# BoardSchem.net
KiCad netlist of a schematic drawn in EAGLE
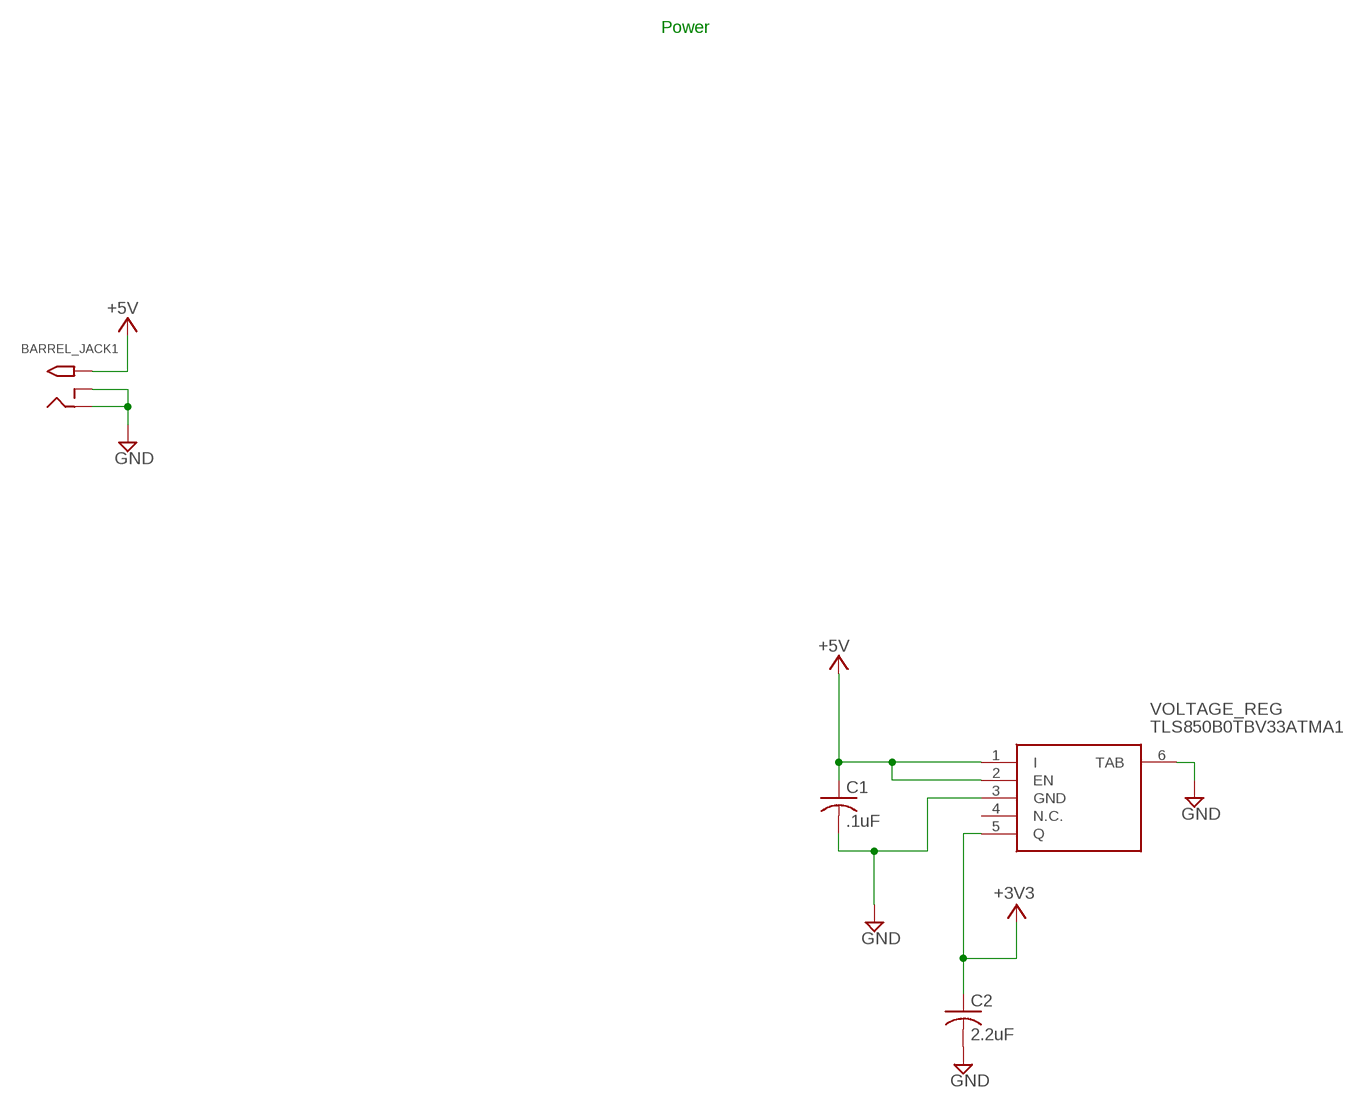
[diagram p0: schematic, sheet 1]
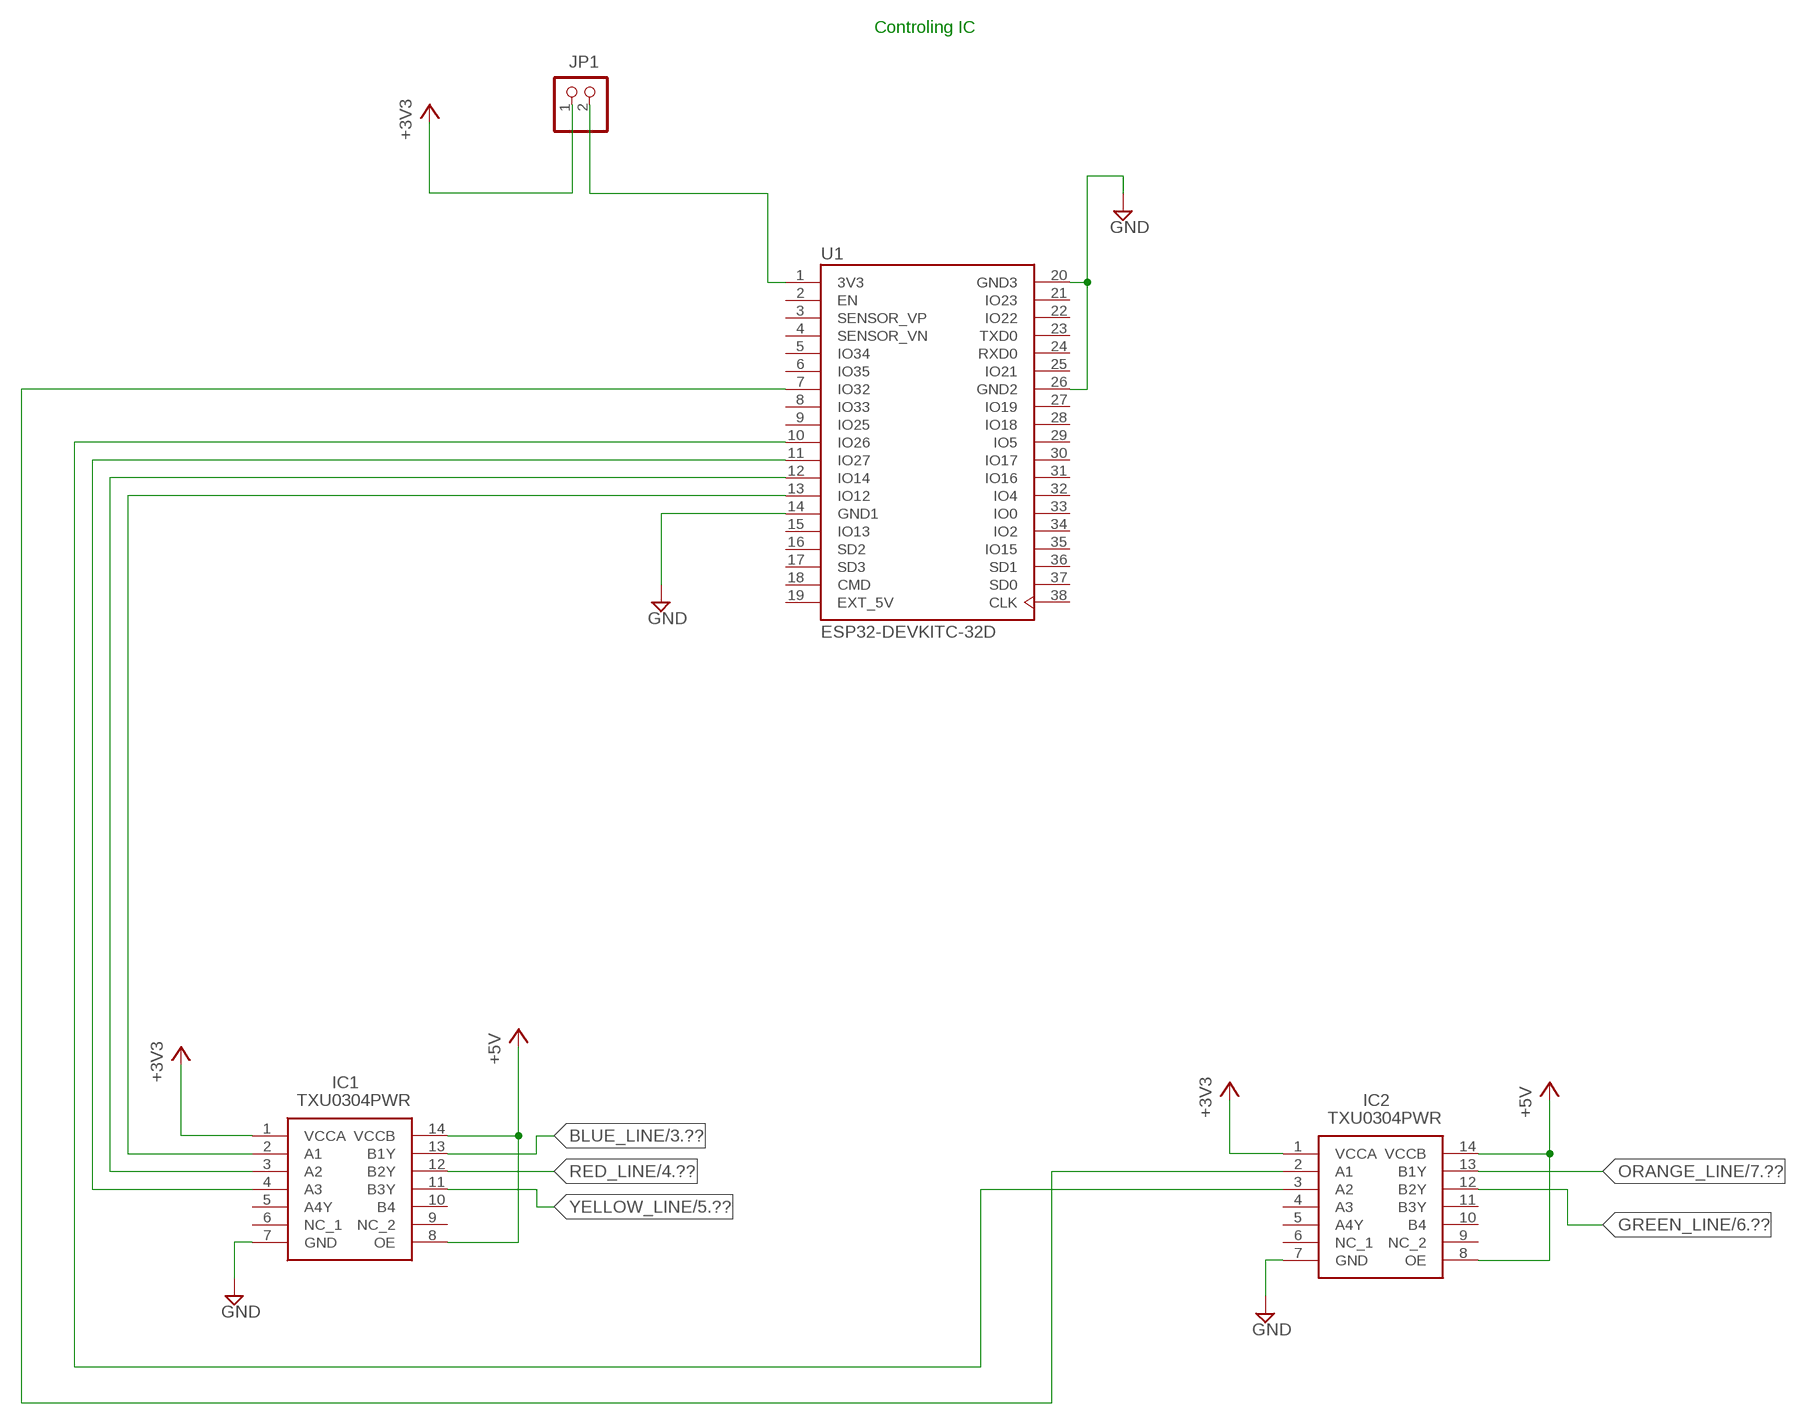
[diagram p1: schematic, sheet 2]
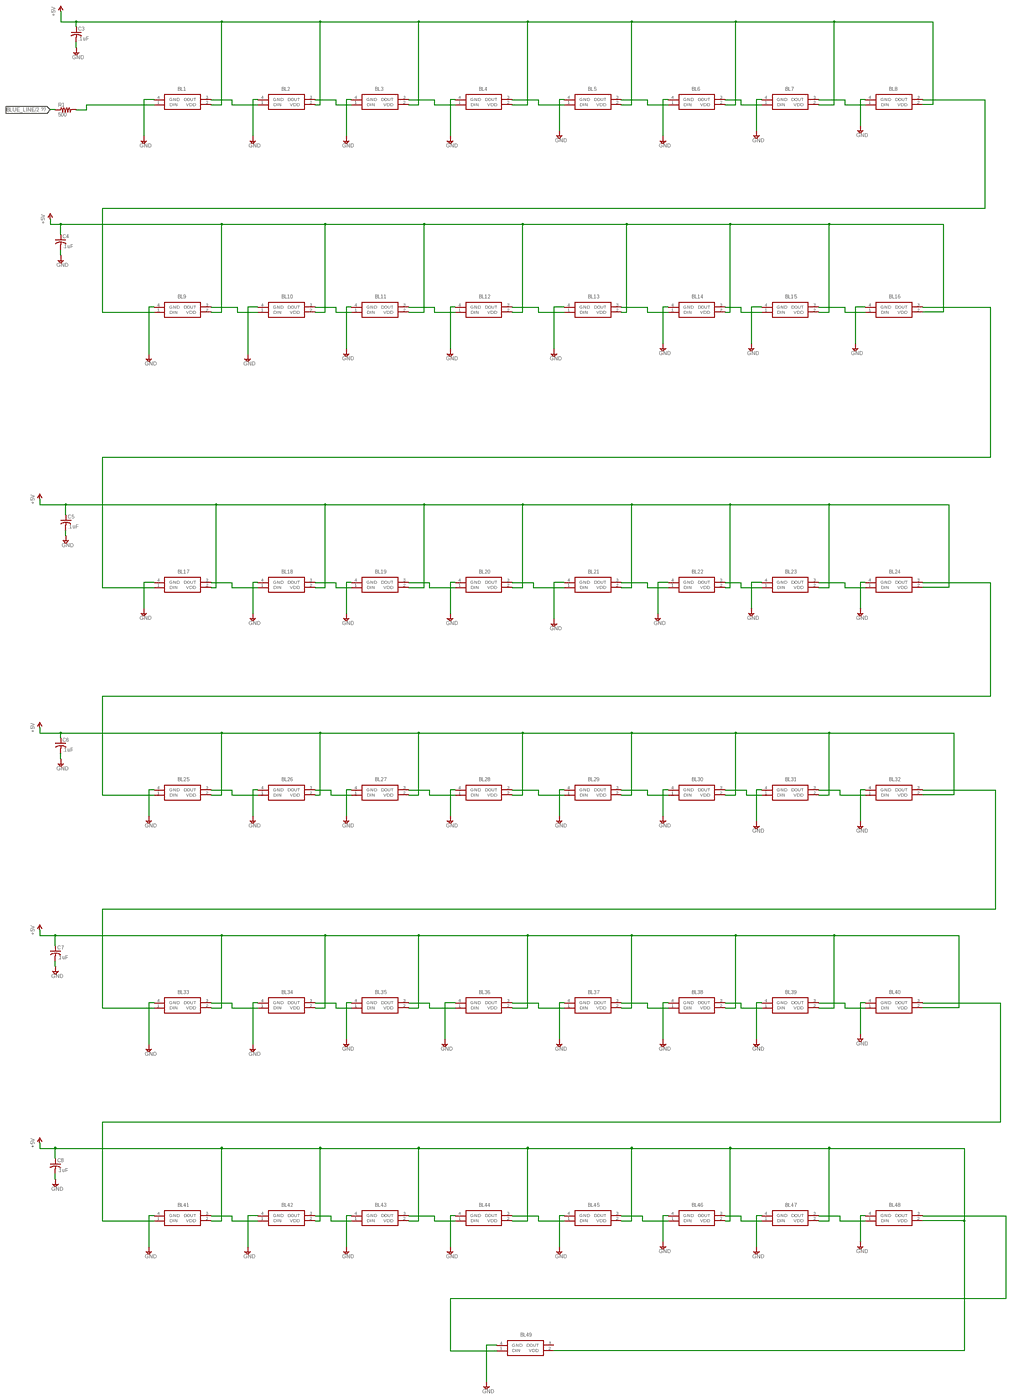
[diagram p2: schematic, sheet 3, overview]
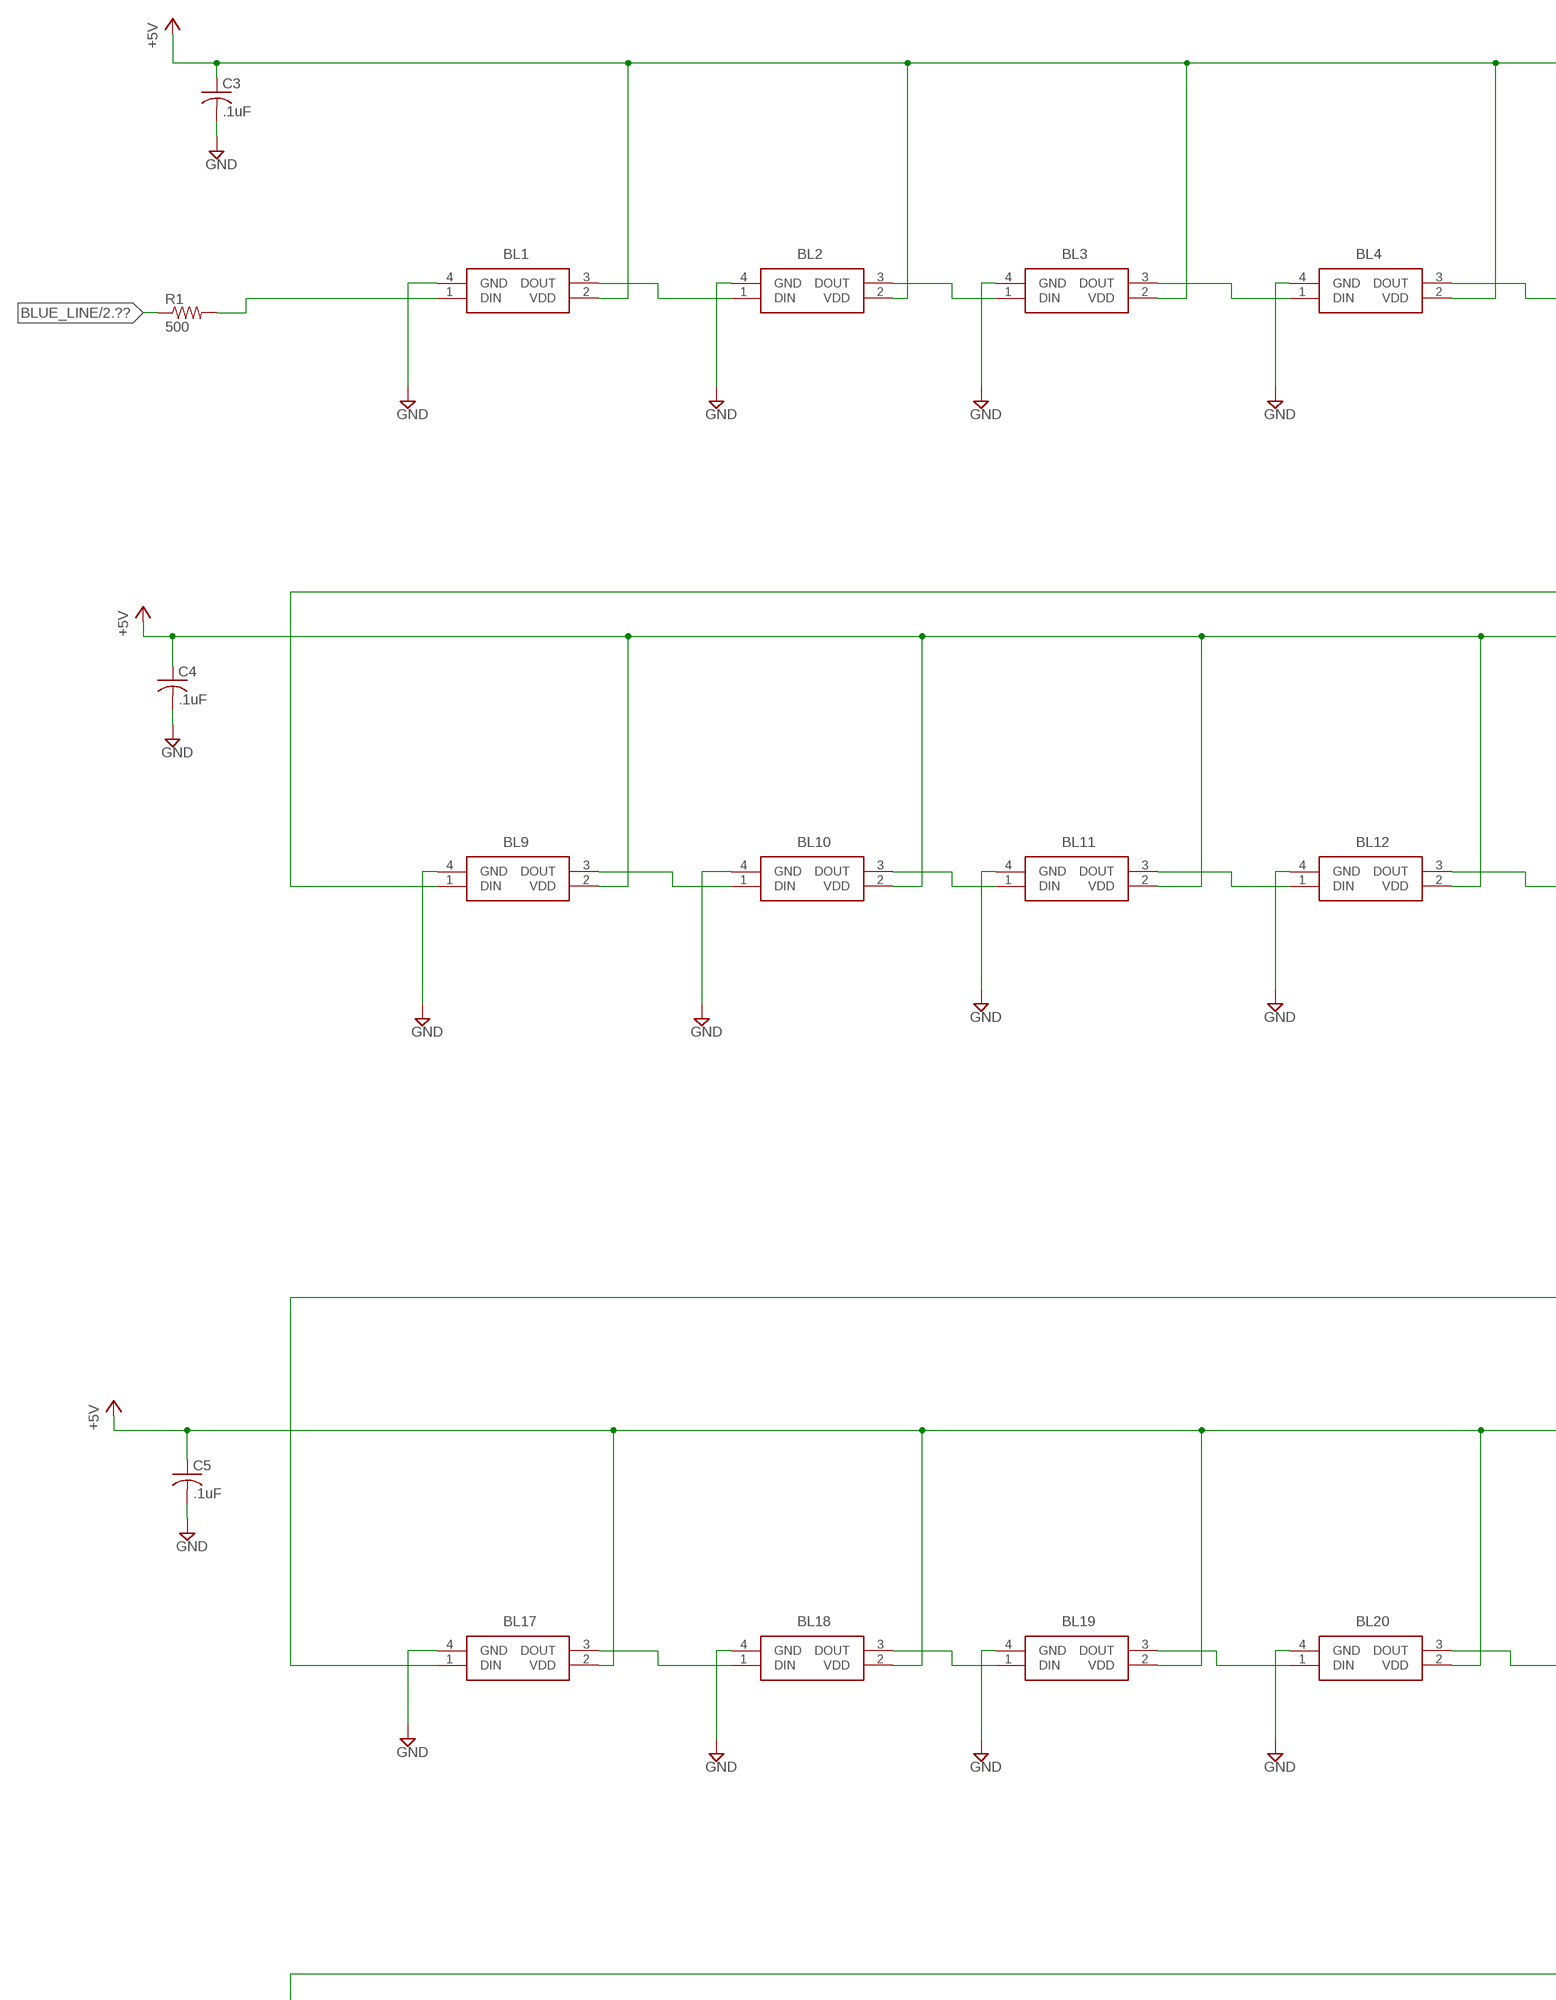
[diagram p3: schematic, sheet 3, part 1 of 4]
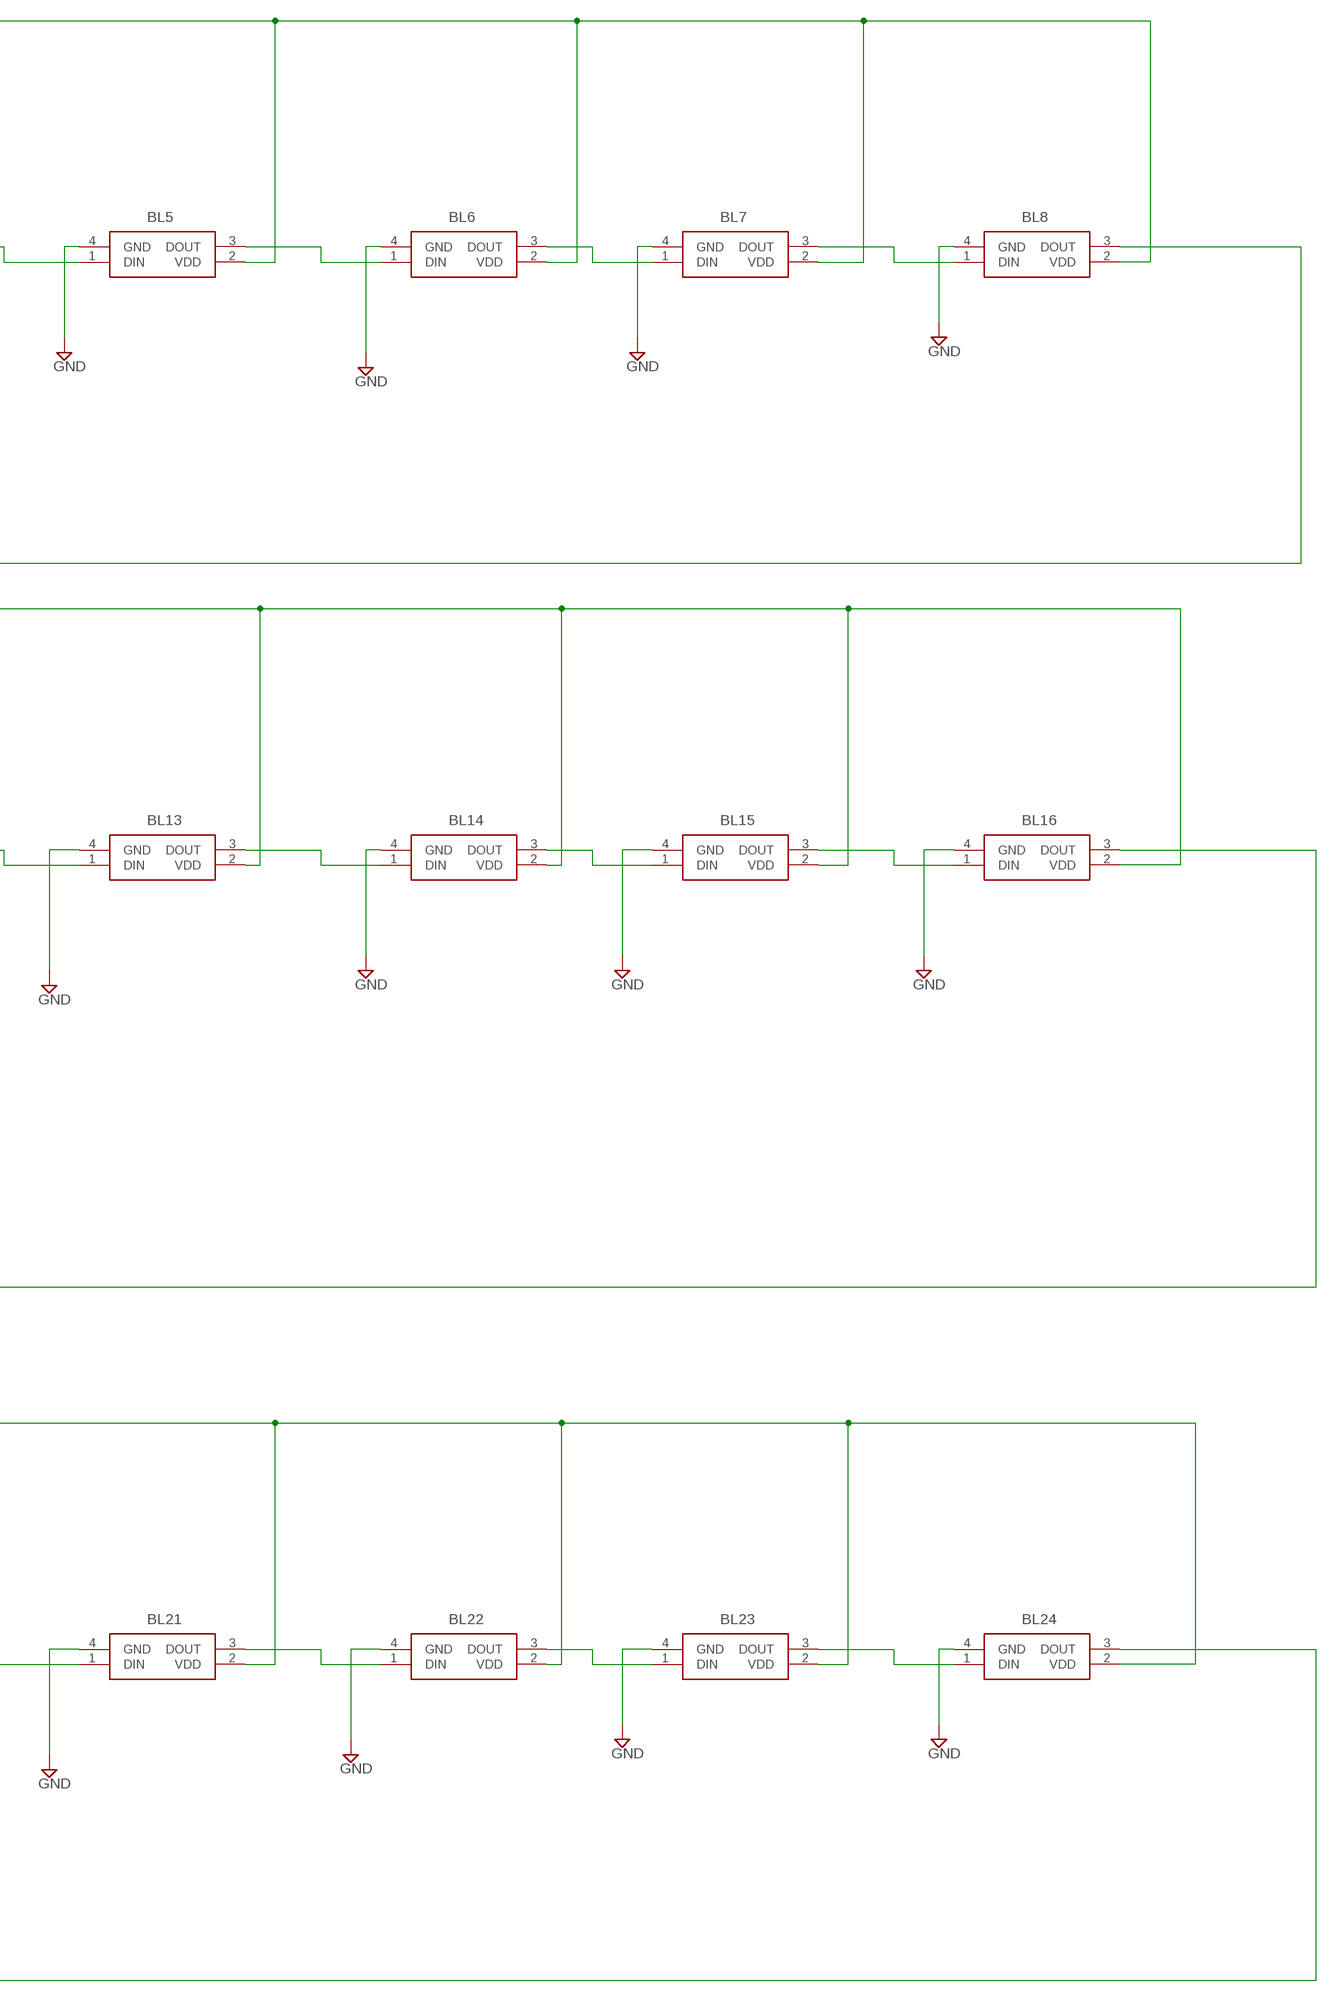
[diagram p4: schematic, sheet 3, part 2 of 4]
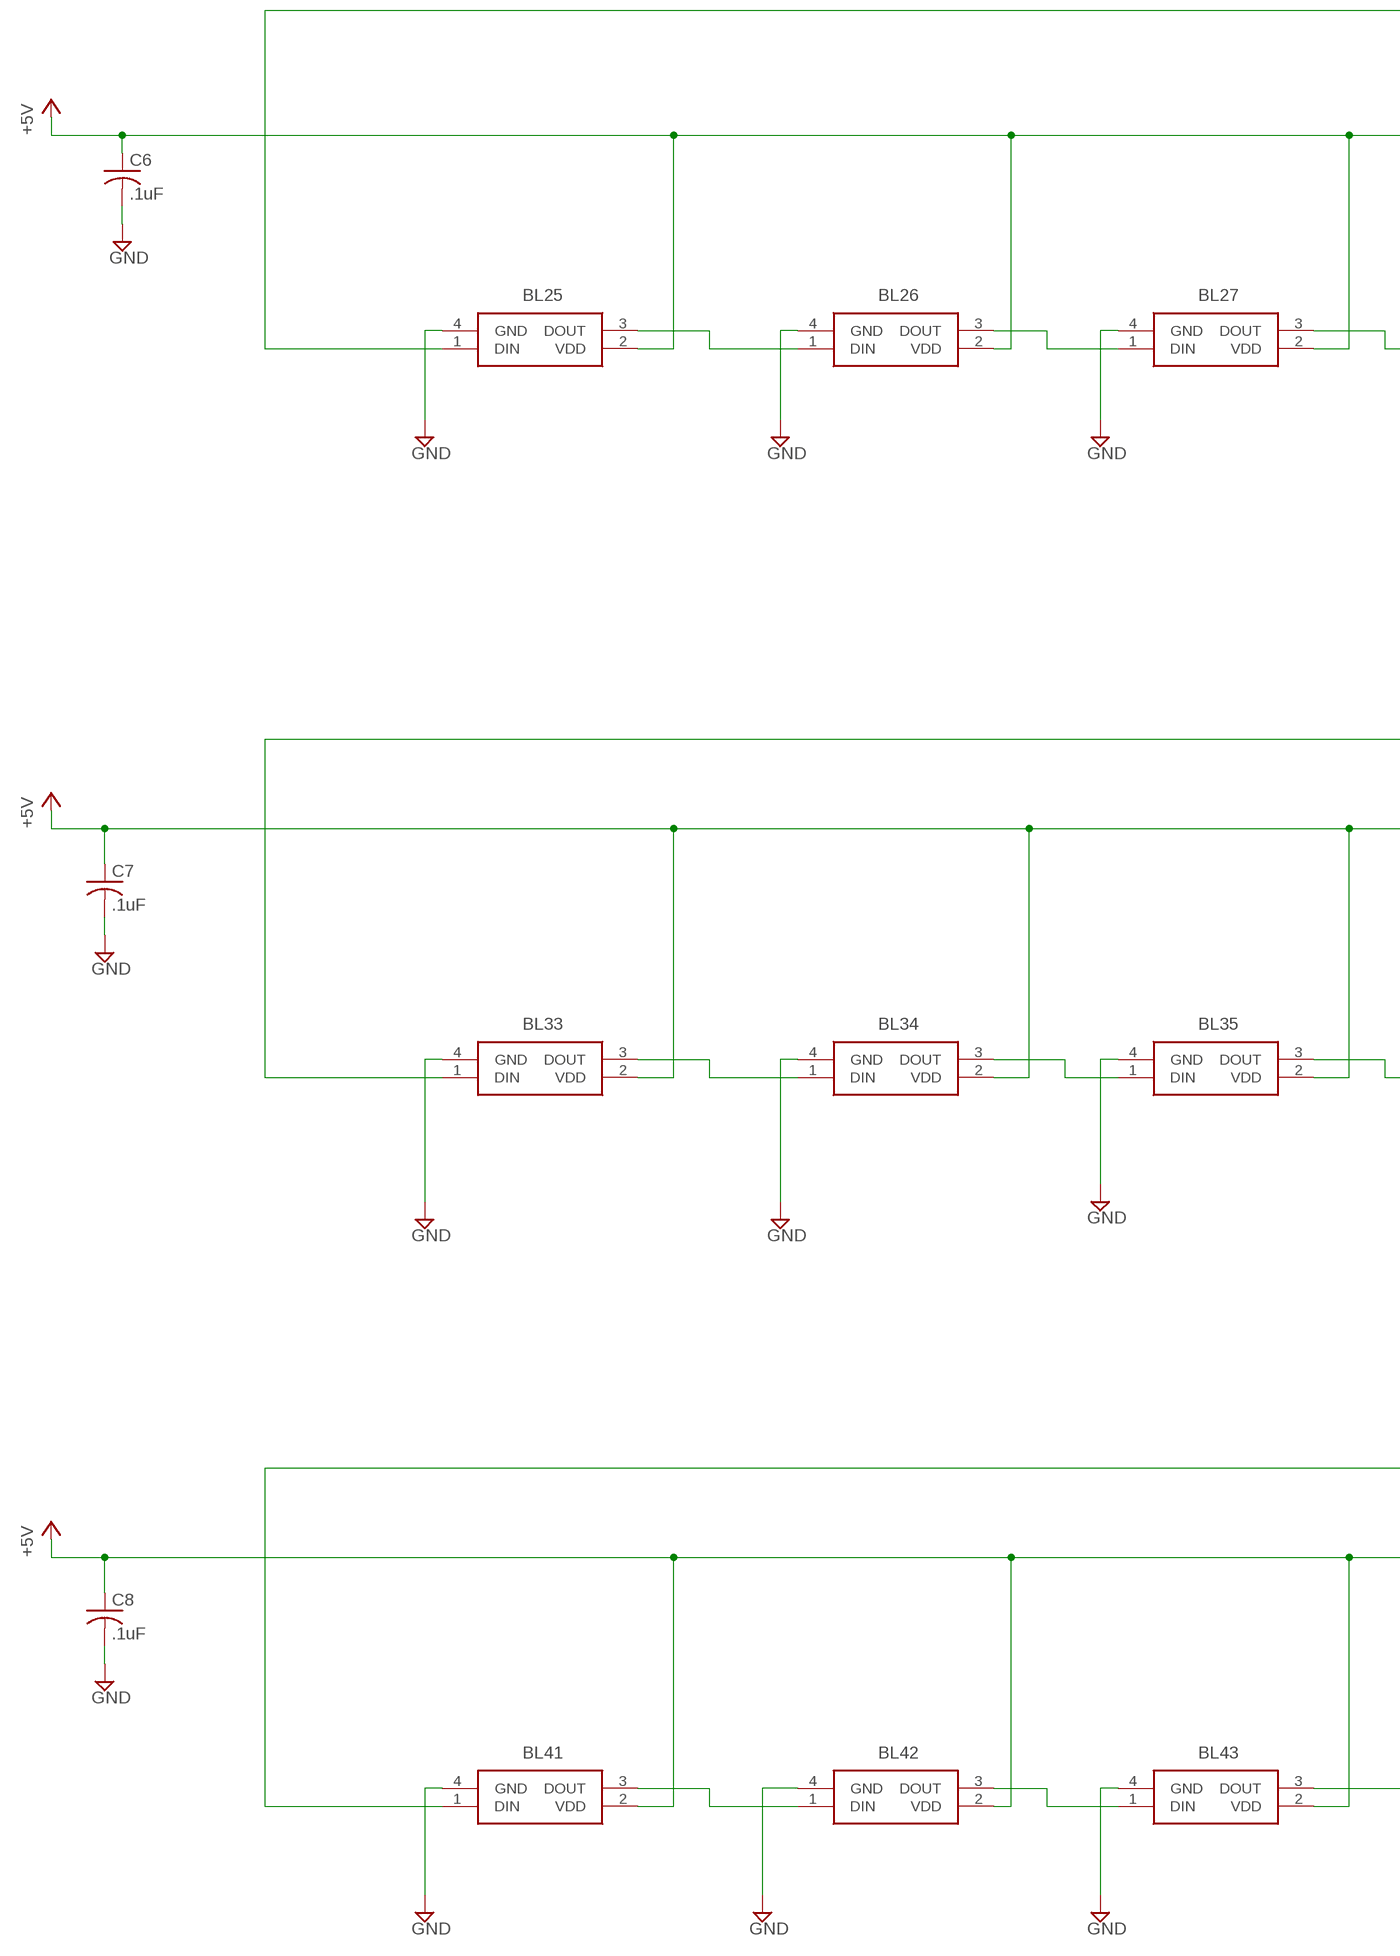
[diagram p5: schematic, sheet 3, part 3 of 4]
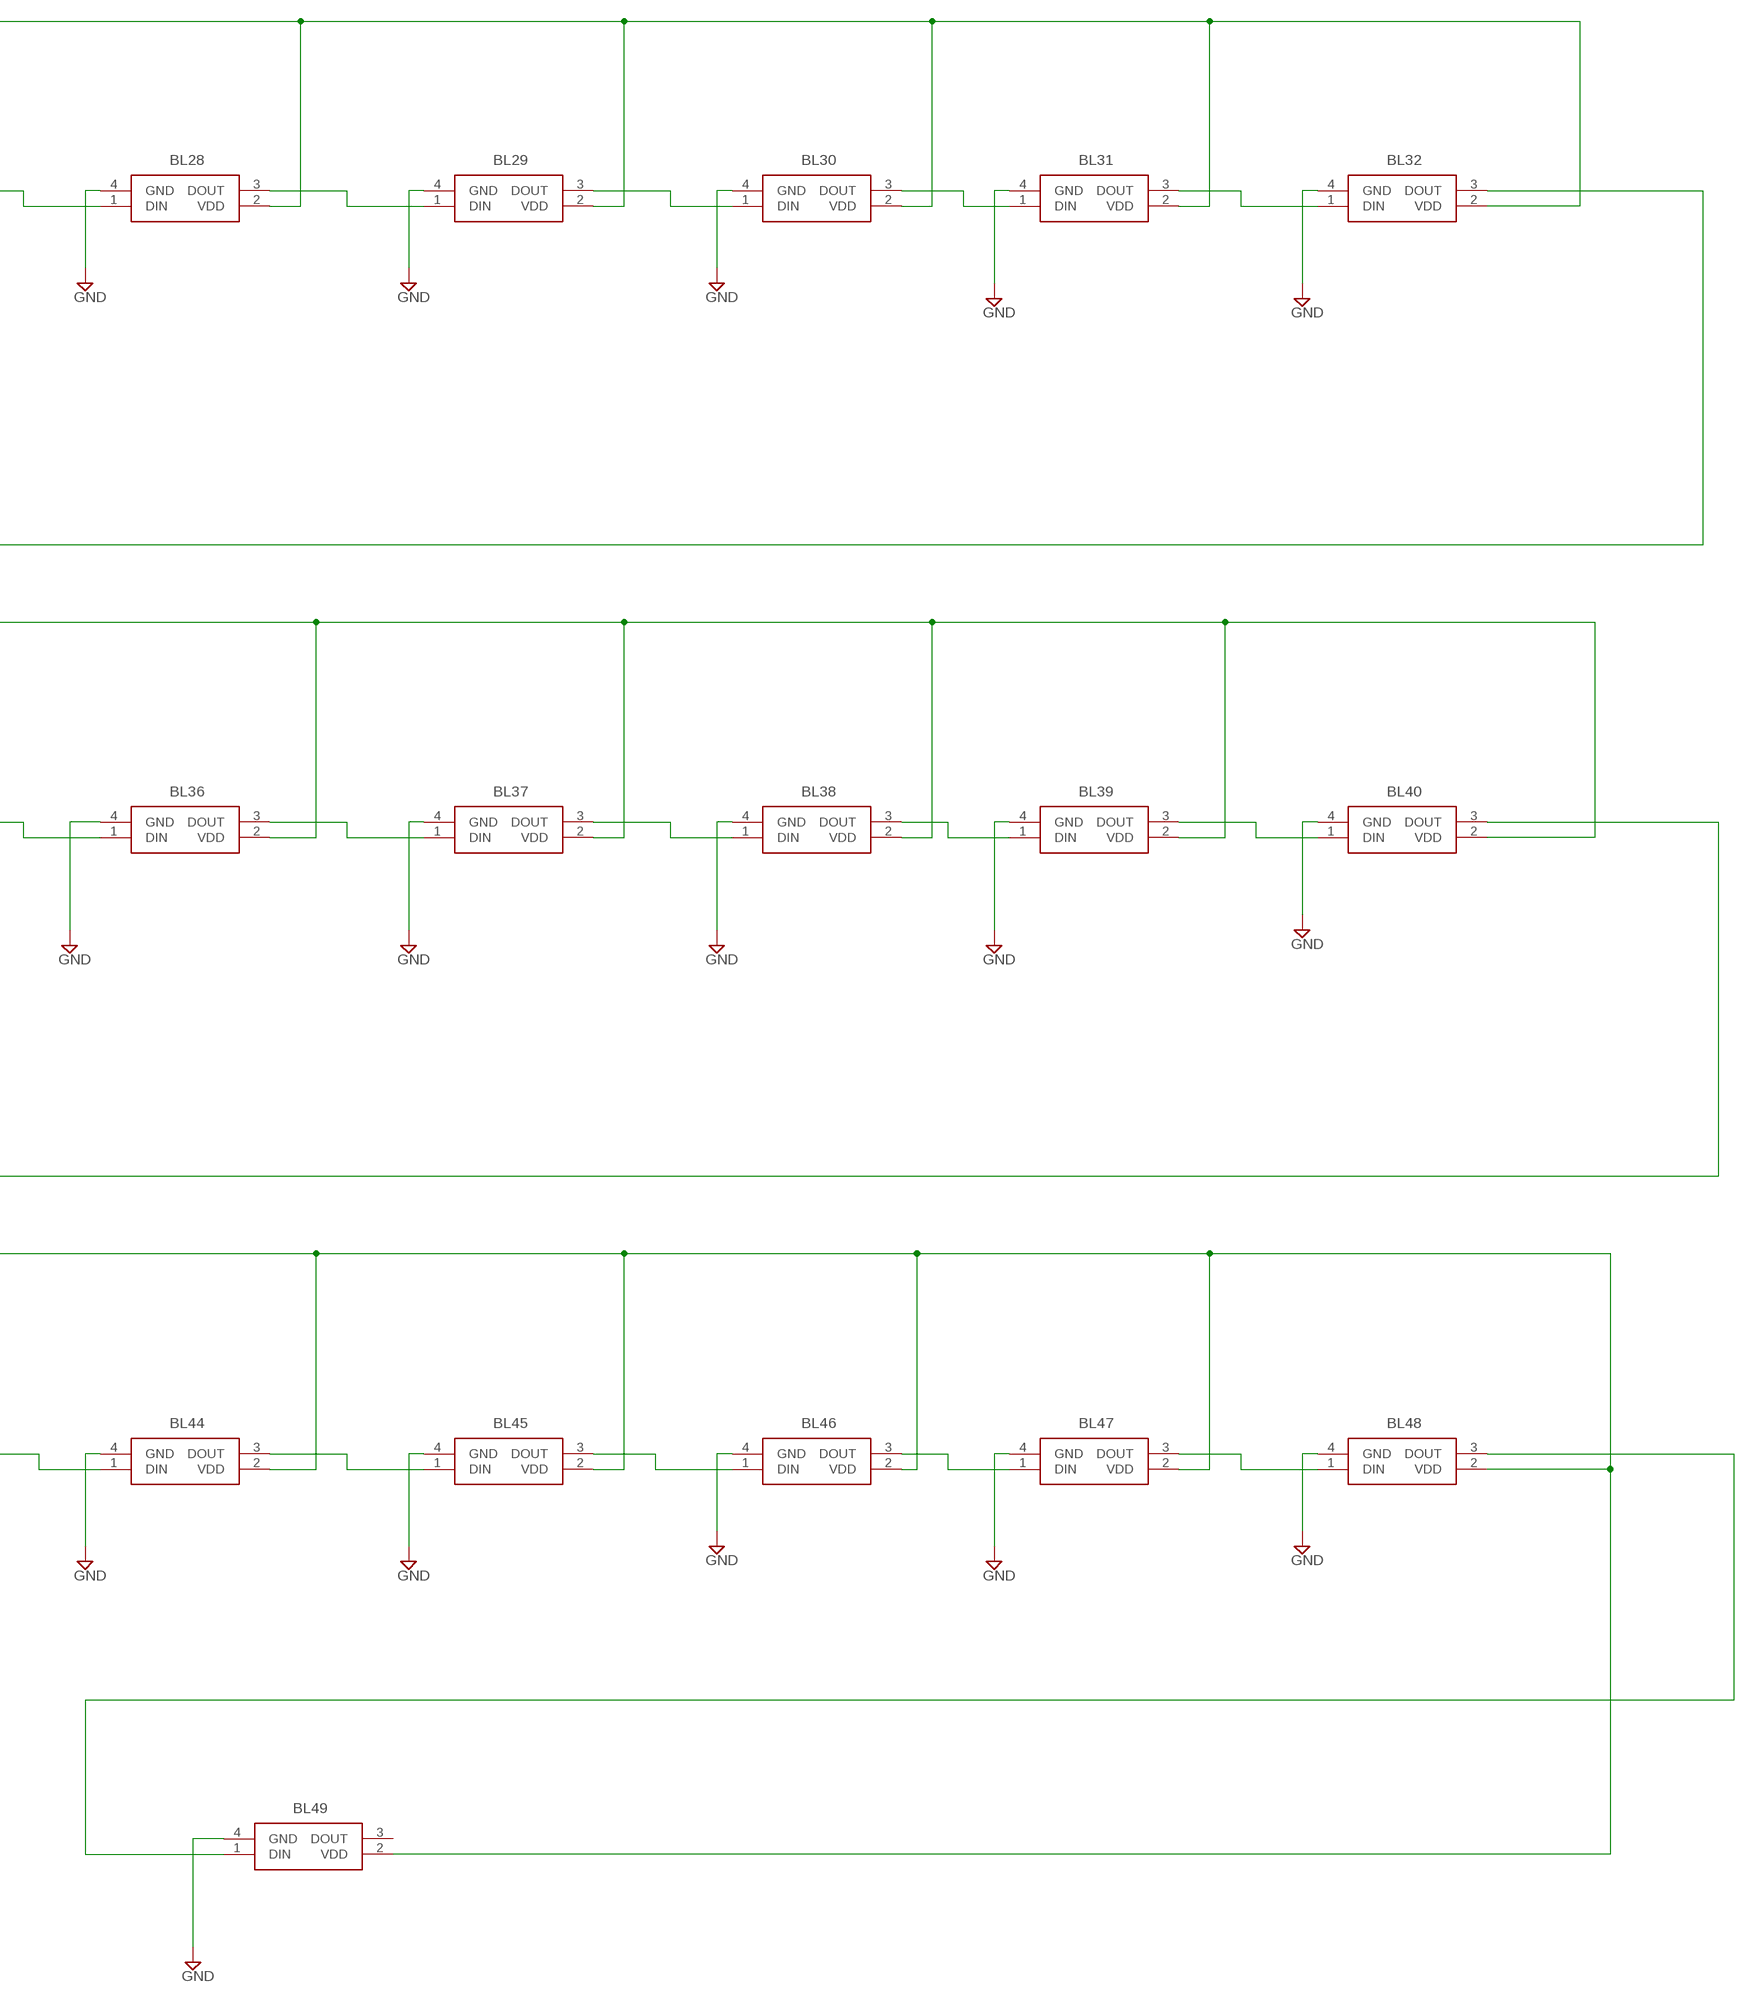
[diagram p6: schematic, sheet 3, part 4 of 4]
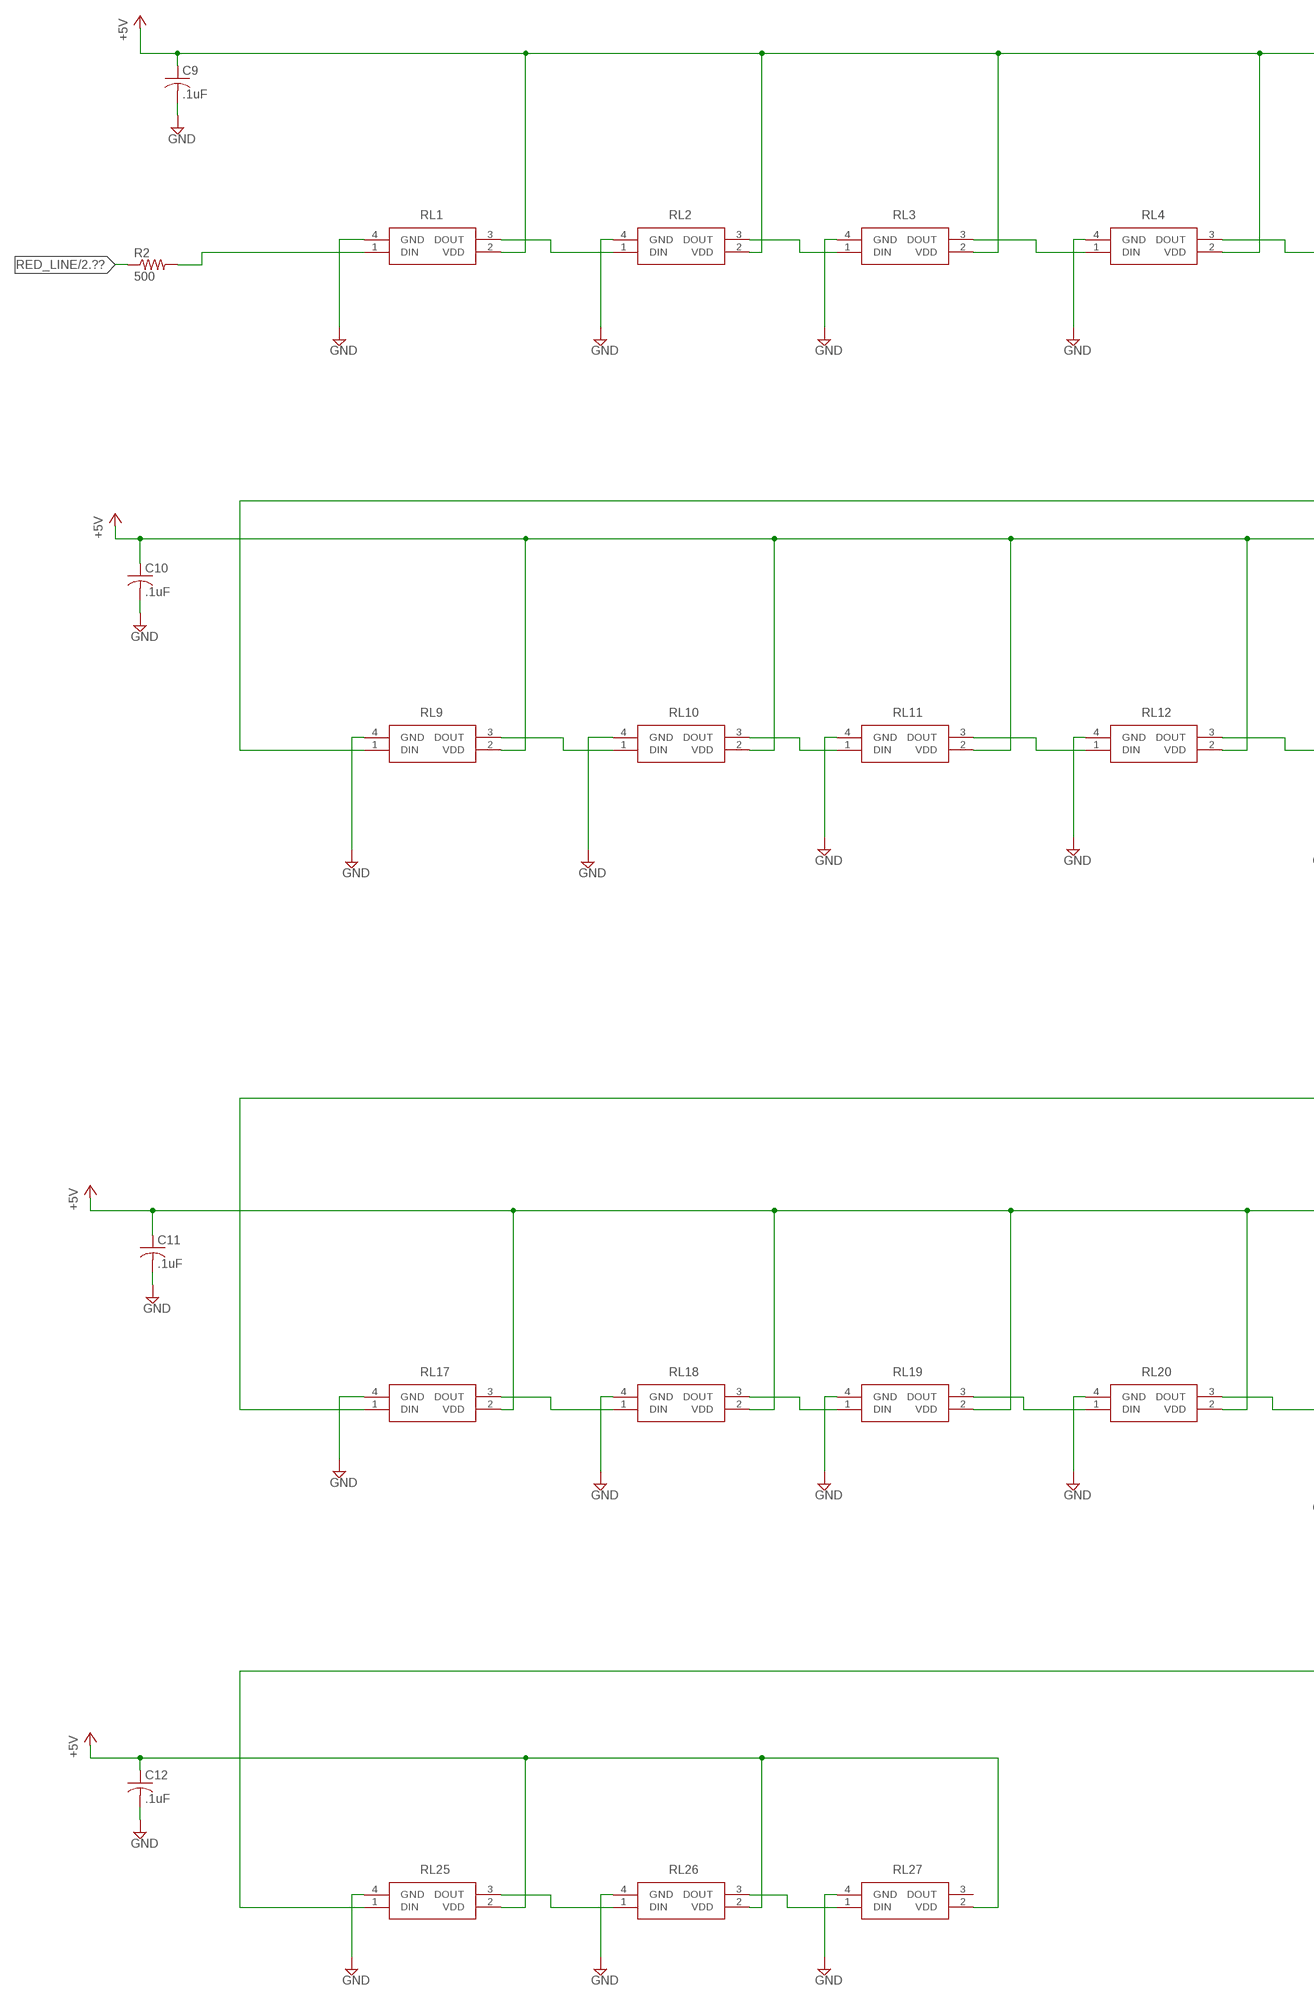
[diagram p7: schematic, sheet 4, part 1 of 2]
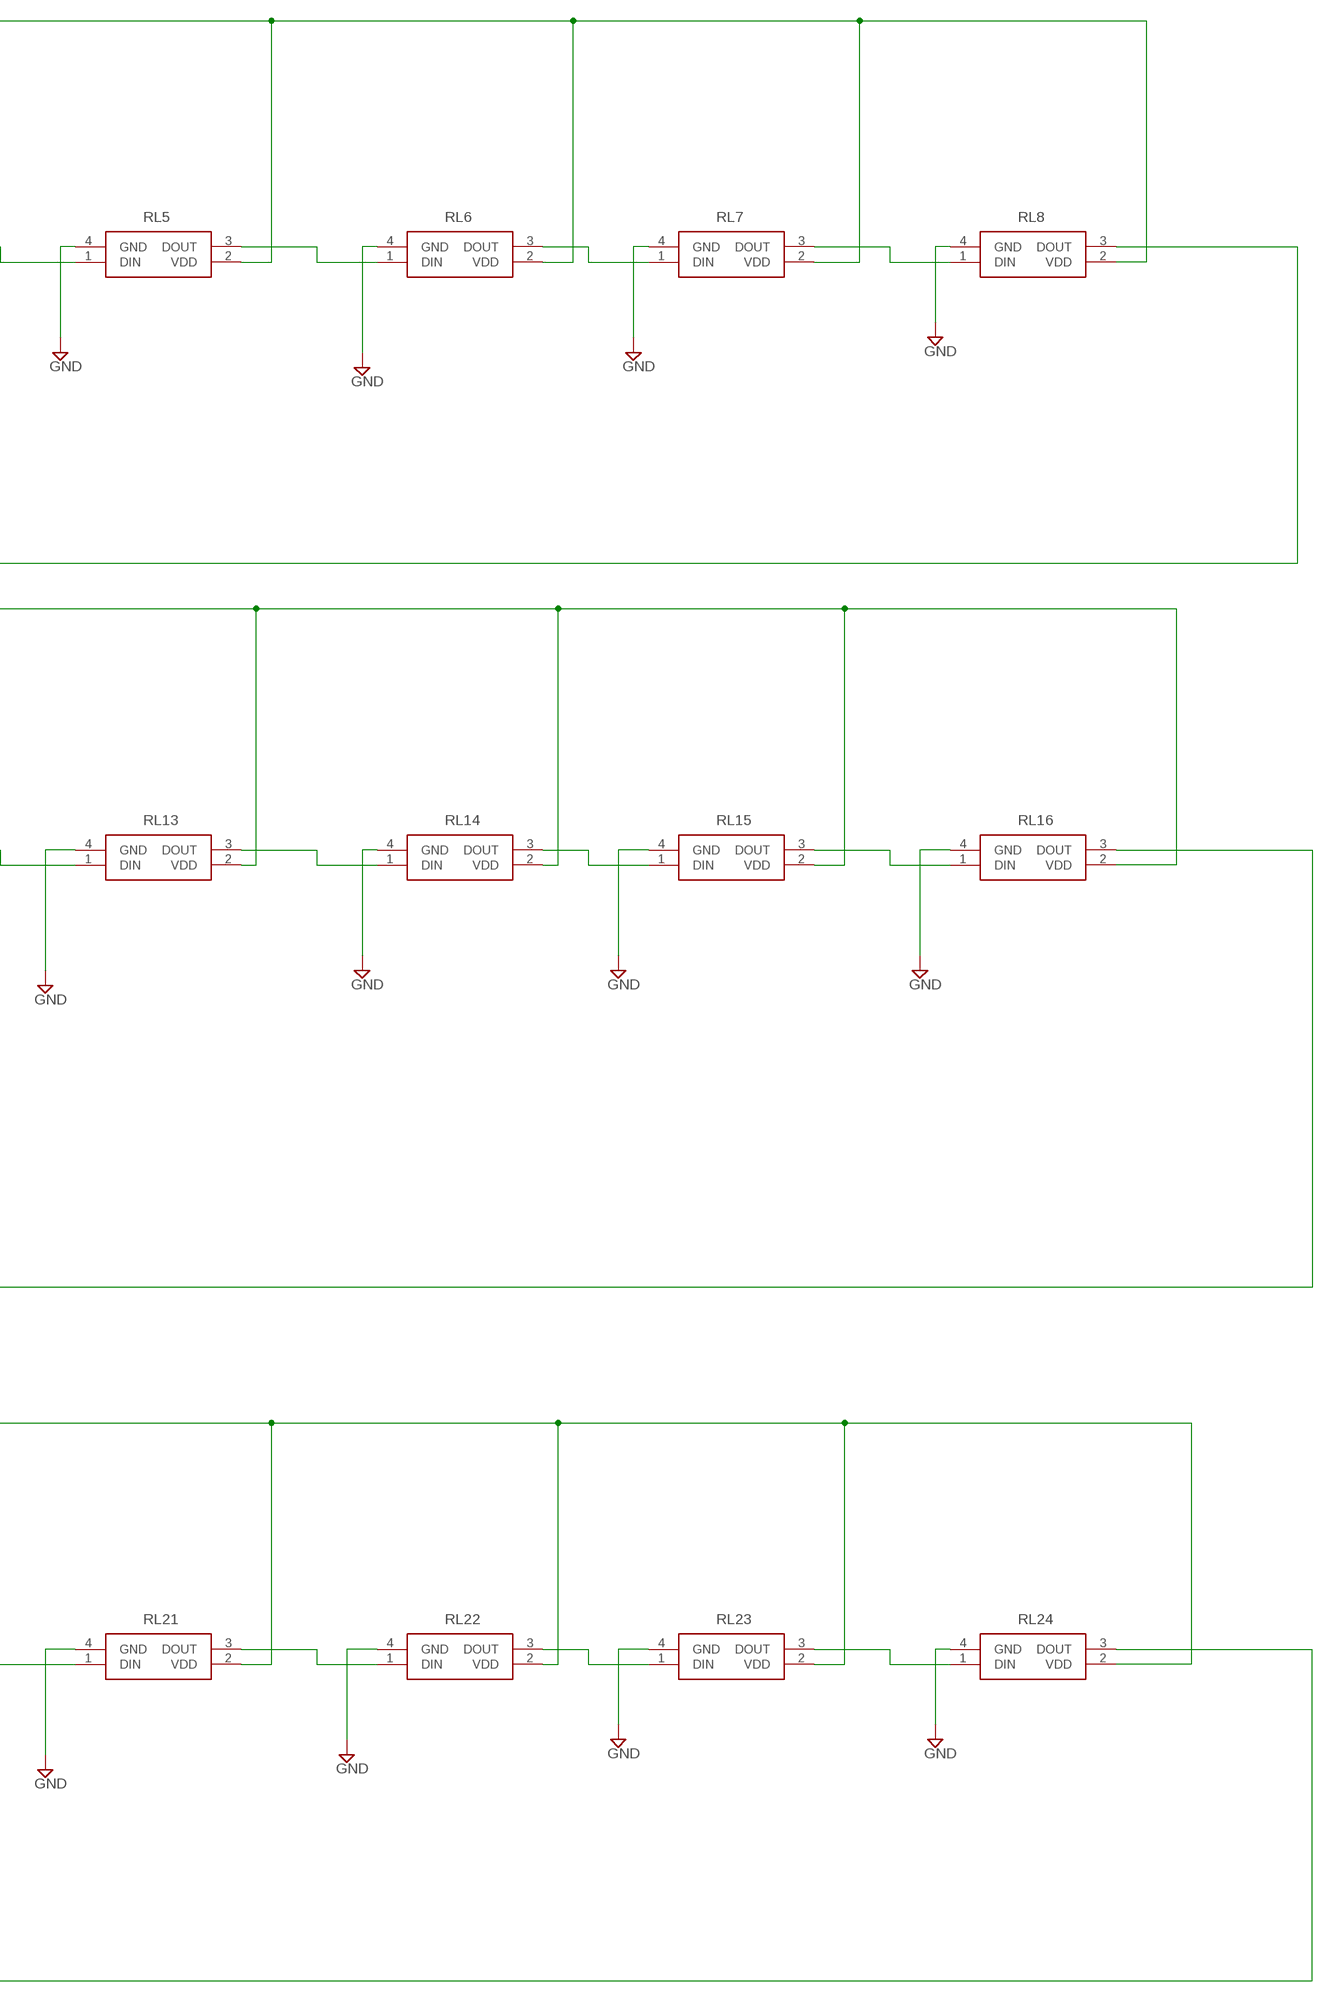
[diagram p8: schematic, sheet 4, part 2 of 2]
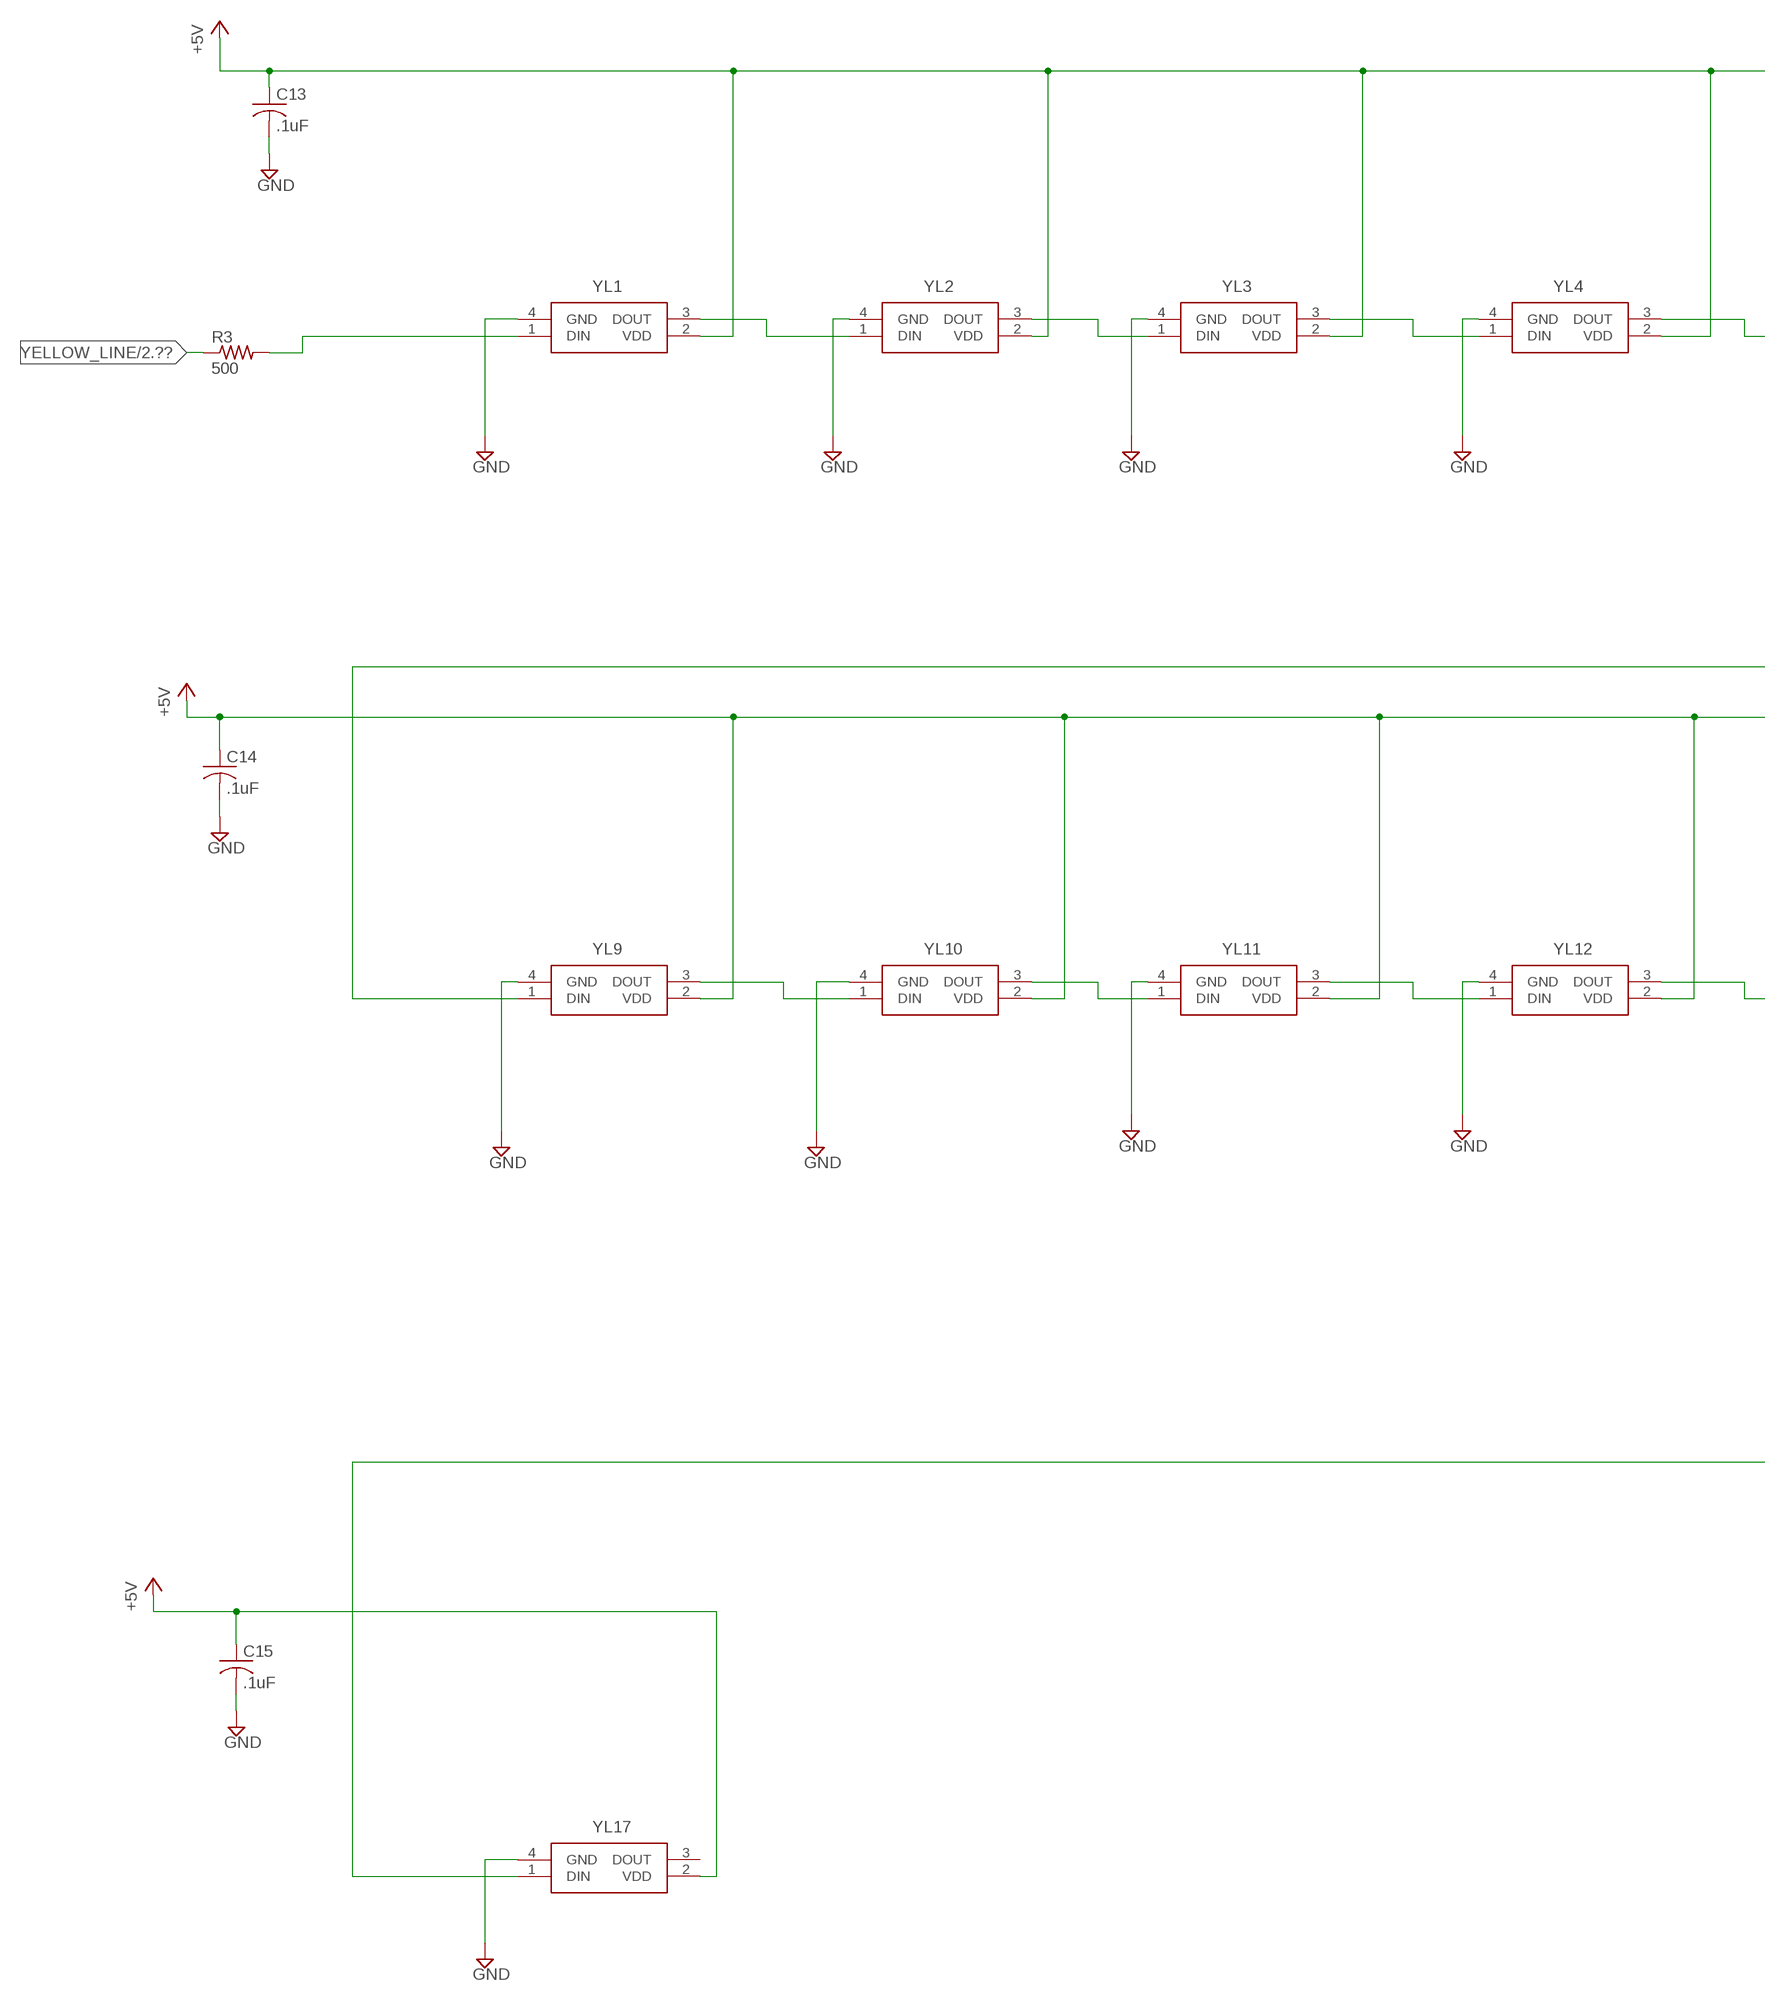
[diagram p9: schematic, sheet 5, part 1 of 2]
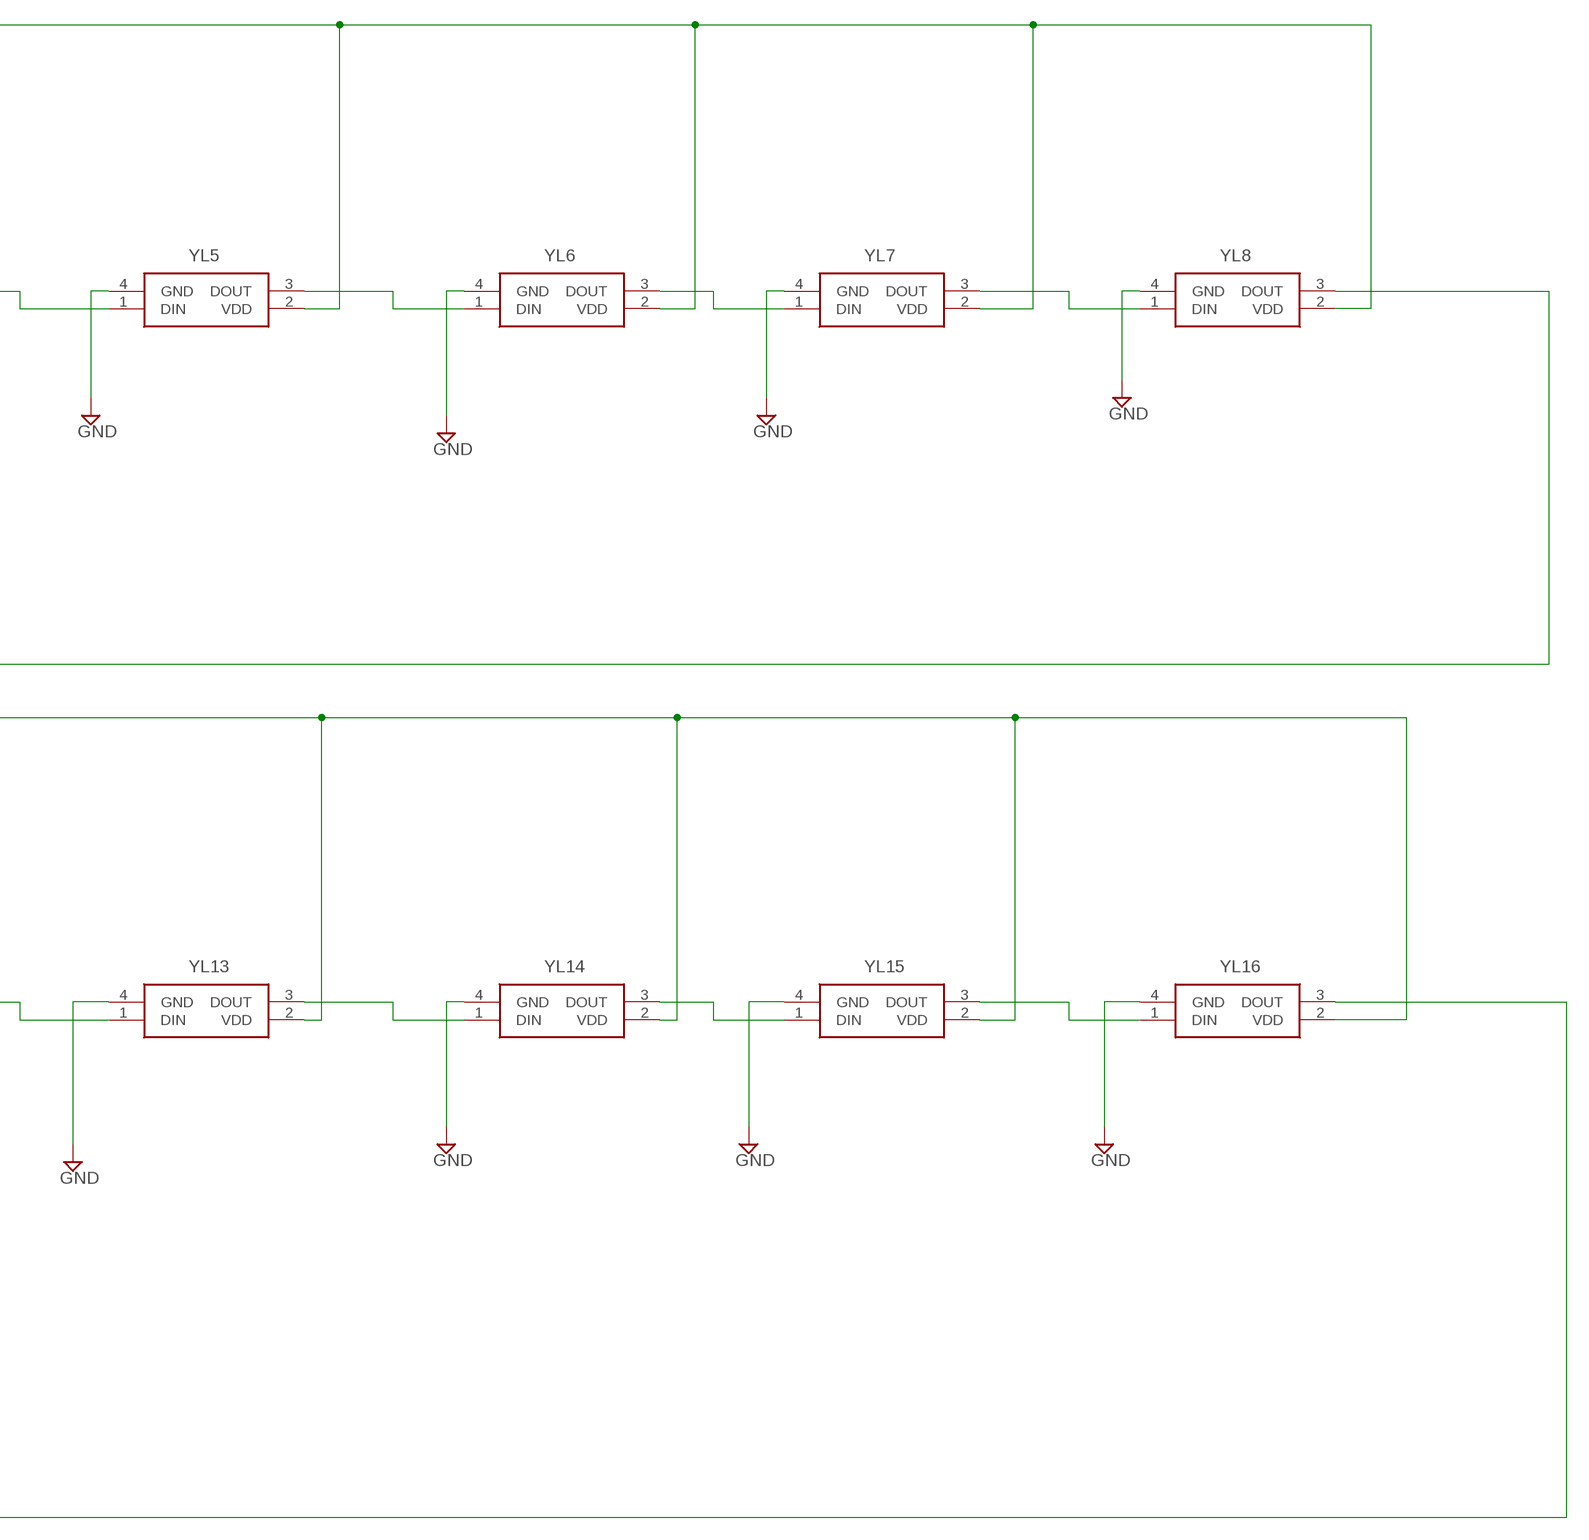
[diagram p10: schematic, sheet 5, part 2 of 2]
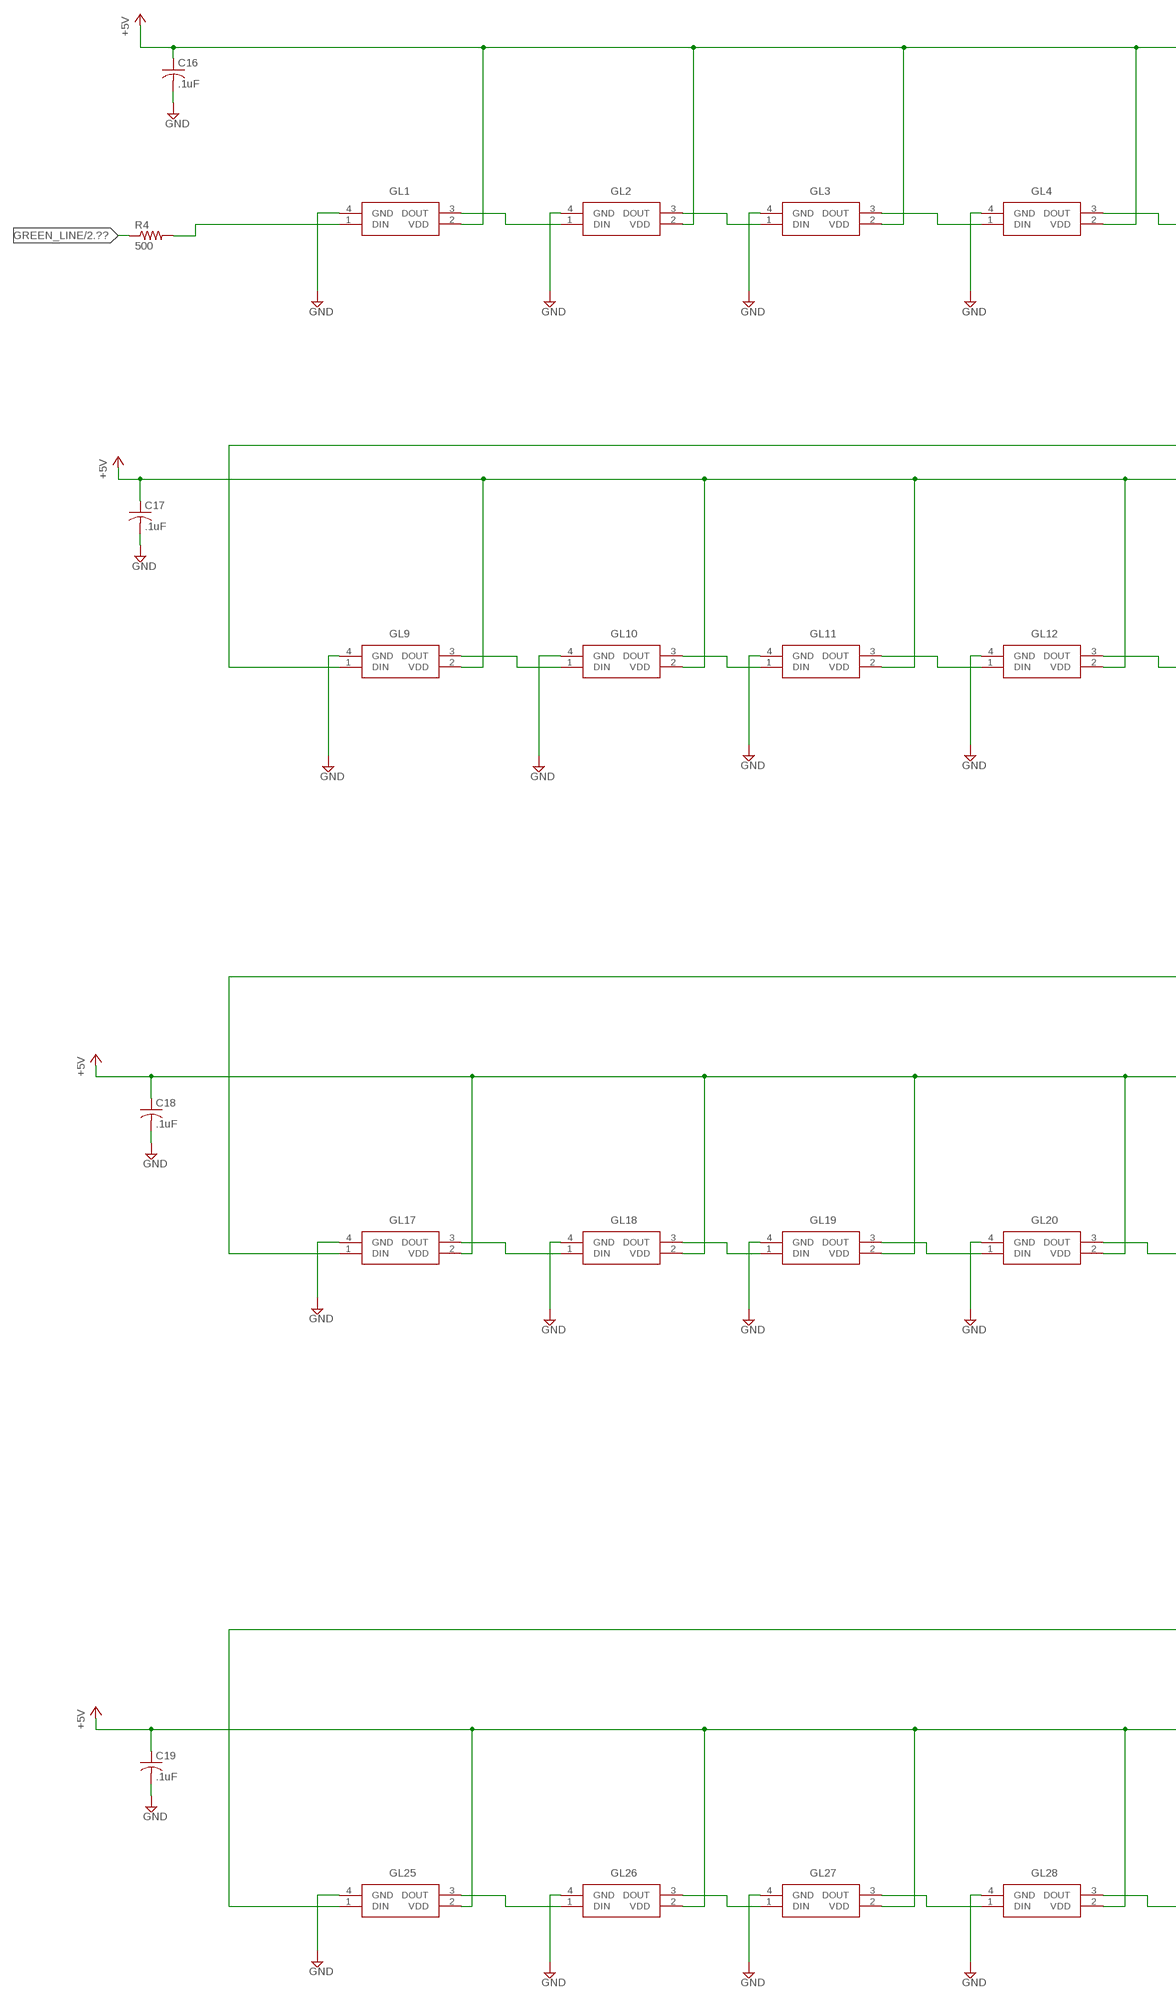
[diagram p11: schematic, sheet 6, part 1 of 2]
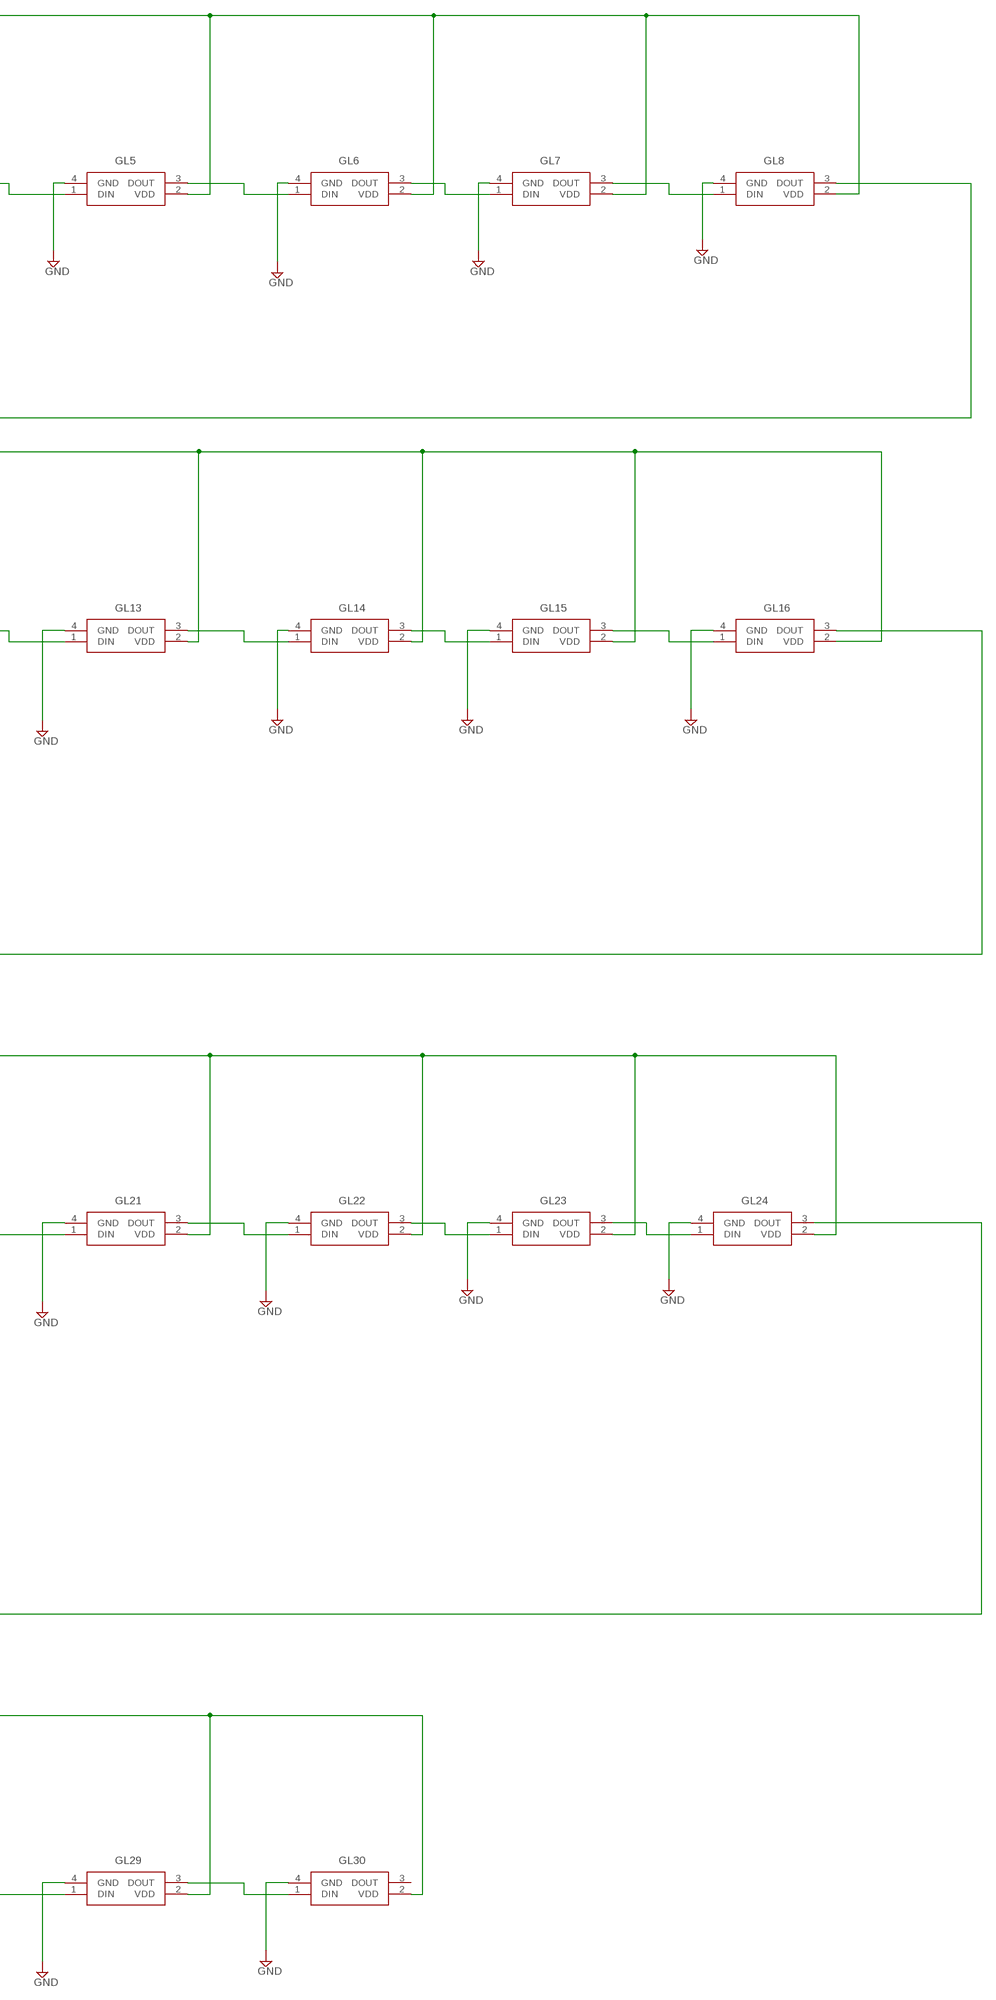
[diagram p12: schematic, sheet 6, part 2 of 2]
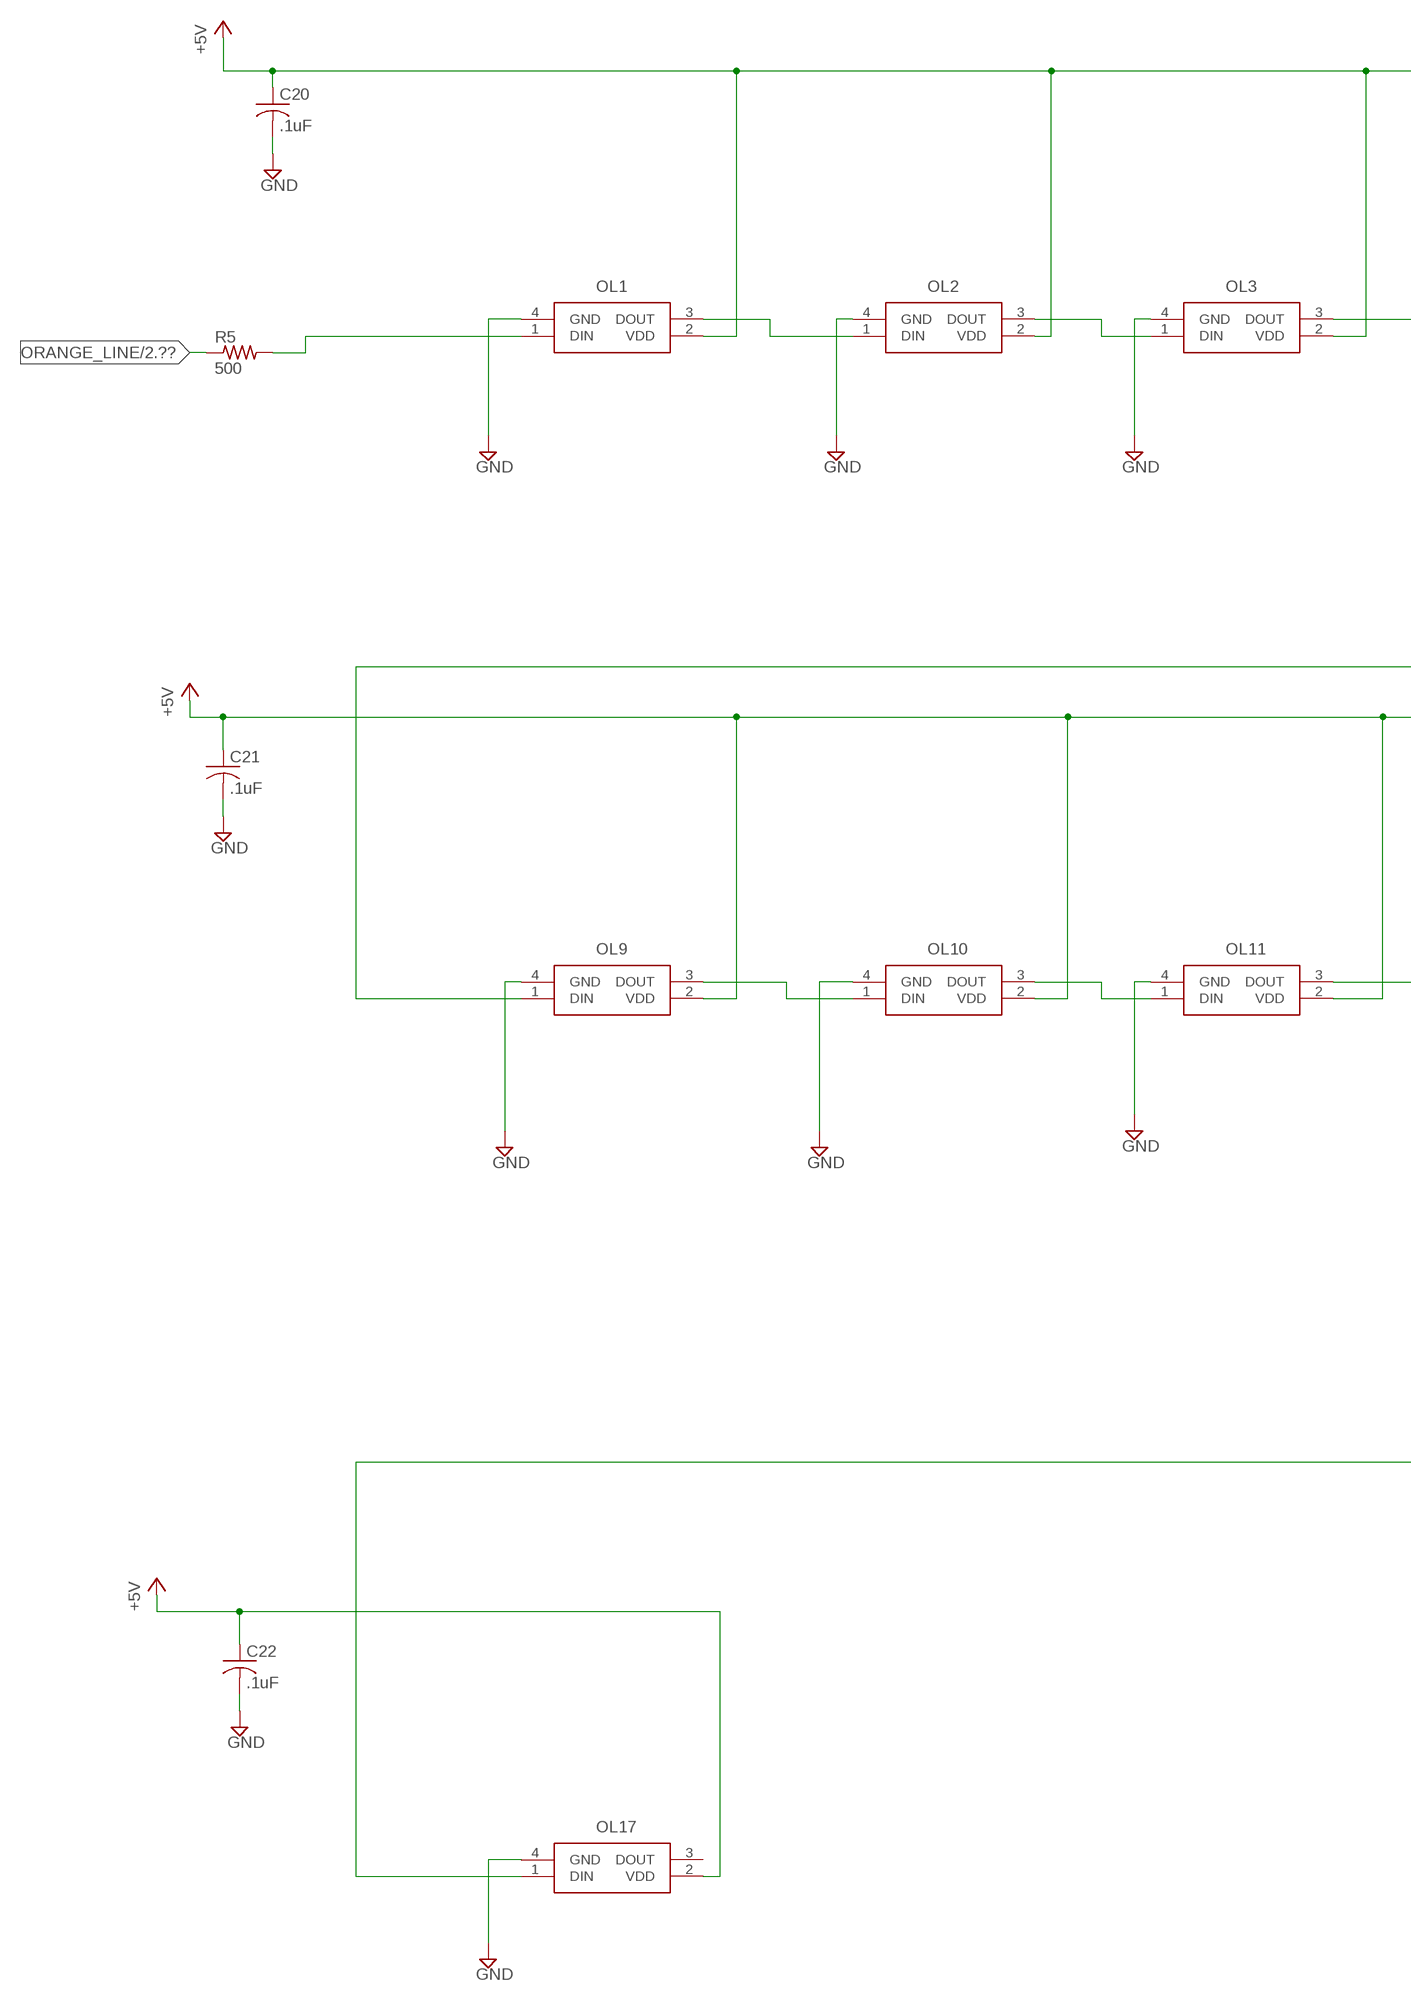
[diagram p13: schematic, sheet 7, part 1 of 2]
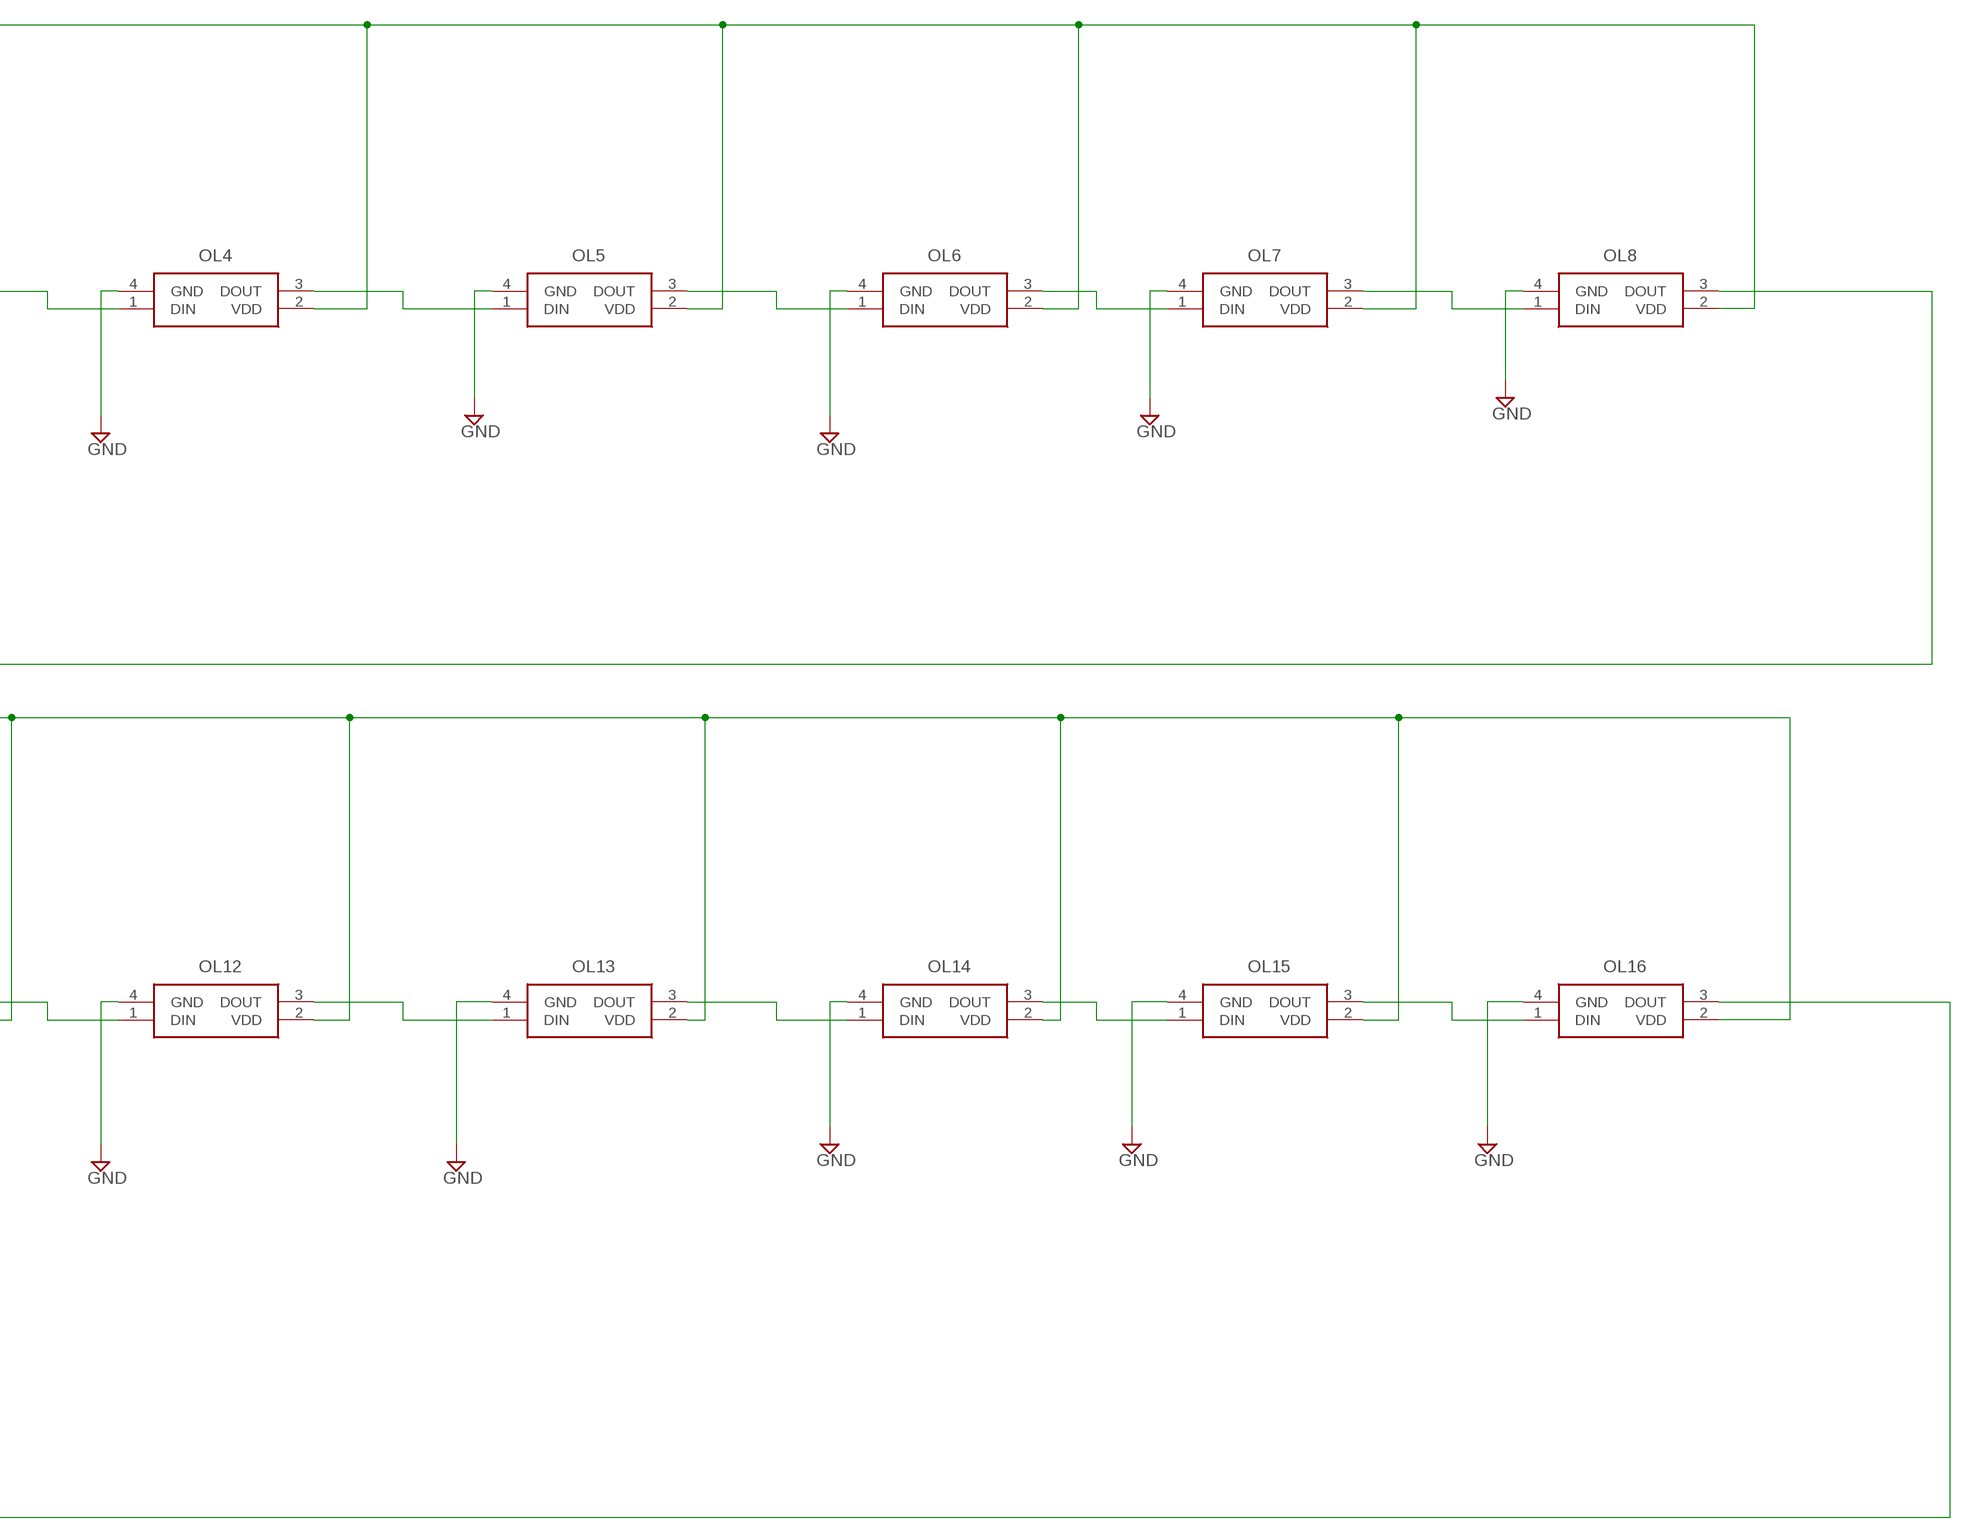
[diagram p14: schematic, sheet 7, part 2 of 2]

(export (version "E")
  (design (tool "Eeschema 10.0.6"))
  (components
    (comp (ref "C13")
      (value ".1uF")
      (footprint "eagle-import:C0805")
      (libsource (lib "eagle-import") (part "C-USC0805"))
    )
    (comp (ref "C14")
      (value ".1uF")
      (footprint "eagle-import:C0805")
      (libsource (lib "eagle-import") (part "C-USC0805"))
    )
    (comp (ref "C15")
      (value ".1uF")
      (footprint "eagle-import:C0805")
      (libsource (lib "eagle-import") (part "C-USC0805"))
    )
    (comp (ref "R3")
      (value "500")
      (footprint "eagle-import:R0805")
      (libsource (lib "eagle-import") (part "R-US_R0805"))
    )
    (comp (ref "YL1")
      (value "4492__SK6805-EC_15_")
      (footprint "eagle-import:4492SK6805EC15")
      (fields (field (name "MANUFACTURER_PART_NUMBER") "4492 (SK6805-EC 15)"))
      (libsource (lib "eagle-import") (part "4492__SK6805-EC_15_"))
    )
    (comp (ref "YL2")
      (value "4492__SK6805-EC_15_")
      (footprint "eagle-import:4492SK6805EC15")
      (fields (field (name "MANUFACTURER_PART_NUMBER") "4492 (SK6805-EC 15)"))
      (libsource (lib "eagle-import") (part "4492__SK6805-EC_15_"))
    )
    (comp (ref "YL3")
      (value "4492__SK6805-EC_15_")
      (footprint "eagle-import:4492SK6805EC15")
      (fields (field (name "MANUFACTURER_PART_NUMBER") "4492 (SK6805-EC 15)"))
      (libsource (lib "eagle-import") (part "4492__SK6805-EC_15_"))
    )
    (comp (ref "YL4")
      (value "4492__SK6805-EC_15_")
      (footprint "eagle-import:4492SK6805EC15")
      (fields (field (name "MANUFACTURER_PART_NUMBER") "4492 (SK6805-EC 15)"))
      (libsource (lib "eagle-import") (part "4492__SK6805-EC_15_"))
    )
    (comp (ref "YL5")
      (value "4492__SK6805-EC_15_")
      (footprint "eagle-import:4492SK6805EC15")
      (fields (field (name "MANUFACTURER_PART_NUMBER") "4492 (SK6805-EC 15)"))
      (libsource (lib "eagle-import") (part "4492__SK6805-EC_15_"))
    )
    (comp (ref "YL6")
      (value "4492__SK6805-EC_15_")
      (footprint "eagle-import:4492SK6805EC15")
      (fields (field (name "MANUFACTURER_PART_NUMBER") "4492 (SK6805-EC 15)"))
      (libsource (lib "eagle-import") (part "4492__SK6805-EC_15_"))
    )
    (comp (ref "YL7")
      (value "4492__SK6805-EC_15_")
      (footprint "eagle-import:4492SK6805EC15")
      (fields (field (name "MANUFACTURER_PART_NUMBER") "4492 (SK6805-EC 15)"))
      (libsource (lib "eagle-import") (part "4492__SK6805-EC_15_"))
    )
    (comp (ref "YL8")
      (value "4492__SK6805-EC_15_")
      (footprint "eagle-import:4492SK6805EC15")
      (fields (field (name "MANUFACTURER_PART_NUMBER") "4492 (SK6805-EC 15)"))
      (libsource (lib "eagle-import") (part "4492__SK6805-EC_15_"))
    )
    (comp (ref "YL9")
      (value "4492__SK6805-EC_15_")
      (footprint "eagle-import:4492SK6805EC15")
      (fields (field (name "MANUFACTURER_PART_NUMBER") "4492 (SK6805-EC 15)"))
      (libsource (lib "eagle-import") (part "4492__SK6805-EC_15_"))
    )
    (comp (ref "YL10")
      (value "4492__SK6805-EC_15_")
      (footprint "eagle-import:4492SK6805EC15")
      (fields (field (name "MANUFACTURER_PART_NUMBER") "4492 (SK6805-EC 15)"))
      (libsource (lib "eagle-import") (part "4492__SK6805-EC_15_"))
    )
    (comp (ref "YL11")
      (value "4492__SK6805-EC_15_")
      (footprint "eagle-import:4492SK6805EC15")
      (fields (field (name "MANUFACTURER_PART_NUMBER") "4492 (SK6805-EC 15)"))
      (libsource (lib "eagle-import") (part "4492__SK6805-EC_15_"))
    )
    (comp (ref "YL12")
      (value "4492__SK6805-EC_15_")
      (footprint "eagle-import:4492SK6805EC15")
      (fields (field (name "MANUFACTURER_PART_NUMBER") "4492 (SK6805-EC 15)"))
      (libsource (lib "eagle-import") (part "4492__SK6805-EC_15_"))
    )
    (comp (ref "YL13")
      (value "4492__SK6805-EC_15_")
      (footprint "eagle-import:4492SK6805EC15")
      (fields (field (name "MANUFACTURER_PART_NUMBER") "4492 (SK6805-EC 15)"))
      (libsource (lib "eagle-import") (part "4492__SK6805-EC_15_"))
    )
    (comp (ref "YL14")
      (value "4492__SK6805-EC_15_")
      (footprint "eagle-import:4492SK6805EC15")
      (fields (field (name "MANUFACTURER_PART_NUMBER") "4492 (SK6805-EC 15)"))
      (libsource (lib "eagle-import") (part "4492__SK6805-EC_15_"))
    )
    (comp (ref "YL15")
      (value "4492__SK6805-EC_15_")
      (footprint "eagle-import:4492SK6805EC15")
      (fields (field (name "MANUFACTURER_PART_NUMBER") "4492 (SK6805-EC 15)"))
      (libsource (lib "eagle-import") (part "4492__SK6805-EC_15_"))
    )
    (comp (ref "YL16")
      (value "4492__SK6805-EC_15_")
      (footprint "eagle-import:4492SK6805EC15")
      (fields (field (name "MANUFACTURER_PART_NUMBER") "4492 (SK6805-EC 15)"))
      (libsource (lib "eagle-import") (part "4492__SK6805-EC_15_"))
    )
    (comp (ref "YL17")
      (value "4492__SK6805-EC_15_")
      (footprint "eagle-import:4492SK6805EC15")
      (fields (field (name "MANUFACTURER_PART_NUMBER") "4492 (SK6805-EC 15)"))
      (libsource (lib "eagle-import") (part "4492__SK6805-EC_15_"))
    )
    (comp (ref "BARREL_JACK1")
      (value "2.1MMJACKTHM")
      (footprint "eagle-import:PJ-102A")
      (libsource (lib "eagle-import") (part "2.1MMJACKTHM"))
    )
    (comp (ref "C1")
      (value ".1uF")
      (footprint "eagle-import:C0805")
      (libsource (lib "eagle-import") (part "C-USC0805"))
    )
    (comp (ref "C2")
      (value "2.2uF")
      (footprint "eagle-import:C0805")
      (libsource (lib "eagle-import") (part "C-USC0805"))
    )
    (comp (ref "VOLTAGE_REG")
      (value "TLS850B0TBV33ATMA1")
      (footprint "eagle-import:TLS850B0TBV33ATMA1")
      (fields (field (name "MOUSER_PART_NUMBER") "726-TLS850B0TBV33ATM"))
      (libsource (lib "eagle-import") (part "TLS850B0TBV33ATMA1"))
    )
    (comp (ref "C9")
      (value ".1uF")
      (footprint "eagle-import:C0805")
      (libsource (lib "eagle-import") (part "C-USC0805"))
    )
    (comp (ref "C10")
      (value ".1uF")
      (footprint "eagle-import:C0805")
      (libsource (lib "eagle-import") (part "C-USC0805"))
    )
    (comp (ref "C11")
      (value ".1uF")
      (footprint "eagle-import:C0805")
      (libsource (lib "eagle-import") (part "C-USC0805"))
    )
    (comp (ref "C12")
      (value ".1uF")
      (footprint "eagle-import:C0805")
      (libsource (lib "eagle-import") (part "C-USC0805"))
    )
    (comp (ref "R2")
      (value "500")
      (footprint "eagle-import:R0805")
      (libsource (lib "eagle-import") (part "R-US_R0805"))
    )
    (comp (ref "RL1")
      (value "4492__SK6805-EC_15_")
      (footprint "eagle-import:4492SK6805EC15")
      (fields (field (name "MANUFACTURER_PART_NUMBER") "4492 (SK6805-EC 15)"))
      (libsource (lib "eagle-import") (part "4492__SK6805-EC_15_"))
    )
    (comp (ref "RL2")
      (value "4492__SK6805-EC_15_")
      (footprint "eagle-import:4492SK6805EC15")
      (fields (field (name "MANUFACTURER_PART_NUMBER") "4492 (SK6805-EC 15)"))
      (libsource (lib "eagle-import") (part "4492__SK6805-EC_15_"))
    )
    (comp (ref "RL3")
      (value "4492__SK6805-EC_15_")
      (footprint "eagle-import:4492SK6805EC15")
      (fields (field (name "MANUFACTURER_PART_NUMBER") "4492 (SK6805-EC 15)"))
      (libsource (lib "eagle-import") (part "4492__SK6805-EC_15_"))
    )
    (comp (ref "RL4")
      (value "4492__SK6805-EC_15_")
      (footprint "eagle-import:4492SK6805EC15")
      (fields (field (name "MANUFACTURER_PART_NUMBER") "4492 (SK6805-EC 15)"))
      (libsource (lib "eagle-import") (part "4492__SK6805-EC_15_"))
    )
    (comp (ref "RL5")
      (value "4492__SK6805-EC_15_")
      (footprint "eagle-import:4492SK6805EC15")
      (fields (field (name "MANUFACTURER_PART_NUMBER") "4492 (SK6805-EC 15)"))
      (libsource (lib "eagle-import") (part "4492__SK6805-EC_15_"))
    )
    (comp (ref "RL6")
      (value "4492__SK6805-EC_15_")
      (footprint "eagle-import:4492SK6805EC15")
      (fields (field (name "MANUFACTURER_PART_NUMBER") "4492 (SK6805-EC 15)"))
      (libsource (lib "eagle-import") (part "4492__SK6805-EC_15_"))
    )
    (comp (ref "RL7")
      (value "4492__SK6805-EC_15_")
      (footprint "eagle-import:4492SK6805EC15")
      (fields (field (name "MANUFACTURER_PART_NUMBER") "4492 (SK6805-EC 15)"))
      (libsource (lib "eagle-import") (part "4492__SK6805-EC_15_"))
    )
    (comp (ref "RL8")
      (value "4492__SK6805-EC_15_")
      (footprint "eagle-import:4492SK6805EC15")
      (fields (field (name "MANUFACTURER_PART_NUMBER") "4492 (SK6805-EC 15)"))
      (libsource (lib "eagle-import") (part "4492__SK6805-EC_15_"))
    )
    (comp (ref "RL9")
      (value "4492__SK6805-EC_15_")
      (footprint "eagle-import:4492SK6805EC15")
      (fields (field (name "MANUFACTURER_PART_NUMBER") "4492 (SK6805-EC 15)"))
      (libsource (lib "eagle-import") (part "4492__SK6805-EC_15_"))
    )
    (comp (ref "RL10")
      (value "4492__SK6805-EC_15_")
      (footprint "eagle-import:4492SK6805EC15")
      (fields (field (name "MANUFACTURER_PART_NUMBER") "4492 (SK6805-EC 15)"))
      (libsource (lib "eagle-import") (part "4492__SK6805-EC_15_"))
    )
    (comp (ref "RL11")
      (value "4492__SK6805-EC_15_")
      (footprint "eagle-import:4492SK6805EC15")
      (fields (field (name "MANUFACTURER_PART_NUMBER") "4492 (SK6805-EC 15)"))
      (libsource (lib "eagle-import") (part "4492__SK6805-EC_15_"))
    )
    (comp (ref "RL12")
      (value "4492__SK6805-EC_15_")
      (footprint "eagle-import:4492SK6805EC15")
      (fields (field (name "MANUFACTURER_PART_NUMBER") "4492 (SK6805-EC 15)"))
      (libsource (lib "eagle-import") (part "4492__SK6805-EC_15_"))
    )
    (comp (ref "RL13")
      (value "4492__SK6805-EC_15_")
      (footprint "eagle-import:4492SK6805EC15")
      (fields (field (name "MANUFACTURER_PART_NUMBER") "4492 (SK6805-EC 15)"))
      (libsource (lib "eagle-import") (part "4492__SK6805-EC_15_"))
    )
    (comp (ref "RL14")
      (value "4492__SK6805-EC_15_")
      (footprint "eagle-import:4492SK6805EC15")
      (fields (field (name "MANUFACTURER_PART_NUMBER") "4492 (SK6805-EC 15)"))
      (libsource (lib "eagle-import") (part "4492__SK6805-EC_15_"))
    )
    (comp (ref "RL15")
      (value "4492__SK6805-EC_15_")
      (footprint "eagle-import:4492SK6805EC15")
      (fields (field (name "MANUFACTURER_PART_NUMBER") "4492 (SK6805-EC 15)"))
      (libsource (lib "eagle-import") (part "4492__SK6805-EC_15_"))
    )
    (comp (ref "RL16")
      (value "4492__SK6805-EC_15_")
      (footprint "eagle-import:4492SK6805EC15")
      (fields (field (name "MANUFACTURER_PART_NUMBER") "4492 (SK6805-EC 15)"))
      (libsource (lib "eagle-import") (part "4492__SK6805-EC_15_"))
    )
    (comp (ref "RL17")
      (value "4492__SK6805-EC_15_")
      (footprint "eagle-import:4492SK6805EC15")
      (fields (field (name "MANUFACTURER_PART_NUMBER") "4492 (SK6805-EC 15)"))
      (libsource (lib "eagle-import") (part "4492__SK6805-EC_15_"))
    )
    (comp (ref "RL18")
      (value "4492__SK6805-EC_15_")
      (footprint "eagle-import:4492SK6805EC15")
      (fields (field (name "MANUFACTURER_PART_NUMBER") "4492 (SK6805-EC 15)"))
      (libsource (lib "eagle-import") (part "4492__SK6805-EC_15_"))
    )
    (comp (ref "RL19")
      (value "4492__SK6805-EC_15_")
      (footprint "eagle-import:4492SK6805EC15")
      (fields (field (name "MANUFACTURER_PART_NUMBER") "4492 (SK6805-EC 15)"))
      (libsource (lib "eagle-import") (part "4492__SK6805-EC_15_"))
    )
    (comp (ref "RL20")
      (value "4492__SK6805-EC_15_")
      (footprint "eagle-import:4492SK6805EC15")
      (fields (field (name "MANUFACTURER_PART_NUMBER") "4492 (SK6805-EC 15)"))
      (libsource (lib "eagle-import") (part "4492__SK6805-EC_15_"))
    )
    (comp (ref "RL21")
      (value "4492__SK6805-EC_15_")
      (footprint "eagle-import:4492SK6805EC15")
      (fields (field (name "MANUFACTURER_PART_NUMBER") "4492 (SK6805-EC 15)"))
      (libsource (lib "eagle-import") (part "4492__SK6805-EC_15_"))
    )
    (comp (ref "RL22")
      (value "4492__SK6805-EC_15_")
      (footprint "eagle-import:4492SK6805EC15")
      (fields (field (name "MANUFACTURER_PART_NUMBER") "4492 (SK6805-EC 15)"))
      (libsource (lib "eagle-import") (part "4492__SK6805-EC_15_"))
    )
    (comp (ref "RL23")
      (value "4492__SK6805-EC_15_")
      (footprint "eagle-import:4492SK6805EC15")
      (fields (field (name "MANUFACTURER_PART_NUMBER") "4492 (SK6805-EC 15)"))
      (libsource (lib "eagle-import") (part "4492__SK6805-EC_15_"))
    )
    (comp (ref "RL24")
      (value "4492__SK6805-EC_15_")
      (footprint "eagle-import:4492SK6805EC15")
      (fields (field (name "MANUFACTURER_PART_NUMBER") "4492 (SK6805-EC 15)"))
      (libsource (lib "eagle-import") (part "4492__SK6805-EC_15_"))
    )
    (comp (ref "RL25")
      (value "4492__SK6805-EC_15_")
      (footprint "eagle-import:4492SK6805EC15")
      (fields (field (name "MANUFACTURER_PART_NUMBER") "4492 (SK6805-EC 15)"))
      (libsource (lib "eagle-import") (part "4492__SK6805-EC_15_"))
    )
    (comp (ref "RL26")
      (value "4492__SK6805-EC_15_")
      (footprint "eagle-import:4492SK6805EC15")
      (fields (field (name "MANUFACTURER_PART_NUMBER") "4492 (SK6805-EC 15)"))
      (libsource (lib "eagle-import") (part "4492__SK6805-EC_15_"))
    )
    (comp (ref "RL27")
      (value "4492__SK6805-EC_15_")
      (footprint "eagle-import:4492SK6805EC15")
      (fields (field (name "MANUFACTURER_PART_NUMBER") "4492 (SK6805-EC 15)"))
      (libsource (lib "eagle-import") (part "4492__SK6805-EC_15_"))
    )
    (comp (ref "C16")
      (value ".1uF")
      (footprint "eagle-import:C0805")
      (libsource (lib "eagle-import") (part "C-USC0805"))
    )
    (comp (ref "C17")
      (value ".1uF")
      (footprint "eagle-import:C0805")
      (libsource (lib "eagle-import") (part "C-USC0805"))
    )
    (comp (ref "C18")
      (value ".1uF")
      (footprint "eagle-import:C0805")
      (libsource (lib "eagle-import") (part "C-USC0805"))
    )
    (comp (ref "C19")
      (value ".1uF")
      (footprint "eagle-import:C0805")
      (libsource (lib "eagle-import") (part "C-USC0805"))
    )
    (comp (ref "GL1")
      (value "4492__SK6805-EC_15_")
      (footprint "eagle-import:4492SK6805EC15")
      (fields (field (name "MANUFACTURER_PART_NUMBER") "4492 (SK6805-EC 15)"))
      (libsource (lib "eagle-import") (part "4492__SK6805-EC_15_"))
    )
    (comp (ref "GL2")
      (value "4492__SK6805-EC_15_")
      (footprint "eagle-import:4492SK6805EC15")
      (fields (field (name "MANUFACTURER_PART_NUMBER") "4492 (SK6805-EC 15)"))
      (libsource (lib "eagle-import") (part "4492__SK6805-EC_15_"))
    )
    (comp (ref "GL3")
      (value "4492__SK6805-EC_15_")
      (footprint "eagle-import:4492SK6805EC15")
      (fields (field (name "MANUFACTURER_PART_NUMBER") "4492 (SK6805-EC 15)"))
      (libsource (lib "eagle-import") (part "4492__SK6805-EC_15_"))
    )
    (comp (ref "GL4")
      (value "4492__SK6805-EC_15_")
      (footprint "eagle-import:4492SK6805EC15")
      (fields (field (name "MANUFACTURER_PART_NUMBER") "4492 (SK6805-EC 15)"))
      (libsource (lib "eagle-import") (part "4492__SK6805-EC_15_"))
    )
    (comp (ref "GL5")
      (value "4492__SK6805-EC_15_")
      (footprint "eagle-import:4492SK6805EC15")
      (fields (field (name "MANUFACTURER_PART_NUMBER") "4492 (SK6805-EC 15)"))
      (libsource (lib "eagle-import") (part "4492__SK6805-EC_15_"))
    )
    (comp (ref "GL6")
      (value "4492__SK6805-EC_15_")
      (footprint "eagle-import:4492SK6805EC15")
      (fields (field (name "MANUFACTURER_PART_NUMBER") "4492 (SK6805-EC 15)"))
      (libsource (lib "eagle-import") (part "4492__SK6805-EC_15_"))
    )
    (comp (ref "GL7")
      (value "4492__SK6805-EC_15_")
      (footprint "eagle-import:4492SK6805EC15")
      (fields (field (name "MANUFACTURER_PART_NUMBER") "4492 (SK6805-EC 15)"))
      (libsource (lib "eagle-import") (part "4492__SK6805-EC_15_"))
    )
    (comp (ref "GL8")
      (value "4492__SK6805-EC_15_")
      (footprint "eagle-import:4492SK6805EC15")
      (fields (field (name "MANUFACTURER_PART_NUMBER") "4492 (SK6805-EC 15)"))
      (libsource (lib "eagle-import") (part "4492__SK6805-EC_15_"))
    )
    (comp (ref "GL9")
      (value "4492__SK6805-EC_15_")
      (footprint "eagle-import:4492SK6805EC15")
      (fields (field (name "MANUFACTURER_PART_NUMBER") "4492 (SK6805-EC 15)"))
      (libsource (lib "eagle-import") (part "4492__SK6805-EC_15_"))
    )
    (comp (ref "GL10")
      (value "4492__SK6805-EC_15_")
      (footprint "eagle-import:4492SK6805EC15")
      (fields (field (name "MANUFACTURER_PART_NUMBER") "4492 (SK6805-EC 15)"))
      (libsource (lib "eagle-import") (part "4492__SK6805-EC_15_"))
    )
    (comp (ref "GL11")
      (value "4492__SK6805-EC_15_")
      (footprint "eagle-import:4492SK6805EC15")
      (fields (field (name "MANUFACTURER_PART_NUMBER") "4492 (SK6805-EC 15)"))
      (libsource (lib "eagle-import") (part "4492__SK6805-EC_15_"))
    )
    (comp (ref "GL12")
      (value "4492__SK6805-EC_15_")
      (footprint "eagle-import:4492SK6805EC15")
      (fields (field (name "MANUFACTURER_PART_NUMBER") "4492 (SK6805-EC 15)"))
      (libsource (lib "eagle-import") (part "4492__SK6805-EC_15_"))
    )
    (comp (ref "GL13")
      (value "4492__SK6805-EC_15_")
      (footprint "eagle-import:4492SK6805EC15")
      (fields (field (name "MANUFACTURER_PART_NUMBER") "4492 (SK6805-EC 15)"))
      (libsource (lib "eagle-import") (part "4492__SK6805-EC_15_"))
    )
    (comp (ref "GL14")
      (value "4492__SK6805-EC_15_")
      (footprint "eagle-import:4492SK6805EC15")
      (fields (field (name "MANUFACTURER_PART_NUMBER") "4492 (SK6805-EC 15)"))
      (libsource (lib "eagle-import") (part "4492__SK6805-EC_15_"))
    )
    (comp (ref "GL15")
      (value "4492__SK6805-EC_15_")
      (footprint "eagle-import:4492SK6805EC15")
      (fields (field (name "MANUFACTURER_PART_NUMBER") "4492 (SK6805-EC 15)"))
      (libsource (lib "eagle-import") (part "4492__SK6805-EC_15_"))
    )
    (comp (ref "GL16")
      (value "4492__SK6805-EC_15_")
      (footprint "eagle-import:4492SK6805EC15")
      (fields (field (name "MANUFACTURER_PART_NUMBER") "4492 (SK6805-EC 15)"))
      (libsource (lib "eagle-import") (part "4492__SK6805-EC_15_"))
    )
    (comp (ref "GL17")
      (value "4492__SK6805-EC_15_")
      (footprint "eagle-import:4492SK6805EC15")
      (fields (field (name "MANUFACTURER_PART_NUMBER") "4492 (SK6805-EC 15)"))
      (libsource (lib "eagle-import") (part "4492__SK6805-EC_15_"))
    )
    (comp (ref "GL18")
      (value "4492__SK6805-EC_15_")
      (footprint "eagle-import:4492SK6805EC15")
      (fields (field (name "MANUFACTURER_PART_NUMBER") "4492 (SK6805-EC 15)"))
      (libsource (lib "eagle-import") (part "4492__SK6805-EC_15_"))
    )
    (comp (ref "GL19")
      (value "4492__SK6805-EC_15_")
      (footprint "eagle-import:4492SK6805EC15")
      (fields (field (name "MANUFACTURER_PART_NUMBER") "4492 (SK6805-EC 15)"))
      (libsource (lib "eagle-import") (part "4492__SK6805-EC_15_"))
    )
    (comp (ref "GL20")
      (value "4492__SK6805-EC_15_")
      (footprint "eagle-import:4492SK6805EC15")
      (fields (field (name "MANUFACTURER_PART_NUMBER") "4492 (SK6805-EC 15)"))
      (libsource (lib "eagle-import") (part "4492__SK6805-EC_15_"))
    )
    (comp (ref "GL21")
      (value "4492__SK6805-EC_15_")
      (footprint "eagle-import:4492SK6805EC15")
      (fields (field (name "MANUFACTURER_PART_NUMBER") "4492 (SK6805-EC 15)"))
      (libsource (lib "eagle-import") (part "4492__SK6805-EC_15_"))
    )
    (comp (ref "GL22")
      (value "4492__SK6805-EC_15_")
      (footprint "eagle-import:4492SK6805EC15")
      (fields (field (name "MANUFACTURER_PART_NUMBER") "4492 (SK6805-EC 15)"))
      (libsource (lib "eagle-import") (part "4492__SK6805-EC_15_"))
    )
    (comp (ref "GL23")
      (value "4492__SK6805-EC_15_")
      (footprint "eagle-import:4492SK6805EC15")
      (fields (field (name "MANUFACTURER_PART_NUMBER") "4492 (SK6805-EC 15)"))
      (libsource (lib "eagle-import") (part "4492__SK6805-EC_15_"))
    )
    (comp (ref "GL24")
      (value "4492__SK6805-EC_15_")
      (footprint "eagle-import:4492SK6805EC15")
      (fields (field (name "MANUFACTURER_PART_NUMBER") "4492 (SK6805-EC 15)"))
      (libsource (lib "eagle-import") (part "4492__SK6805-EC_15_"))
    )
    (comp (ref "GL25")
      (value "4492__SK6805-EC_15_")
      (footprint "eagle-import:4492SK6805EC15")
      (fields (field (name "MANUFACTURER_PART_NUMBER") "4492 (SK6805-EC 15)"))
      (libsource (lib "eagle-import") (part "4492__SK6805-EC_15_"))
    )
    (comp (ref "GL26")
      (value "4492__SK6805-EC_15_")
      (footprint "eagle-import:4492SK6805EC15")
      (fields (field (name "MANUFACTURER_PART_NUMBER") "4492 (SK6805-EC 15)"))
      (libsource (lib "eagle-import") (part "4492__SK6805-EC_15_"))
    )
    (comp (ref "GL27")
      (value "4492__SK6805-EC_15_")
      (footprint "eagle-import:4492SK6805EC15")
      (fields (field (name "MANUFACTURER_PART_NUMBER") "4492 (SK6805-EC 15)"))
      (libsource (lib "eagle-import") (part "4492__SK6805-EC_15_"))
    )
    (comp (ref "GL28")
      (value "4492__SK6805-EC_15_")
      (footprint "eagle-import:4492SK6805EC15")
      (fields (field (name "MANUFACTURER_PART_NUMBER") "4492 (SK6805-EC 15)"))
      (libsource (lib "eagle-import") (part "4492__SK6805-EC_15_"))
    )
    (comp (ref "GL29")
      (value "4492__SK6805-EC_15_")
      (footprint "eagle-import:4492SK6805EC15")
      (fields (field (name "MANUFACTURER_PART_NUMBER") "4492 (SK6805-EC 15)"))
      (libsource (lib "eagle-import") (part "4492__SK6805-EC_15_"))
    )
    (comp (ref "GL30")
      (value "4492__SK6805-EC_15_")
      (footprint "eagle-import:4492SK6805EC15")
      (fields (field (name "MANUFACTURER_PART_NUMBER") "4492 (SK6805-EC 15)"))
      (libsource (lib "eagle-import") (part "4492__SK6805-EC_15_"))
    )
    (comp (ref "R4")
      (value "500")
      (footprint "eagle-import:R0805")
      (libsource (lib "eagle-import") (part "R-US_R0805"))
    )
    (comp (ref "BL1")
      (value "4492__SK6805-EC_15_")
      (footprint "eagle-import:4492SK6805EC15")
      (fields (field (name "MANUFACTURER_PART_NUMBER") "4492 (SK6805-EC 15)"))
      (libsource (lib "eagle-import") (part "4492__SK6805-EC_15_"))
    )
    (comp (ref "BL2")
      (value "4492__SK6805-EC_15_")
      (footprint "eagle-import:4492SK6805EC15")
      (fields (field (name "MANUFACTURER_PART_NUMBER") "4492 (SK6805-EC 15)"))
      (libsource (lib "eagle-import") (part "4492__SK6805-EC_15_"))
    )
    (comp (ref "BL3")
      (value "4492__SK6805-EC_15_")
      (footprint "eagle-import:4492SK6805EC15")
      (fields (field (name "MANUFACTURER_PART_NUMBER") "4492 (SK6805-EC 15)"))
      (libsource (lib "eagle-import") (part "4492__SK6805-EC_15_"))
    )
    (comp (ref "BL4")
      (value "4492__SK6805-EC_15_")
      (footprint "eagle-import:4492SK6805EC15")
      (fields (field (name "MANUFACTURER_PART_NUMBER") "4492 (SK6805-EC 15)"))
      (libsource (lib "eagle-import") (part "4492__SK6805-EC_15_"))
    )
    (comp (ref "BL5")
      (value "4492__SK6805-EC_15_")
      (footprint "eagle-import:4492SK6805EC15")
      (fields (field (name "MANUFACTURER_PART_NUMBER") "4492 (SK6805-EC 15)"))
      (libsource (lib "eagle-import") (part "4492__SK6805-EC_15_"))
    )
    (comp (ref "BL6")
      (value "4492__SK6805-EC_15_")
      (footprint "eagle-import:4492SK6805EC15")
      (fields (field (name "MANUFACTURER_PART_NUMBER") "4492 (SK6805-EC 15)"))
      (libsource (lib "eagle-import") (part "4492__SK6805-EC_15_"))
    )
    (comp (ref "BL7")
      (value "4492__SK6805-EC_15_")
      (footprint "eagle-import:4492SK6805EC15")
      (fields (field (name "MANUFACTURER_PART_NUMBER") "4492 (SK6805-EC 15)"))
      (libsource (lib "eagle-import") (part "4492__SK6805-EC_15_"))
    )
    (comp (ref "BL8")
      (value "4492__SK6805-EC_15_")
      (footprint "eagle-import:4492SK6805EC15")
      (fields (field (name "MANUFACTURER_PART_NUMBER") "4492 (SK6805-EC 15)"))
      (libsource (lib "eagle-import") (part "4492__SK6805-EC_15_"))
    )
    (comp (ref "BL9")
      (value "4492__SK6805-EC_15_")
      (footprint "eagle-import:4492SK6805EC15")
      (fields (field (name "MANUFACTURER_PART_NUMBER") "4492 (SK6805-EC 15)"))
      (libsource (lib "eagle-import") (part "4492__SK6805-EC_15_"))
    )
    (comp (ref "BL10")
      (value "4492__SK6805-EC_15_")
      (footprint "eagle-import:4492SK6805EC15")
      (fields (field (name "MANUFACTURER_PART_NUMBER") "4492 (SK6805-EC 15)"))
      (libsource (lib "eagle-import") (part "4492__SK6805-EC_15_"))
    )
    (comp (ref "BL11")
      (value "4492__SK6805-EC_15_")
      (footprint "eagle-import:4492SK6805EC15")
      (fields (field (name "MANUFACTURER_PART_NUMBER") "4492 (SK6805-EC 15)"))
      (libsource (lib "eagle-import") (part "4492__SK6805-EC_15_"))
    )
    (comp (ref "BL12")
      (value "4492__SK6805-EC_15_")
      (footprint "eagle-import:4492SK6805EC15")
      (fields (field (name "MANUFACTURER_PART_NUMBER") "4492 (SK6805-EC 15)"))
      (libsource (lib "eagle-import") (part "4492__SK6805-EC_15_"))
    )
    (comp (ref "BL13")
      (value "4492__SK6805-EC_15_")
      (footprint "eagle-import:4492SK6805EC15")
      (fields (field (name "MANUFACTURER_PART_NUMBER") "4492 (SK6805-EC 15)"))
      (libsource (lib "eagle-import") (part "4492__SK6805-EC_15_"))
    )
    (comp (ref "BL14")
      (value "4492__SK6805-EC_15_")
      (footprint "eagle-import:4492SK6805EC15")
      (fields (field (name "MANUFACTURER_PART_NUMBER") "4492 (SK6805-EC 15)"))
      (libsource (lib "eagle-import") (part "4492__SK6805-EC_15_"))
    )
    (comp (ref "BL15")
      (value "4492__SK6805-EC_15_")
      (footprint "eagle-import:4492SK6805EC15")
      (fields (field (name "MANUFACTURER_PART_NUMBER") "4492 (SK6805-EC 15)"))
      (libsource (lib "eagle-import") (part "4492__SK6805-EC_15_"))
    )
    (comp (ref "BL16")
      (value "4492__SK6805-EC_15_")
      (footprint "eagle-import:4492SK6805EC15")
      (fields (field (name "MANUFACTURER_PART_NUMBER") "4492 (SK6805-EC 15)"))
      (libsource (lib "eagle-import") (part "4492__SK6805-EC_15_"))
    )
    (comp (ref "BL17")
      (value "4492__SK6805-EC_15_")
      (footprint "eagle-import:4492SK6805EC15")
      (fields (field (name "MANUFACTURER_PART_NUMBER") "4492 (SK6805-EC 15)"))
      (libsource (lib "eagle-import") (part "4492__SK6805-EC_15_"))
    )
    (comp (ref "BL18")
      (value "4492__SK6805-EC_15_")
      (footprint "eagle-import:4492SK6805EC15")
      (fields (field (name "MANUFACTURER_PART_NUMBER") "4492 (SK6805-EC 15)"))
      (libsource (lib "eagle-import") (part "4492__SK6805-EC_15_"))
    )
    (comp (ref "BL19")
      (value "4492__SK6805-EC_15_")
      (footprint "eagle-import:4492SK6805EC15")
      (fields (field (name "MANUFACTURER_PART_NUMBER") "4492 (SK6805-EC 15)"))
      (libsource (lib "eagle-import") (part "4492__SK6805-EC_15_"))
    )
    (comp (ref "BL20")
      (value "4492__SK6805-EC_15_")
      (footprint "eagle-import:4492SK6805EC15")
      (fields (field (name "MANUFACTURER_PART_NUMBER") "4492 (SK6805-EC 15)"))
      (libsource (lib "eagle-import") (part "4492__SK6805-EC_15_"))
    )
    (comp (ref "BL21")
      (value "4492__SK6805-EC_15_")
      (footprint "eagle-import:4492SK6805EC15")
      (fields (field (name "MANUFACTURER_PART_NUMBER") "4492 (SK6805-EC 15)"))
      (libsource (lib "eagle-import") (part "4492__SK6805-EC_15_"))
    )
    (comp (ref "BL22")
      (value "4492__SK6805-EC_15_")
      (footprint "eagle-import:4492SK6805EC15")
      (fields (field (name "MANUFACTURER_PART_NUMBER") "4492 (SK6805-EC 15)"))
      (libsource (lib "eagle-import") (part "4492__SK6805-EC_15_"))
    )
    (comp (ref "BL23")
      (value "4492__SK6805-EC_15_")
      (footprint "eagle-import:4492SK6805EC15")
      (fields (field (name "MANUFACTURER_PART_NUMBER") "4492 (SK6805-EC 15)"))
      (libsource (lib "eagle-import") (part "4492__SK6805-EC_15_"))
    )
    (comp (ref "BL24")
      (value "4492__SK6805-EC_15_")
      (footprint "eagle-import:4492SK6805EC15")
      (fields (field (name "MANUFACTURER_PART_NUMBER") "4492 (SK6805-EC 15)"))
      (libsource (lib "eagle-import") (part "4492__SK6805-EC_15_"))
    )
    (comp (ref "BL25")
      (value "4492__SK6805-EC_15_")
      (footprint "eagle-import:4492SK6805EC15")
      (fields (field (name "MANUFACTURER_PART_NUMBER") "4492 (SK6805-EC 15)"))
      (libsource (lib "eagle-import") (part "4492__SK6805-EC_15_"))
    )
    (comp (ref "BL26")
      (value "4492__SK6805-EC_15_")
      (footprint "eagle-import:4492SK6805EC15")
      (fields (field (name "MANUFACTURER_PART_NUMBER") "4492 (SK6805-EC 15)"))
      (libsource (lib "eagle-import") (part "4492__SK6805-EC_15_"))
    )
    (comp (ref "BL27")
      (value "4492__SK6805-EC_15_")
      (footprint "eagle-import:4492SK6805EC15")
      (fields (field (name "MANUFACTURER_PART_NUMBER") "4492 (SK6805-EC 15)"))
      (libsource (lib "eagle-import") (part "4492__SK6805-EC_15_"))
    )
    (comp (ref "BL28")
      (value "4492__SK6805-EC_15_")
      (footprint "eagle-import:4492SK6805EC15")
      (fields (field (name "MANUFACTURER_PART_NUMBER") "4492 (SK6805-EC 15)"))
      (libsource (lib "eagle-import") (part "4492__SK6805-EC_15_"))
    )
    (comp (ref "BL29")
      (value "4492__SK6805-EC_15_")
      (footprint "eagle-import:4492SK6805EC15")
      (fields (field (name "MANUFACTURER_PART_NUMBER") "4492 (SK6805-EC 15)"))
      (libsource (lib "eagle-import") (part "4492__SK6805-EC_15_"))
    )
    (comp (ref "BL30")
      (value "4492__SK6805-EC_15_")
      (footprint "eagle-import:4492SK6805EC15")
      (fields (field (name "MANUFACTURER_PART_NUMBER") "4492 (SK6805-EC 15)"))
      (libsource (lib "eagle-import") (part "4492__SK6805-EC_15_"))
    )
    (comp (ref "BL31")
      (value "4492__SK6805-EC_15_")
      (footprint "eagle-import:4492SK6805EC15")
      (fields (field (name "MANUFACTURER_PART_NUMBER") "4492 (SK6805-EC 15)"))
      (libsource (lib "eagle-import") (part "4492__SK6805-EC_15_"))
    )
    (comp (ref "BL32")
      (value "4492__SK6805-EC_15_")
      (footprint "eagle-import:4492SK6805EC15")
      (fields (field (name "MANUFACTURER_PART_NUMBER") "4492 (SK6805-EC 15)"))
      (libsource (lib "eagle-import") (part "4492__SK6805-EC_15_"))
    )
    (comp (ref "BL33")
      (value "4492__SK6805-EC_15_")
      (footprint "eagle-import:4492SK6805EC15")
      (fields (field (name "MANUFACTURER_PART_NUMBER") "4492 (SK6805-EC 15)"))
      (libsource (lib "eagle-import") (part "4492__SK6805-EC_15_"))
    )
    (comp (ref "BL34")
      (value "4492__SK6805-EC_15_")
      (footprint "eagle-import:4492SK6805EC15")
      (fields (field (name "MANUFACTURER_PART_NUMBER") "4492 (SK6805-EC 15)"))
      (libsource (lib "eagle-import") (part "4492__SK6805-EC_15_"))
    )
    (comp (ref "BL35")
      (value "4492__SK6805-EC_15_")
      (footprint "eagle-import:4492SK6805EC15")
      (fields (field (name "MANUFACTURER_PART_NUMBER") "4492 (SK6805-EC 15)"))
      (libsource (lib "eagle-import") (part "4492__SK6805-EC_15_"))
    )
    (comp (ref "BL36")
      (value "4492__SK6805-EC_15_")
      (footprint "eagle-import:4492SK6805EC15")
      (fields (field (name "MANUFACTURER_PART_NUMBER") "4492 (SK6805-EC 15)"))
      (libsource (lib "eagle-import") (part "4492__SK6805-EC_15_"))
    )
    (comp (ref "BL37")
      (value "4492__SK6805-EC_15_")
      (footprint "eagle-import:4492SK6805EC15")
      (fields (field (name "MANUFACTURER_PART_NUMBER") "4492 (SK6805-EC 15)"))
      (libsource (lib "eagle-import") (part "4492__SK6805-EC_15_"))
    )
    (comp (ref "BL38")
      (value "4492__SK6805-EC_15_")
      (footprint "eagle-import:4492SK6805EC15")
      (fields (field (name "MANUFACTURER_PART_NUMBER") "4492 (SK6805-EC 15)"))
      (libsource (lib "eagle-import") (part "4492__SK6805-EC_15_"))
    )
    (comp (ref "BL39")
      (value "4492__SK6805-EC_15_")
      (footprint "eagle-import:4492SK6805EC15")
      (fields (field (name "MANUFACTURER_PART_NUMBER") "4492 (SK6805-EC 15)"))
      (libsource (lib "eagle-import") (part "4492__SK6805-EC_15_"))
    )
    (comp (ref "BL40")
      (value "4492__SK6805-EC_15_")
      (footprint "eagle-import:4492SK6805EC15")
      (fields (field (name "MANUFACTURER_PART_NUMBER") "4492 (SK6805-EC 15)"))
      (libsource (lib "eagle-import") (part "4492__SK6805-EC_15_"))
    )
    (comp (ref "BL41")
      (value "4492__SK6805-EC_15_")
      (footprint "eagle-import:4492SK6805EC15")
      (fields (field (name "MANUFACTURER_PART_NUMBER") "4492 (SK6805-EC 15)"))
      (libsource (lib "eagle-import") (part "4492__SK6805-EC_15_"))
    )
    (comp (ref "BL42")
      (value "4492__SK6805-EC_15_")
      (footprint "eagle-import:4492SK6805EC15")
      (fields (field (name "MANUFACTURER_PART_NUMBER") "4492 (SK6805-EC 15)"))
      (libsource (lib "eagle-import") (part "4492__SK6805-EC_15_"))
    )
    (comp (ref "BL43")
      (value "4492__SK6805-EC_15_")
      (footprint "eagle-import:4492SK6805EC15")
      (fields (field (name "MANUFACTURER_PART_NUMBER") "4492 (SK6805-EC 15)"))
      (libsource (lib "eagle-import") (part "4492__SK6805-EC_15_"))
    )
    (comp (ref "BL44")
      (value "4492__SK6805-EC_15_")
      (footprint "eagle-import:4492SK6805EC15")
      (fields (field (name "MANUFACTURER_PART_NUMBER") "4492 (SK6805-EC 15)"))
      (libsource (lib "eagle-import") (part "4492__SK6805-EC_15_"))
    )
    (comp (ref "BL45")
      (value "4492__SK6805-EC_15_")
      (footprint "eagle-import:4492SK6805EC15")
      (fields (field (name "MANUFACTURER_PART_NUMBER") "4492 (SK6805-EC 15)"))
      (libsource (lib "eagle-import") (part "4492__SK6805-EC_15_"))
    )
    (comp (ref "BL46")
      (value "4492__SK6805-EC_15_")
      (footprint "eagle-import:4492SK6805EC15")
      (fields (field (name "MANUFACTURER_PART_NUMBER") "4492 (SK6805-EC 15)"))
      (libsource (lib "eagle-import") (part "4492__SK6805-EC_15_"))
    )
    (comp (ref "BL47")
      (value "4492__SK6805-EC_15_")
      (footprint "eagle-import:4492SK6805EC15")
      (fields (field (name "MANUFACTURER_PART_NUMBER") "4492 (SK6805-EC 15)"))
      (libsource (lib "eagle-import") (part "4492__SK6805-EC_15_"))
    )
    (comp (ref "BL48")
      (value "4492__SK6805-EC_15_")
      (footprint "eagle-import:4492SK6805EC15")
      (fields (field (name "MANUFACTURER_PART_NUMBER") "4492 (SK6805-EC 15)"))
      (libsource (lib "eagle-import") (part "4492__SK6805-EC_15_"))
    )
    (comp (ref "BL49")
      (value "4492__SK6805-EC_15_")
      (footprint "eagle-import:4492SK6805EC15")
      (fields (field (name "MANUFACTURER_PART_NUMBER") "4492 (SK6805-EC 15)"))
      (libsource (lib "eagle-import") (part "4492__SK6805-EC_15_"))
    )
    (comp (ref "C3")
      (value ".1uF")
      (footprint "eagle-import:C0805")
      (libsource (lib "eagle-import") (part "C-USC0805"))
    )
    (comp (ref "C4")
      (value ".1uF")
      (footprint "eagle-import:C0805")
      (libsource (lib "eagle-import") (part "C-USC0805"))
    )
    (comp (ref "C5")
      (value ".1uF")
      (footprint "eagle-import:C0805")
      (libsource (lib "eagle-import") (part "C-USC0805"))
    )
    (comp (ref "C6")
      (value ".1uF")
      (footprint "eagle-import:C0805")
      (libsource (lib "eagle-import") (part "C-USC0805"))
    )
    (comp (ref "C7")
      (value ".1uF")
      (footprint "eagle-import:C0805")
      (libsource (lib "eagle-import") (part "C-USC0805"))
    )
    (comp (ref "C8")
      (value ".1uF")
      (footprint "eagle-import:C0805")
      (libsource (lib "eagle-import") (part "C-USC0805"))
    )
    (comp (ref "R1")
      (value "500")
      (footprint "eagle-import:R0805")
      (libsource (lib "eagle-import") (part "R-US_R0805"))
    )
    (comp (ref "C20")
      (value ".1uF")
      (footprint "eagle-import:C0805")
      (libsource (lib "eagle-import") (part "C-USC0805"))
    )
    (comp (ref "C21")
      (value ".1uF")
      (footprint "eagle-import:C0805")
      (libsource (lib "eagle-import") (part "C-USC0805"))
    )
    (comp (ref "C22")
      (value ".1uF")
      (footprint "eagle-import:C0805")
      (libsource (lib "eagle-import") (part "C-USC0805"))
    )
    (comp (ref "OL1")
      (value "4492__SK6805-EC_15_")
      (footprint "eagle-import:4492SK6805EC15")
      (fields (field (name "MANUFACTURER_PART_NUMBER") "4492 (SK6805-EC 15)"))
      (libsource (lib "eagle-import") (part "4492__SK6805-EC_15_"))
    )
    (comp (ref "OL2")
      (value "4492__SK6805-EC_15_")
      (footprint "eagle-import:4492SK6805EC15")
      (fields (field (name "MANUFACTURER_PART_NUMBER") "4492 (SK6805-EC 15)"))
      (libsource (lib "eagle-import") (part "4492__SK6805-EC_15_"))
    )
    (comp (ref "OL3")
      (value "4492__SK6805-EC_15_")
      (footprint "eagle-import:4492SK6805EC15")
      (fields (field (name "MANUFACTURER_PART_NUMBER") "4492 (SK6805-EC 15)"))
      (libsource (lib "eagle-import") (part "4492__SK6805-EC_15_"))
    )
    (comp (ref "OL4")
      (value "4492__SK6805-EC_15_")
      (footprint "eagle-import:4492SK6805EC15")
      (fields (field (name "MANUFACTURER_PART_NUMBER") "4492 (SK6805-EC 15)"))
      (libsource (lib "eagle-import") (part "4492__SK6805-EC_15_"))
    )
    (comp (ref "OL5")
      (value "4492__SK6805-EC_15_")
      (footprint "eagle-import:4492SK6805EC15")
      (fields (field (name "MANUFACTURER_PART_NUMBER") "4492 (SK6805-EC 15)"))
      (libsource (lib "eagle-import") (part "4492__SK6805-EC_15_"))
    )
    (comp (ref "OL6")
      (value "4492__SK6805-EC_15_")
      (footprint "eagle-import:4492SK6805EC15")
      (fields (field (name "MANUFACTURER_PART_NUMBER") "4492 (SK6805-EC 15)"))
      (libsource (lib "eagle-import") (part "4492__SK6805-EC_15_"))
    )
    (comp (ref "OL7")
      (value "4492__SK6805-EC_15_")
      (footprint "eagle-import:4492SK6805EC15")
      (fields (field (name "MANUFACTURER_PART_NUMBER") "4492 (SK6805-EC 15)"))
      (libsource (lib "eagle-import") (part "4492__SK6805-EC_15_"))
    )
    (comp (ref "OL8")
      (value "4492__SK6805-EC_15_")
      (footprint "eagle-import:4492SK6805EC15")
      (fields (field (name "MANUFACTURER_PART_NUMBER") "4492 (SK6805-EC 15)"))
      (libsource (lib "eagle-import") (part "4492__SK6805-EC_15_"))
    )
    (comp (ref "OL9")
      (value "4492__SK6805-EC_15_")
      (footprint "eagle-import:4492SK6805EC15")
      (fields (field (name "MANUFACTURER_PART_NUMBER") "4492 (SK6805-EC 15)"))
      (libsource (lib "eagle-import") (part "4492__SK6805-EC_15_"))
    )
    (comp (ref "OL10")
      (value "4492__SK6805-EC_15_")
      (footprint "eagle-import:4492SK6805EC15")
      (fields (field (name "MANUFACTURER_PART_NUMBER") "4492 (SK6805-EC 15)"))
      (libsource (lib "eagle-import") (part "4492__SK6805-EC_15_"))
    )
    (comp (ref "OL11")
      (value "4492__SK6805-EC_15_")
      (footprint "eagle-import:4492SK6805EC15")
      (fields (field (name "MANUFACTURER_PART_NUMBER") "4492 (SK6805-EC 15)"))
      (libsource (lib "eagle-import") (part "4492__SK6805-EC_15_"))
    )
    (comp (ref "OL12")
      (value "4492__SK6805-EC_15_")
      (footprint "eagle-import:4492SK6805EC15")
      (fields (field (name "MANUFACTURER_PART_NUMBER") "4492 (SK6805-EC 15)"))
      (libsource (lib "eagle-import") (part "4492__SK6805-EC_15_"))
    )
    (comp (ref "OL13")
      (value "4492__SK6805-EC_15_")
      (footprint "eagle-import:4492SK6805EC15")
      (fields (field (name "MANUFACTURER_PART_NUMBER") "4492 (SK6805-EC 15)"))
      (libsource (lib "eagle-import") (part "4492__SK6805-EC_15_"))
    )
    (comp (ref "OL14")
      (value "4492__SK6805-EC_15_")
      (footprint "eagle-import:4492SK6805EC15")
      (fields (field (name "MANUFACTURER_PART_NUMBER") "4492 (SK6805-EC 15)"))
      (libsource (lib "eagle-import") (part "4492__SK6805-EC_15_"))
    )
    (comp (ref "OL15")
      (value "4492__SK6805-EC_15_")
      (footprint "eagle-import:4492SK6805EC15")
      (fields (field (name "MANUFACTURER_PART_NUMBER") "4492 (SK6805-EC 15)"))
      (libsource (lib "eagle-import") (part "4492__SK6805-EC_15_"))
    )
    (comp (ref "OL16")
      (value "4492__SK6805-EC_15_")
      (footprint "eagle-import:4492SK6805EC15")
      (fields (field (name "MANUFACTURER_PART_NUMBER") "4492 (SK6805-EC 15)"))
      (libsource (lib "eagle-import") (part "4492__SK6805-EC_15_"))
    )
    (comp (ref "OL17")
      (value "4492__SK6805-EC_15_")
      (footprint "eagle-import:4492SK6805EC15")
      (fields (field (name "MANUFACTURER_PART_NUMBER") "4492 (SK6805-EC 15)"))
      (libsource (lib "eagle-import") (part "4492__SK6805-EC_15_"))
    )
    (comp (ref "R5")
      (value "500")
      (footprint "eagle-import:R0805")
      (libsource (lib "eagle-import") (part "R-US_R0805"))
    )
    (comp (ref "IC1")
      (value "TXU0304PWR")
      (footprint "eagle-import:SOP65P640X120-14N")
      (fields (field (name "MOUSER_PART_NUMBER") "595-TXU0304PWR"))
      (libsource (lib "eagle-import") (part "TXU0304PWR"))
    )
    (comp (ref "IC2")
      (value "TXU0304PWR")
      (footprint "eagle-import:SOP65P640X120-14N")
      (fields (field (name "MOUSER_PART_NUMBER") "595-TXU0304PWR"))
      (libsource (lib "eagle-import") (part "TXU0304PWR"))
    )
    (comp (ref "JP1")
      (value "PINHD-1X2")
      (footprint "eagle-import:1X02")
      (libsource (lib "eagle-import") (part "PINHD-1X2"))
    )
    (comp (ref "U1")
      (value "ESP32-DEVKITC-32D")
      (footprint "eagle-import:MODULE_ESP32-DEVKITC-32D")
      (fields (field (name "MF") "Espressif Systems"))
      (libsource (lib "eagle-import") (part "ESP32-DEVKITC-32D"))
    )
  )
  (nets
    (net (code "1") (name "+3V3") (class "Default")
      (node (ref "C2") (pin "1") (pinfunction "1_1") (pintype "passive"))
      (node (ref "IC1") (pin "1") (pinfunction "VCCA_1") (pintype "bidirectional"))
      (node (ref "IC2") (pin "1") (pinfunction "VCCA_1") (pintype "bidirectional"))
      (node (ref "JP1") (pin "1") (pinfunction "1_1") (pintype "passive"))
      (node (ref "VOLTAGE_REG") (pin "5") (pinfunction "Q_5") (pintype "bidirectional"))
    )
    (net (code "2") (name "+5V") (class "Default")
      (node (ref "BARREL_JACK1") (pin "TIP") (pinfunction "TIP_TIP") (pintype "bidirectional"))
      (node (ref "BL1") (pin "2") (pinfunction "VDD_2") (pintype "bidirectional"))
      (node (ref "BL10") (pin "2") (pinfunction "VDD_2") (pintype "bidirectional"))
      (node (ref "BL11") (pin "2") (pinfunction "VDD_2") (pintype "bidirectional"))
      (node (ref "BL12") (pin "2") (pinfunction "VDD_2") (pintype "bidirectional"))
      (node (ref "BL13") (pin "2") (pinfunction "VDD_2") (pintype "bidirectional"))
      (node (ref "BL14") (pin "2") (pinfunction "VDD_2") (pintype "bidirectional"))
      (node (ref "BL15") (pin "2") (pinfunction "VDD_2") (pintype "bidirectional"))
      (node (ref "BL16") (pin "2") (pinfunction "VDD_2") (pintype "bidirectional"))
      (node (ref "BL17") (pin "2") (pinfunction "VDD_2") (pintype "bidirectional"))
      (node (ref "BL18") (pin "2") (pinfunction "VDD_2") (pintype "bidirectional"))
      (node (ref "BL19") (pin "2") (pinfunction "VDD_2") (pintype "bidirectional"))
      (node (ref "BL2") (pin "2") (pinfunction "VDD_2") (pintype "bidirectional"))
      (node (ref "BL20") (pin "2") (pinfunction "VDD_2") (pintype "bidirectional"))
      (node (ref "BL21") (pin "2") (pinfunction "VDD_2") (pintype "bidirectional"))
      (node (ref "BL22") (pin "2") (pinfunction "VDD_2") (pintype "bidirectional"))
      (node (ref "BL23") (pin "2") (pinfunction "VDD_2") (pintype "bidirectional"))
      (node (ref "BL24") (pin "2") (pinfunction "VDD_2") (pintype "bidirectional"))
      (node (ref "BL25") (pin "2") (pinfunction "VDD_2") (pintype "bidirectional"))
      (node (ref "BL26") (pin "2") (pinfunction "VDD_2") (pintype "bidirectional"))
      (node (ref "BL27") (pin "2") (pinfunction "VDD_2") (pintype "bidirectional"))
      (node (ref "BL28") (pin "2") (pinfunction "VDD_2") (pintype "bidirectional"))
      (node (ref "BL29") (pin "2") (pinfunction "VDD_2") (pintype "bidirectional"))
      (node (ref "BL3") (pin "2") (pinfunction "VDD_2") (pintype "bidirectional"))
      (node (ref "BL30") (pin "2") (pinfunction "VDD_2") (pintype "bidirectional"))
      (node (ref "BL31") (pin "2") (pinfunction "VDD_2") (pintype "bidirectional"))
      (node (ref "BL32") (pin "2") (pinfunction "VDD_2") (pintype "bidirectional"))
      (node (ref "BL33") (pin "2") (pinfunction "VDD_2") (pintype "bidirectional"))
      (node (ref "BL34") (pin "2") (pinfunction "VDD_2") (pintype "bidirectional"))
      (node (ref "BL35") (pin "2") (pinfunction "VDD_2") (pintype "bidirectional"))
      (node (ref "BL36") (pin "2") (pinfunction "VDD_2") (pintype "bidirectional"))
      (node (ref "BL37") (pin "2") (pinfunction "VDD_2") (pintype "bidirectional"))
      (node (ref "BL38") (pin "2") (pinfunction "VDD_2") (pintype "bidirectional"))
      (node (ref "BL39") (pin "2") (pinfunction "VDD_2") (pintype "bidirectional"))
      (node (ref "BL4") (pin "2") (pinfunction "VDD_2") (pintype "bidirectional"))
      (node (ref "BL40") (pin "2") (pinfunction "VDD_2") (pintype "bidirectional"))
      (node (ref "BL41") (pin "2") (pinfunction "VDD_2") (pintype "bidirectional"))
      (node (ref "BL42") (pin "2") (pinfunction "VDD_2") (pintype "bidirectional"))
      (node (ref "BL43") (pin "2") (pinfunction "VDD_2") (pintype "bidirectional"))
      (node (ref "BL44") (pin "2") (pinfunction "VDD_2") (pintype "bidirectional"))
      (node (ref "BL45") (pin "2") (pinfunction "VDD_2") (pintype "bidirectional"))
      (node (ref "BL46") (pin "2") (pinfunction "VDD_2") (pintype "bidirectional"))
      (node (ref "BL47") (pin "2") (pinfunction "VDD_2") (pintype "bidirectional"))
      (node (ref "BL48") (pin "2") (pinfunction "VDD_2") (pintype "bidirectional"))
      (node (ref "BL49") (pin "2") (pinfunction "VDD_2") (pintype "bidirectional"))
      (node (ref "BL5") (pin "2") (pinfunction "VDD_2") (pintype "bidirectional"))
      (node (ref "BL6") (pin "2") (pinfunction "VDD_2") (pintype "bidirectional"))
      (node (ref "BL7") (pin "2") (pinfunction "VDD_2") (pintype "bidirectional"))
      (node (ref "BL8") (pin "2") (pinfunction "VDD_2") (pintype "bidirectional"))
      (node (ref "BL9") (pin "2") (pinfunction "VDD_2") (pintype "bidirectional"))
      (node (ref "C1") (pin "1") (pinfunction "1_1") (pintype "passive"))
      (node (ref "C10") (pin "1") (pinfunction "1_1") (pintype "passive"))
      (node (ref "C11") (pin "1") (pinfunction "1_1") (pintype "passive"))
      (node (ref "C12") (pin "1") (pinfunction "1_1") (pintype "passive"))
      (node (ref "C13") (pin "1") (pinfunction "1_1") (pintype "passive"))
      (node (ref "C14") (pin "1") (pinfunction "1_1") (pintype "passive"))
      (node (ref "C15") (pin "1") (pinfunction "1_1") (pintype "passive"))
      (node (ref "C16") (pin "1") (pinfunction "1_1") (pintype "passive"))
      (node (ref "C17") (pin "1") (pinfunction "1_1") (pintype "passive"))
      (node (ref "C18") (pin "1") (pinfunction "1_1") (pintype "passive"))
      (node (ref "C19") (pin "1") (pinfunction "1_1") (pintype "passive"))
      (node (ref "C20") (pin "1") (pinfunction "1_1") (pintype "passive"))
      (node (ref "C21") (pin "1") (pinfunction "1_1") (pintype "passive"))
      (node (ref "C22") (pin "1") (pinfunction "1_1") (pintype "passive"))
      (node (ref "C3") (pin "1") (pinfunction "1_1") (pintype "passive"))
      (node (ref "C4") (pin "1") (pinfunction "1_1") (pintype "passive"))
      (node (ref "C5") (pin "1") (pinfunction "1_1") (pintype "passive"))
      (node (ref "C6") (pin "1") (pinfunction "1_1") (pintype "passive"))
      (node (ref "C7") (pin "1") (pinfunction "1_1") (pintype "passive"))
      (node (ref "C8") (pin "1") (pinfunction "1_1") (pintype "passive"))
      (node (ref "C9") (pin "1") (pinfunction "1_1") (pintype "passive"))
      (node (ref "GL1") (pin "2") (pinfunction "VDD_2") (pintype "bidirectional"))
      (node (ref "GL10") (pin "2") (pinfunction "VDD_2") (pintype "bidirectional"))
      (node (ref "GL11") (pin "2") (pinfunction "VDD_2") (pintype "bidirectional"))
      (node (ref "GL12") (pin "2") (pinfunction "VDD_2") (pintype "bidirectional"))
      (node (ref "GL13") (pin "2") (pinfunction "VDD_2") (pintype "bidirectional"))
      (node (ref "GL14") (pin "2") (pinfunction "VDD_2") (pintype "bidirectional"))
      (node (ref "GL15") (pin "2") (pinfunction "VDD_2") (pintype "bidirectional"))
      (node (ref "GL16") (pin "2") (pinfunction "VDD_2") (pintype "bidirectional"))
      (node (ref "GL17") (pin "2") (pinfunction "VDD_2") (pintype "bidirectional"))
      (node (ref "GL18") (pin "2") (pinfunction "VDD_2") (pintype "bidirectional"))
      (node (ref "GL19") (pin "2") (pinfunction "VDD_2") (pintype "bidirectional"))
      (node (ref "GL2") (pin "2") (pinfunction "VDD_2") (pintype "bidirectional"))
      (node (ref "GL20") (pin "2") (pinfunction "VDD_2") (pintype "bidirectional"))
      (node (ref "GL21") (pin "2") (pinfunction "VDD_2") (pintype "bidirectional"))
      (node (ref "GL22") (pin "2") (pinfunction "VDD_2") (pintype "bidirectional"))
      (node (ref "GL23") (pin "2") (pinfunction "VDD_2") (pintype "bidirectional"))
      (node (ref "GL24") (pin "2") (pinfunction "VDD_2") (pintype "bidirectional"))
      (node (ref "GL25") (pin "2") (pinfunction "VDD_2") (pintype "bidirectional"))
      (node (ref "GL26") (pin "2") (pinfunction "VDD_2") (pintype "bidirectional"))
      (node (ref "GL27") (pin "2") (pinfunction "VDD_2") (pintype "bidirectional"))
      (node (ref "GL28") (pin "2") (pinfunction "VDD_2") (pintype "bidirectional"))
      (node (ref "GL29") (pin "2") (pinfunction "VDD_2") (pintype "bidirectional"))
      (node (ref "GL3") (pin "2") (pinfunction "VDD_2") (pintype "bidirectional"))
      (node (ref "GL30") (pin "2") (pinfunction "VDD_2") (pintype "bidirectional"))
      (node (ref "GL4") (pin "2") (pinfunction "VDD_2") (pintype "bidirectional"))
      (node (ref "GL5") (pin "2") (pinfunction "VDD_2") (pintype "bidirectional"))
      (node (ref "GL6") (pin "2") (pinfunction "VDD_2") (pintype "bidirectional"))
      (node (ref "GL7") (pin "2") (pinfunction "VDD_2") (pintype "bidirectional"))
      (node (ref "GL8") (pin "2") (pinfunction "VDD_2") (pintype "bidirectional"))
      (node (ref "GL9") (pin "2") (pinfunction "VDD_2") (pintype "bidirectional"))
      (node (ref "IC1") (pin "14") (pinfunction "VCCB_14") (pintype "bidirectional"))
      (node (ref "IC1") (pin "8") (pinfunction "OE_8") (pintype "bidirectional"))
      (node (ref "IC2") (pin "14") (pinfunction "VCCB_14") (pintype "bidirectional"))
      (node (ref "IC2") (pin "8") (pinfunction "OE_8") (pintype "bidirectional"))
      (node (ref "OL1") (pin "2") (pinfunction "VDD_2") (pintype "bidirectional"))
      (node (ref "OL10") (pin "2") (pinfunction "VDD_2") (pintype "bidirectional"))
      (node (ref "OL11") (pin "2") (pinfunction "VDD_2") (pintype "bidirectional"))
      (node (ref "OL12") (pin "2") (pinfunction "VDD_2") (pintype "bidirectional"))
      (node (ref "OL13") (pin "2") (pinfunction "VDD_2") (pintype "bidirectional"))
      (node (ref "OL14") (pin "2") (pinfunction "VDD_2") (pintype "bidirectional"))
      (node (ref "OL15") (pin "2") (pinfunction "VDD_2") (pintype "bidirectional"))
      (node (ref "OL16") (pin "2") (pinfunction "VDD_2") (pintype "bidirectional"))
      (node (ref "OL17") (pin "2") (pinfunction "VDD_2") (pintype "bidirectional"))
      (node (ref "OL2") (pin "2") (pinfunction "VDD_2") (pintype "bidirectional"))
      (node (ref "OL3") (pin "2") (pinfunction "VDD_2") (pintype "bidirectional"))
      (node (ref "OL4") (pin "2") (pinfunction "VDD_2") (pintype "bidirectional"))
      (node (ref "OL5") (pin "2") (pinfunction "VDD_2") (pintype "bidirectional"))
      (node (ref "OL6") (pin "2") (pinfunction "VDD_2") (pintype "bidirectional"))
      (node (ref "OL7") (pin "2") (pinfunction "VDD_2") (pintype "bidirectional"))
      (node (ref "OL8") (pin "2") (pinfunction "VDD_2") (pintype "bidirectional"))
      (node (ref "OL9") (pin "2") (pinfunction "VDD_2") (pintype "bidirectional"))
      (node (ref "RL1") (pin "2") (pinfunction "VDD_2") (pintype "bidirectional"))
      (node (ref "RL10") (pin "2") (pinfunction "VDD_2") (pintype "bidirectional"))
      (node (ref "RL11") (pin "2") (pinfunction "VDD_2") (pintype "bidirectional"))
      (node (ref "RL12") (pin "2") (pinfunction "VDD_2") (pintype "bidirectional"))
      (node (ref "RL13") (pin "2") (pinfunction "VDD_2") (pintype "bidirectional"))
      (node (ref "RL14") (pin "2") (pinfunction "VDD_2") (pintype "bidirectional"))
      (node (ref "RL15") (pin "2") (pinfunction "VDD_2") (pintype "bidirectional"))
      (node (ref "RL16") (pin "2") (pinfunction "VDD_2") (pintype "bidirectional"))
      (node (ref "RL17") (pin "2") (pinfunction "VDD_2") (pintype "bidirectional"))
      (node (ref "RL18") (pin "2") (pinfunction "VDD_2") (pintype "bidirectional"))
      (node (ref "RL19") (pin "2") (pinfunction "VDD_2") (pintype "bidirectional"))
      (node (ref "RL2") (pin "2") (pinfunction "VDD_2") (pintype "bidirectional"))
      (node (ref "RL20") (pin "2") (pinfunction "VDD_2") (pintype "bidirectional"))
      (node (ref "RL21") (pin "2") (pinfunction "VDD_2") (pintype "bidirectional"))
      (node (ref "RL22") (pin "2") (pinfunction "VDD_2") (pintype "bidirectional"))
      (node (ref "RL23") (pin "2") (pinfunction "VDD_2") (pintype "bidirectional"))
      (node (ref "RL24") (pin "2") (pinfunction "VDD_2") (pintype "bidirectional"))
      (node (ref "RL25") (pin "2") (pinfunction "VDD_2") (pintype "bidirectional"))
      (node (ref "RL26") (pin "2") (pinfunction "VDD_2") (pintype "bidirectional"))
      (node (ref "RL27") (pin "2") (pinfunction "VDD_2") (pintype "bidirectional"))
      (node (ref "RL3") (pin "2") (pinfunction "VDD_2") (pintype "bidirectional"))
      (node (ref "RL4") (pin "2") (pinfunction "VDD_2") (pintype "bidirectional"))
      (node (ref "RL5") (pin "2") (pinfunction "VDD_2") (pintype "bidirectional"))
      (node (ref "RL6") (pin "2") (pinfunction "VDD_2") (pintype "bidirectional"))
      (node (ref "RL7") (pin "2") (pinfunction "VDD_2") (pintype "bidirectional"))
      (node (ref "RL8") (pin "2") (pinfunction "VDD_2") (pintype "bidirectional"))
      (node (ref "RL9") (pin "2") (pinfunction "VDD_2") (pintype "bidirectional"))
      (node (ref "VOLTAGE_REG") (pin "1") (pinfunction "I_1") (pintype "bidirectional"))
      (node (ref "VOLTAGE_REG") (pin "2") (pinfunction "EN_2") (pintype "bidirectional"))
      (node (ref "YL1") (pin "2") (pinfunction "VDD_2") (pintype "bidirectional"))
      (node (ref "YL10") (pin "2") (pinfunction "VDD_2") (pintype "bidirectional"))
      (node (ref "YL11") (pin "2") (pinfunction "VDD_2") (pintype "bidirectional"))
      (node (ref "YL12") (pin "2") (pinfunction "VDD_2") (pintype "bidirectional"))
      (node (ref "YL13") (pin "2") (pinfunction "VDD_2") (pintype "bidirectional"))
      (node (ref "YL14") (pin "2") (pinfunction "VDD_2") (pintype "bidirectional"))
      (node (ref "YL15") (pin "2") (pinfunction "VDD_2") (pintype "bidirectional"))
      (node (ref "YL16") (pin "2") (pinfunction "VDD_2") (pintype "bidirectional"))
      (node (ref "YL17") (pin "2") (pinfunction "VDD_2") (pintype "bidirectional"))
      (node (ref "YL2") (pin "2") (pinfunction "VDD_2") (pintype "bidirectional"))
      (node (ref "YL3") (pin "2") (pinfunction "VDD_2") (pintype "bidirectional"))
      (node (ref "YL4") (pin "2") (pinfunction "VDD_2") (pintype "bidirectional"))
      (node (ref "YL5") (pin "2") (pinfunction "VDD_2") (pintype "bidirectional"))
      (node (ref "YL6") (pin "2") (pinfunction "VDD_2") (pintype "bidirectional"))
      (node (ref "YL7") (pin "2") (pinfunction "VDD_2") (pintype "bidirectional"))
      (node (ref "YL8") (pin "2") (pinfunction "VDD_2") (pintype "bidirectional"))
      (node (ref "YL9") (pin "2") (pinfunction "VDD_2") (pintype "bidirectional"))
    )
    (net (code "3") (name "BLUE_LINE") (class "Default")
      (node (ref "IC1") (pin "13") (pinfunction "B1Y_13") (pintype "bidirectional"))
      (node (ref "R1") (pin "1") (pinfunction "1_1") (pintype "passive"))
    )
    (net (code "4") (name "EXT_5V") (class "Default")
      (node (ref "U1") (pin "19") (pinfunction "EXT_5V_19") (pintype "power_in"))
    )
    (net (code "5") (name "GND") (class "Default")
      (node (ref "BARREL_JACK1") (pin "RING") (pinfunction "RING_RING") (pintype "bidirectional"))
      (node (ref "BARREL_JACK1") (pin "RING_SW") (pinfunction "RING_SW_RING_SW") (pintype "bidirectional"))
      (node (ref "BL1") (pin "4") (pinfunction "GND_4") (pintype "bidirectional"))
      (node (ref "BL10") (pin "4") (pinfunction "GND_4") (pintype "bidirectional"))
      (node (ref "BL11") (pin "4") (pinfunction "GND_4") (pintype "bidirectional"))
      (node (ref "BL12") (pin "4") (pinfunction "GND_4") (pintype "bidirectional"))
      (node (ref "BL13") (pin "4") (pinfunction "GND_4") (pintype "bidirectional"))
      (node (ref "BL14") (pin "4") (pinfunction "GND_4") (pintype "bidirectional"))
      (node (ref "BL15") (pin "4") (pinfunction "GND_4") (pintype "bidirectional"))
      (node (ref "BL16") (pin "4") (pinfunction "GND_4") (pintype "bidirectional"))
      (node (ref "BL17") (pin "4") (pinfunction "GND_4") (pintype "bidirectional"))
      (node (ref "BL18") (pin "4") (pinfunction "GND_4") (pintype "bidirectional"))
      (node (ref "BL19") (pin "4") (pinfunction "GND_4") (pintype "bidirectional"))
      (node (ref "BL2") (pin "4") (pinfunction "GND_4") (pintype "bidirectional"))
      (node (ref "BL20") (pin "4") (pinfunction "GND_4") (pintype "bidirectional"))
      (node (ref "BL21") (pin "4") (pinfunction "GND_4") (pintype "bidirectional"))
      (node (ref "BL22") (pin "4") (pinfunction "GND_4") (pintype "bidirectional"))
      (node (ref "BL23") (pin "4") (pinfunction "GND_4") (pintype "bidirectional"))
      (node (ref "BL24") (pin "4") (pinfunction "GND_4") (pintype "bidirectional"))
      (node (ref "BL25") (pin "4") (pinfunction "GND_4") (pintype "bidirectional"))
      (node (ref "BL26") (pin "4") (pinfunction "GND_4") (pintype "bidirectional"))
      (node (ref "BL27") (pin "4") (pinfunction "GND_4") (pintype "bidirectional"))
      (node (ref "BL28") (pin "4") (pinfunction "GND_4") (pintype "bidirectional"))
      (node (ref "BL29") (pin "4") (pinfunction "GND_4") (pintype "bidirectional"))
      (node (ref "BL3") (pin "4") (pinfunction "GND_4") (pintype "bidirectional"))
      (node (ref "BL30") (pin "4") (pinfunction "GND_4") (pintype "bidirectional"))
      (node (ref "BL31") (pin "4") (pinfunction "GND_4") (pintype "bidirectional"))
      (node (ref "BL32") (pin "4") (pinfunction "GND_4") (pintype "bidirectional"))
      (node (ref "BL33") (pin "4") (pinfunction "GND_4") (pintype "bidirectional"))
      (node (ref "BL34") (pin "4") (pinfunction "GND_4") (pintype "bidirectional"))
      (node (ref "BL35") (pin "4") (pinfunction "GND_4") (pintype "bidirectional"))
      (node (ref "BL36") (pin "4") (pinfunction "GND_4") (pintype "bidirectional"))
      (node (ref "BL37") (pin "4") (pinfunction "GND_4") (pintype "bidirectional"))
      (node (ref "BL38") (pin "4") (pinfunction "GND_4") (pintype "bidirectional"))
      (node (ref "BL39") (pin "4") (pinfunction "GND_4") (pintype "bidirectional"))
      (node (ref "BL4") (pin "4") (pinfunction "GND_4") (pintype "bidirectional"))
      (node (ref "BL40") (pin "4") (pinfunction "GND_4") (pintype "bidirectional"))
      (node (ref "BL41") (pin "4") (pinfunction "GND_4") (pintype "bidirectional"))
      (node (ref "BL42") (pin "4") (pinfunction "GND_4") (pintype "bidirectional"))
      (node (ref "BL43") (pin "4") (pinfunction "GND_4") (pintype "bidirectional"))
      (node (ref "BL44") (pin "4") (pinfunction "GND_4") (pintype "bidirectional"))
      (node (ref "BL45") (pin "4") (pinfunction "GND_4") (pintype "bidirectional"))
      (node (ref "BL46") (pin "4") (pinfunction "GND_4") (pintype "bidirectional"))
      (node (ref "BL47") (pin "4") (pinfunction "GND_4") (pintype "bidirectional"))
      (node (ref "BL48") (pin "4") (pinfunction "GND_4") (pintype "bidirectional"))
      (node (ref "BL49") (pin "4") (pinfunction "GND_4") (pintype "bidirectional"))
      (node (ref "BL5") (pin "4") (pinfunction "GND_4") (pintype "bidirectional"))
      (node (ref "BL6") (pin "4") (pinfunction "GND_4") (pintype "bidirectional"))
      (node (ref "BL7") (pin "4") (pinfunction "GND_4") (pintype "bidirectional"))
      (node (ref "BL8") (pin "4") (pinfunction "GND_4") (pintype "bidirectional"))
      (node (ref "BL9") (pin "4") (pinfunction "GND_4") (pintype "bidirectional"))
      (node (ref "C1") (pin "2") (pinfunction "2_2") (pintype "passive"))
      (node (ref "C10") (pin "2") (pinfunction "2_2") (pintype "passive"))
      (node (ref "C11") (pin "2") (pinfunction "2_2") (pintype "passive"))
      (node (ref "C12") (pin "2") (pinfunction "2_2") (pintype "passive"))
      (node (ref "C13") (pin "2") (pinfunction "2_2") (pintype "passive"))
      (node (ref "C14") (pin "2") (pinfunction "2_2") (pintype "passive"))
      (node (ref "C15") (pin "2") (pinfunction "2_2") (pintype "passive"))
      (node (ref "C16") (pin "2") (pinfunction "2_2") (pintype "passive"))
      (node (ref "C17") (pin "2") (pinfunction "2_2") (pintype "passive"))
      (node (ref "C18") (pin "2") (pinfunction "2_2") (pintype "passive"))
      (node (ref "C19") (pin "2") (pinfunction "2_2") (pintype "passive"))
      (node (ref "C2") (pin "2") (pinfunction "2_2") (pintype "passive"))
      (node (ref "C20") (pin "2") (pinfunction "2_2") (pintype "passive"))
      (node (ref "C21") (pin "2") (pinfunction "2_2") (pintype "passive"))
      (node (ref "C22") (pin "2") (pinfunction "2_2") (pintype "passive"))
      (node (ref "C3") (pin "2") (pinfunction "2_2") (pintype "passive"))
      (node (ref "C4") (pin "2") (pinfunction "2_2") (pintype "passive"))
      (node (ref "C5") (pin "2") (pinfunction "2_2") (pintype "passive"))
      (node (ref "C6") (pin "2") (pinfunction "2_2") (pintype "passive"))
      (node (ref "C7") (pin "2") (pinfunction "2_2") (pintype "passive"))
      (node (ref "C8") (pin "2") (pinfunction "2_2") (pintype "passive"))
      (node (ref "C9") (pin "2") (pinfunction "2_2") (pintype "passive"))
      (node (ref "GL1") (pin "4") (pinfunction "GND_4") (pintype "bidirectional"))
      (node (ref "GL10") (pin "4") (pinfunction "GND_4") (pintype "bidirectional"))
      (node (ref "GL11") (pin "4") (pinfunction "GND_4") (pintype "bidirectional"))
      (node (ref "GL12") (pin "4") (pinfunction "GND_4") (pintype "bidirectional"))
      (node (ref "GL13") (pin "4") (pinfunction "GND_4") (pintype "bidirectional"))
      (node (ref "GL14") (pin "4") (pinfunction "GND_4") (pintype "bidirectional"))
      (node (ref "GL15") (pin "4") (pinfunction "GND_4") (pintype "bidirectional"))
      (node (ref "GL16") (pin "4") (pinfunction "GND_4") (pintype "bidirectional"))
      (node (ref "GL17") (pin "4") (pinfunction "GND_4") (pintype "bidirectional"))
      (node (ref "GL18") (pin "4") (pinfunction "GND_4") (pintype "bidirectional"))
      (node (ref "GL19") (pin "4") (pinfunction "GND_4") (pintype "bidirectional"))
      (node (ref "GL2") (pin "4") (pinfunction "GND_4") (pintype "bidirectional"))
      (node (ref "GL20") (pin "4") (pinfunction "GND_4") (pintype "bidirectional"))
      (node (ref "GL21") (pin "4") (pinfunction "GND_4") (pintype "bidirectional"))
      (node (ref "GL22") (pin "4") (pinfunction "GND_4") (pintype "bidirectional"))
      (node (ref "GL23") (pin "4") (pinfunction "GND_4") (pintype "bidirectional"))
      (node (ref "GL24") (pin "4") (pinfunction "GND_4") (pintype "bidirectional"))
      (node (ref "GL25") (pin "4") (pinfunction "GND_4") (pintype "bidirectional"))
      (node (ref "GL26") (pin "4") (pinfunction "GND_4") (pintype "bidirectional"))
      (node (ref "GL27") (pin "4") (pinfunction "GND_4") (pintype "bidirectional"))
      (node (ref "GL28") (pin "4") (pinfunction "GND_4") (pintype "bidirectional"))
      (node (ref "GL29") (pin "4") (pinfunction "GND_4") (pintype "bidirectional"))
      (node (ref "GL3") (pin "4") (pinfunction "GND_4") (pintype "bidirectional"))
      (node (ref "GL30") (pin "4") (pinfunction "GND_4") (pintype "bidirectional"))
      (node (ref "GL4") (pin "4") (pinfunction "GND_4") (pintype "bidirectional"))
      (node (ref "GL5") (pin "4") (pinfunction "GND_4") (pintype "bidirectional"))
      (node (ref "GL6") (pin "4") (pinfunction "GND_4") (pintype "bidirectional"))
      (node (ref "GL7") (pin "4") (pinfunction "GND_4") (pintype "bidirectional"))
      (node (ref "GL8") (pin "4") (pinfunction "GND_4") (pintype "bidirectional"))
      (node (ref "GL9") (pin "4") (pinfunction "GND_4") (pintype "bidirectional"))
      (node (ref "IC1") (pin "7") (pinfunction "GND_7") (pintype "bidirectional"))
      (node (ref "IC2") (pin "7") (pinfunction "GND_7") (pintype "bidirectional"))
      (node (ref "OL1") (pin "4") (pinfunction "GND_4") (pintype "bidirectional"))
      (node (ref "OL10") (pin "4") (pinfunction "GND_4") (pintype "bidirectional"))
      (node (ref "OL11") (pin "4") (pinfunction "GND_4") (pintype "bidirectional"))
      (node (ref "OL12") (pin "4") (pinfunction "GND_4") (pintype "bidirectional"))
      (node (ref "OL13") (pin "4") (pinfunction "GND_4") (pintype "bidirectional"))
      (node (ref "OL14") (pin "4") (pinfunction "GND_4") (pintype "bidirectional"))
      (node (ref "OL15") (pin "4") (pinfunction "GND_4") (pintype "bidirectional"))
      (node (ref "OL16") (pin "4") (pinfunction "GND_4") (pintype "bidirectional"))
      (node (ref "OL17") (pin "4") (pinfunction "GND_4") (pintype "bidirectional"))
      (node (ref "OL2") (pin "4") (pinfunction "GND_4") (pintype "bidirectional"))
      (node (ref "OL3") (pin "4") (pinfunction "GND_4") (pintype "bidirectional"))
      (node (ref "OL4") (pin "4") (pinfunction "GND_4") (pintype "bidirectional"))
      (node (ref "OL5") (pin "4") (pinfunction "GND_4") (pintype "bidirectional"))
      (node (ref "OL6") (pin "4") (pinfunction "GND_4") (pintype "bidirectional"))
      (node (ref "OL7") (pin "4") (pinfunction "GND_4") (pintype "bidirectional"))
      (node (ref "OL8") (pin "4") (pinfunction "GND_4") (pintype "bidirectional"))
      (node (ref "OL9") (pin "4") (pinfunction "GND_4") (pintype "bidirectional"))
      (node (ref "RL1") (pin "4") (pinfunction "GND_4") (pintype "bidirectional"))
      (node (ref "RL10") (pin "4") (pinfunction "GND_4") (pintype "bidirectional"))
      (node (ref "RL11") (pin "4") (pinfunction "GND_4") (pintype "bidirectional"))
      (node (ref "RL12") (pin "4") (pinfunction "GND_4") (pintype "bidirectional"))
      (node (ref "RL13") (pin "4") (pinfunction "GND_4") (pintype "bidirectional"))
      (node (ref "RL14") (pin "4") (pinfunction "GND_4") (pintype "bidirectional"))
      (node (ref "RL15") (pin "4") (pinfunction "GND_4") (pintype "bidirectional"))
      (node (ref "RL16") (pin "4") (pinfunction "GND_4") (pintype "bidirectional"))
      (node (ref "RL17") (pin "4") (pinfunction "GND_4") (pintype "bidirectional"))
      (node (ref "RL18") (pin "4") (pinfunction "GND_4") (pintype "bidirectional"))
      (node (ref "RL19") (pin "4") (pinfunction "GND_4") (pintype "bidirectional"))
      (node (ref "RL2") (pin "4") (pinfunction "GND_4") (pintype "bidirectional"))
      (node (ref "RL20") (pin "4") (pinfunction "GND_4") (pintype "bidirectional"))
      (node (ref "RL21") (pin "4") (pinfunction "GND_4") (pintype "bidirectional"))
      (node (ref "RL22") (pin "4") (pinfunction "GND_4") (pintype "bidirectional"))
      (node (ref "RL23") (pin "4") (pinfunction "GND_4") (pintype "bidirectional"))
      (node (ref "RL24") (pin "4") (pinfunction "GND_4") (pintype "bidirectional"))
      (node (ref "RL25") (pin "4") (pinfunction "GND_4") (pintype "bidirectional"))
      (node (ref "RL26") (pin "4") (pinfunction "GND_4") (pintype "bidirectional"))
      (node (ref "RL27") (pin "4") (pinfunction "GND_4") (pintype "bidirectional"))
      (node (ref "RL3") (pin "4") (pinfunction "GND_4") (pintype "bidirectional"))
      (node (ref "RL4") (pin "4") (pinfunction "GND_4") (pintype "bidirectional"))
      (node (ref "RL5") (pin "4") (pinfunction "GND_4") (pintype "bidirectional"))
      (node (ref "RL6") (pin "4") (pinfunction "GND_4") (pintype "bidirectional"))
      (node (ref "RL7") (pin "4") (pinfunction "GND_4") (pintype "bidirectional"))
      (node (ref "RL8") (pin "4") (pinfunction "GND_4") (pintype "bidirectional"))
      (node (ref "RL9") (pin "4") (pinfunction "GND_4") (pintype "bidirectional"))
      (node (ref "U1") (pin "14") (pinfunction "GND1_14") (pintype "power_in"))
      (node (ref "U1") (pin "20") (pinfunction "GND3_20") (pintype "power_in"))
      (node (ref "U1") (pin "26") (pinfunction "GND2_26") (pintype "power_in"))
      (node (ref "VOLTAGE_REG") (pin "3") (pinfunction "GND_3") (pintype "bidirectional"))
      (node (ref "VOLTAGE_REG") (pin "6") (pinfunction "TAB_6") (pintype "bidirectional"))
      (node (ref "YL1") (pin "4") (pinfunction "GND_4") (pintype "bidirectional"))
      (node (ref "YL10") (pin "4") (pinfunction "GND_4") (pintype "bidirectional"))
      (node (ref "YL11") (pin "4") (pinfunction "GND_4") (pintype "bidirectional"))
      (node (ref "YL12") (pin "4") (pinfunction "GND_4") (pintype "bidirectional"))
      (node (ref "YL13") (pin "4") (pinfunction "GND_4") (pintype "bidirectional"))
      (node (ref "YL14") (pin "4") (pinfunction "GND_4") (pintype "bidirectional"))
      (node (ref "YL15") (pin "4") (pinfunction "GND_4") (pintype "bidirectional"))
      (node (ref "YL16") (pin "4") (pinfunction "GND_4") (pintype "bidirectional"))
      (node (ref "YL17") (pin "4") (pinfunction "GND_4") (pintype "bidirectional"))
      (node (ref "YL2") (pin "4") (pinfunction "GND_4") (pintype "bidirectional"))
      (node (ref "YL3") (pin "4") (pinfunction "GND_4") (pintype "bidirectional"))
      (node (ref "YL4") (pin "4") (pinfunction "GND_4") (pintype "bidirectional"))
      (node (ref "YL5") (pin "4") (pinfunction "GND_4") (pintype "bidirectional"))
      (node (ref "YL6") (pin "4") (pinfunction "GND_4") (pintype "bidirectional"))
      (node (ref "YL7") (pin "4") (pinfunction "GND_4") (pintype "bidirectional"))
      (node (ref "YL8") (pin "4") (pinfunction "GND_4") (pintype "bidirectional"))
      (node (ref "YL9") (pin "4") (pinfunction "GND_4") (pintype "bidirectional"))
    )
    (net (code "6") (name "GREEN_LINE") (class "Default")
      (node (ref "IC2") (pin "12") (pinfunction "B2Y_12") (pintype "bidirectional"))
      (node (ref "R4") (pin "1") (pinfunction "1_1") (pintype "passive"))
    )
    (net (code "7") (name "Net-(BL1-DIN)") (class "Default")
      (node (ref "BL1") (pin "1") (pinfunction "DIN_1") (pintype "bidirectional"))
      (node (ref "R1") (pin "2") (pinfunction "2_2") (pintype "passive"))
    )
    (net (code "8") (name "Net-(BL1-DOUT)") (class "Default")
      (node (ref "BL1") (pin "3") (pinfunction "DOUT_3") (pintype "bidirectional"))
      (node (ref "BL2") (pin "1") (pinfunction "DIN_1") (pintype "bidirectional"))
    )
    (net (code "9") (name "Net-(BL2-DOUT)") (class "Default")
      (node (ref "BL2") (pin "3") (pinfunction "DOUT_3") (pintype "bidirectional"))
      (node (ref "BL3") (pin "1") (pinfunction "DIN_1") (pintype "bidirectional"))
    )
    (net (code "10") (name "Net-(BL3-DOUT)") (class "Default")
      (node (ref "BL3") (pin "3") (pinfunction "DOUT_3") (pintype "bidirectional"))
      (node (ref "BL4") (pin "1") (pinfunction "DIN_1") (pintype "bidirectional"))
    )
    (net (code "11") (name "Net-(BL4-DOUT)") (class "Default")
      (node (ref "BL4") (pin "3") (pinfunction "DOUT_3") (pintype "bidirectional"))
      (node (ref "BL5") (pin "1") (pinfunction "DIN_1") (pintype "bidirectional"))
    )
    (net (code "12") (name "Net-(BL5-DOUT)") (class "Default")
      (node (ref "BL5") (pin "3") (pinfunction "DOUT_3") (pintype "bidirectional"))
      (node (ref "BL6") (pin "1") (pinfunction "DIN_1") (pintype "bidirectional"))
    )
    (net (code "13") (name "Net-(BL6-DOUT)") (class "Default")
      (node (ref "BL6") (pin "3") (pinfunction "DOUT_3") (pintype "bidirectional"))
      (node (ref "BL7") (pin "1") (pinfunction "DIN_1") (pintype "bidirectional"))
    )
    (net (code "14") (name "Net-(BL7-DOUT)") (class "Default")
      (node (ref "BL7") (pin "3") (pinfunction "DOUT_3") (pintype "bidirectional"))
      (node (ref "BL8") (pin "1") (pinfunction "DIN_1") (pintype "bidirectional"))
    )
    (net (code "15") (name "Net-(BL8-DOUT)") (class "Default")
      (node (ref "BL8") (pin "3") (pinfunction "DOUT_3") (pintype "bidirectional"))
      (node (ref "BL9") (pin "1") (pinfunction "DIN_1") (pintype "bidirectional"))
    )
    (net (code "16") (name "Net-(BL10-DIN)") (class "Default")
      (node (ref "BL10") (pin "1") (pinfunction "DIN_1") (pintype "bidirectional"))
      (node (ref "BL9") (pin "3") (pinfunction "DOUT_3") (pintype "bidirectional"))
    )
    (net (code "17") (name "Net-(BL10-DOUT)") (class "Default")
      (node (ref "BL10") (pin "3") (pinfunction "DOUT_3") (pintype "bidirectional"))
      (node (ref "BL11") (pin "1") (pinfunction "DIN_1") (pintype "bidirectional"))
    )
    (net (code "18") (name "Net-(BL11-DOUT)") (class "Default")
      (node (ref "BL11") (pin "3") (pinfunction "DOUT_3") (pintype "bidirectional"))
      (node (ref "BL12") (pin "1") (pinfunction "DIN_1") (pintype "bidirectional"))
    )
    (net (code "19") (name "Net-(BL12-DOUT)") (class "Default")
      (node (ref "BL12") (pin "3") (pinfunction "DOUT_3") (pintype "bidirectional"))
      (node (ref "BL13") (pin "1") (pinfunction "DIN_1") (pintype "bidirectional"))
    )
    (net (code "20") (name "Net-(BL13-DOUT)") (class "Default")
      (node (ref "BL13") (pin "3") (pinfunction "DOUT_3") (pintype "bidirectional"))
      (node (ref "BL14") (pin "1") (pinfunction "DIN_1") (pintype "bidirectional"))
    )
    (net (code "21") (name "Net-(BL14-DOUT)") (class "Default")
      (node (ref "BL14") (pin "3") (pinfunction "DOUT_3") (pintype "bidirectional"))
      (node (ref "BL15") (pin "1") (pinfunction "DIN_1") (pintype "bidirectional"))
    )
    (net (code "22") (name "Net-(BL15-DOUT)") (class "Default")
      (node (ref "BL15") (pin "3") (pinfunction "DOUT_3") (pintype "bidirectional"))
      (node (ref "BL16") (pin "1") (pinfunction "DIN_1") (pintype "bidirectional"))
    )
    (net (code "23") (name "Net-(BL16-DOUT)") (class "Default")
      (node (ref "BL16") (pin "3") (pinfunction "DOUT_3") (pintype "bidirectional"))
      (node (ref "BL17") (pin "1") (pinfunction "DIN_1") (pintype "bidirectional"))
    )
    (net (code "24") (name "Net-(BL17-DOUT)") (class "Default")
      (node (ref "BL17") (pin "3") (pinfunction "DOUT_3") (pintype "bidirectional"))
      (node (ref "BL18") (pin "1") (pinfunction "DIN_1") (pintype "bidirectional"))
    )
    (net (code "25") (name "Net-(BL18-DOUT)") (class "Default")
      (node (ref "BL18") (pin "3") (pinfunction "DOUT_3") (pintype "bidirectional"))
      (node (ref "BL19") (pin "1") (pinfunction "DIN_1") (pintype "bidirectional"))
    )
    (net (code "26") (name "Net-(BL19-DOUT)") (class "Default")
      (node (ref "BL19") (pin "3") (pinfunction "DOUT_3") (pintype "bidirectional"))
      (node (ref "BL20") (pin "1") (pinfunction "DIN_1") (pintype "bidirectional"))
    )
    (net (code "27") (name "Net-(BL20-DOUT)") (class "Default")
      (node (ref "BL20") (pin "3") (pinfunction "DOUT_3") (pintype "bidirectional"))
      (node (ref "BL21") (pin "1") (pinfunction "DIN_1") (pintype "bidirectional"))
    )
    (net (code "28") (name "Net-(BL21-DOUT)") (class "Default")
      (node (ref "BL21") (pin "3") (pinfunction "DOUT_3") (pintype "bidirectional"))
      (node (ref "BL22") (pin "1") (pinfunction "DIN_1") (pintype "bidirectional"))
    )
    (net (code "29") (name "Net-(BL22-DOUT)") (class "Default")
      (node (ref "BL22") (pin "3") (pinfunction "DOUT_3") (pintype "bidirectional"))
      (node (ref "BL23") (pin "1") (pinfunction "DIN_1") (pintype "bidirectional"))
    )
    (net (code "30") (name "Net-(BL23-DOUT)") (class "Default")
      (node (ref "BL23") (pin "3") (pinfunction "DOUT_3") (pintype "bidirectional"))
      (node (ref "BL24") (pin "1") (pinfunction "DIN_1") (pintype "bidirectional"))
    )
    (net (code "31") (name "Net-(BL24-DOUT)") (class "Default")
      (node (ref "BL24") (pin "3") (pinfunction "DOUT_3") (pintype "bidirectional"))
      (node (ref "BL25") (pin "1") (pinfunction "DIN_1") (pintype "bidirectional"))
    )
    (net (code "32") (name "Net-(BL25-DOUT)") (class "Default")
      (node (ref "BL25") (pin "3") (pinfunction "DOUT_3") (pintype "bidirectional"))
      (node (ref "BL26") (pin "1") (pinfunction "DIN_1") (pintype "bidirectional"))
    )
    (net (code "33") (name "Net-(BL26-DOUT)") (class "Default")
      (node (ref "BL26") (pin "3") (pinfunction "DOUT_3") (pintype "bidirectional"))
      (node (ref "BL27") (pin "1") (pinfunction "DIN_1") (pintype "bidirectional"))
    )
    (net (code "34") (name "Net-(BL27-DOUT)") (class "Default")
      (node (ref "BL27") (pin "3") (pinfunction "DOUT_3") (pintype "bidirectional"))
      (node (ref "BL28") (pin "1") (pinfunction "DIN_1") (pintype "bidirectional"))
    )
    (net (code "35") (name "Net-(BL28-DOUT)") (class "Default")
      (node (ref "BL28") (pin "3") (pinfunction "DOUT_3") (pintype "bidirectional"))
      (node (ref "BL29") (pin "1") (pinfunction "DIN_1") (pintype "bidirectional"))
    )
    (net (code "36") (name "Net-(BL29-DOUT)") (class "Default")
      (node (ref "BL29") (pin "3") (pinfunction "DOUT_3") (pintype "bidirectional"))
      (node (ref "BL30") (pin "1") (pinfunction "DIN_1") (pintype "bidirectional"))
    )
    (net (code "37") (name "Net-(BL30-DOUT)") (class "Default")
      (node (ref "BL30") (pin "3") (pinfunction "DOUT_3") (pintype "bidirectional"))
      (node (ref "BL31") (pin "1") (pinfunction "DIN_1") (pintype "bidirectional"))
    )
    (net (code "38") (name "Net-(BL31-DOUT)") (class "Default")
      (node (ref "BL31") (pin "3") (pinfunction "DOUT_3") (pintype "bidirectional"))
      (node (ref "BL32") (pin "1") (pinfunction "DIN_1") (pintype "bidirectional"))
    )
    (net (code "39") (name "Net-(BL32-DOUT)") (class "Default")
      (node (ref "BL32") (pin "3") (pinfunction "DOUT_3") (pintype "bidirectional"))
      (node (ref "BL33") (pin "1") (pinfunction "DIN_1") (pintype "bidirectional"))
    )
    (net (code "40") (name "Net-(BL33-DOUT)") (class "Default")
      (node (ref "BL33") (pin "3") (pinfunction "DOUT_3") (pintype "bidirectional"))
      (node (ref "BL34") (pin "1") (pinfunction "DIN_1") (pintype "bidirectional"))
    )
    (net (code "41") (name "Net-(BL34-DOUT)") (class "Default")
      (node (ref "BL34") (pin "3") (pinfunction "DOUT_3") (pintype "bidirectional"))
      (node (ref "BL35") (pin "1") (pinfunction "DIN_1") (pintype "bidirectional"))
    )
    (net (code "42") (name "Net-(BL35-DOUT)") (class "Default")
      (node (ref "BL35") (pin "3") (pinfunction "DOUT_3") (pintype "bidirectional"))
      (node (ref "BL36") (pin "1") (pinfunction "DIN_1") (pintype "bidirectional"))
    )
    (net (code "43") (name "Net-(BL36-DOUT)") (class "Default")
      (node (ref "BL36") (pin "3") (pinfunction "DOUT_3") (pintype "bidirectional"))
      (node (ref "BL37") (pin "1") (pinfunction "DIN_1") (pintype "bidirectional"))
    )
    (net (code "44") (name "Net-(BL37-DOUT)") (class "Default")
      (node (ref "BL37") (pin "3") (pinfunction "DOUT_3") (pintype "bidirectional"))
      (node (ref "BL38") (pin "1") (pinfunction "DIN_1") (pintype "bidirectional"))
    )
    (net (code "45") (name "Net-(BL38-DOUT)") (class "Default")
      (node (ref "BL38") (pin "3") (pinfunction "DOUT_3") (pintype "bidirectional"))
      (node (ref "BL39") (pin "1") (pinfunction "DIN_1") (pintype "bidirectional"))
    )
    (net (code "46") (name "Net-(BL39-DOUT)") (class "Default")
      (node (ref "BL39") (pin "3") (pinfunction "DOUT_3") (pintype "bidirectional"))
      (node (ref "BL40") (pin "1") (pinfunction "DIN_1") (pintype "bidirectional"))
    )
    (net (code "47") (name "Net-(BL40-DOUT)") (class "Default")
      (node (ref "BL40") (pin "3") (pinfunction "DOUT_3") (pintype "bidirectional"))
      (node (ref "BL41") (pin "1") (pinfunction "DIN_1") (pintype "bidirectional"))
    )
    (net (code "48") (name "Net-(BL41-DOUT)") (class "Default")
      (node (ref "BL41") (pin "3") (pinfunction "DOUT_3") (pintype "bidirectional"))
      (node (ref "BL42") (pin "1") (pinfunction "DIN_1") (pintype "bidirectional"))
    )
    (net (code "49") (name "Net-(BL42-DOUT)") (class "Default")
      (node (ref "BL42") (pin "3") (pinfunction "DOUT_3") (pintype "bidirectional"))
      (node (ref "BL43") (pin "1") (pinfunction "DIN_1") (pintype "bidirectional"))
    )
    (net (code "50") (name "Net-(BL43-DOUT)") (class "Default")
      (node (ref "BL43") (pin "3") (pinfunction "DOUT_3") (pintype "bidirectional"))
      (node (ref "BL44") (pin "1") (pinfunction "DIN_1") (pintype "bidirectional"))
    )
    (net (code "51") (name "Net-(BL44-DOUT)") (class "Default")
      (node (ref "BL44") (pin "3") (pinfunction "DOUT_3") (pintype "bidirectional"))
      (node (ref "BL45") (pin "1") (pinfunction "DIN_1") (pintype "bidirectional"))
    )
    (net (code "52") (name "Net-(BL45-DOUT)") (class "Default")
      (node (ref "BL45") (pin "3") (pinfunction "DOUT_3") (pintype "bidirectional"))
      (node (ref "BL46") (pin "1") (pinfunction "DIN_1") (pintype "bidirectional"))
    )
    (net (code "53") (name "Net-(BL46-DOUT)") (class "Default")
      (node (ref "BL46") (pin "3") (pinfunction "DOUT_3") (pintype "bidirectional"))
      (node (ref "BL47") (pin "1") (pinfunction "DIN_1") (pintype "bidirectional"))
    )
    (net (code "54") (name "Net-(BL47-DOUT)") (class "Default")
      (node (ref "BL47") (pin "3") (pinfunction "DOUT_3") (pintype "bidirectional"))
      (node (ref "BL48") (pin "1") (pinfunction "DIN_1") (pintype "bidirectional"))
    )
    (net (code "55") (name "Net-(BL48-DOUT)") (class "Default")
      (node (ref "BL48") (pin "3") (pinfunction "DOUT_3") (pintype "bidirectional"))
      (node (ref "BL49") (pin "1") (pinfunction "DIN_1") (pintype "bidirectional"))
    )
    (net (code "56") (name "Net-(GL1-DIN)") (class "Default")
      (node (ref "GL1") (pin "1") (pinfunction "DIN_1") (pintype "bidirectional"))
      (node (ref "R4") (pin "2") (pinfunction "2_2") (pintype "passive"))
    )
    (net (code "57") (name "Net-(GL1-DOUT)") (class "Default")
      (node (ref "GL1") (pin "3") (pinfunction "DOUT_3") (pintype "bidirectional"))
      (node (ref "GL2") (pin "1") (pinfunction "DIN_1") (pintype "bidirectional"))
    )
    (net (code "58") (name "Net-(GL2-DOUT)") (class "Default")
      (node (ref "GL2") (pin "3") (pinfunction "DOUT_3") (pintype "bidirectional"))
      (node (ref "GL3") (pin "1") (pinfunction "DIN_1") (pintype "bidirectional"))
    )
    (net (code "59") (name "Net-(GL3-DOUT)") (class "Default")
      (node (ref "GL3") (pin "3") (pinfunction "DOUT_3") (pintype "bidirectional"))
      (node (ref "GL4") (pin "1") (pinfunction "DIN_1") (pintype "bidirectional"))
    )
    (net (code "60") (name "Net-(GL4-DOUT)") (class "Default")
      (node (ref "GL4") (pin "3") (pinfunction "DOUT_3") (pintype "bidirectional"))
      (node (ref "GL5") (pin "1") (pinfunction "DIN_1") (pintype "bidirectional"))
    )
    (net (code "61") (name "Net-(GL5-DOUT)") (class "Default")
      (node (ref "GL5") (pin "3") (pinfunction "DOUT_3") (pintype "bidirectional"))
      (node (ref "GL6") (pin "1") (pinfunction "DIN_1") (pintype "bidirectional"))
    )
    (net (code "62") (name "Net-(GL6-DOUT)") (class "Default")
      (node (ref "GL6") (pin "3") (pinfunction "DOUT_3") (pintype "bidirectional"))
      (node (ref "GL7") (pin "1") (pinfunction "DIN_1") (pintype "bidirectional"))
    )
    (net (code "63") (name "Net-(GL7-DOUT)") (class "Default")
      (node (ref "GL7") (pin "3") (pinfunction "DOUT_3") (pintype "bidirectional"))
      (node (ref "GL8") (pin "1") (pinfunction "DIN_1") (pintype "bidirectional"))
    )
    (net (code "64") (name "Net-(GL8-DOUT)") (class "Default")
      (node (ref "GL8") (pin "3") (pinfunction "DOUT_3") (pintype "bidirectional"))
      (node (ref "GL9") (pin "1") (pinfunction "DIN_1") (pintype "bidirectional"))
    )
    (net (code "65") (name "Net-(GL10-DIN)") (class "Default")
      (node (ref "GL10") (pin "1") (pinfunction "DIN_1") (pintype "bidirectional"))
      (node (ref "GL9") (pin "3") (pinfunction "DOUT_3") (pintype "bidirectional"))
    )
    (net (code "66") (name "Net-(GL10-DOUT)") (class "Default")
      (node (ref "GL10") (pin "3") (pinfunction "DOUT_3") (pintype "bidirectional"))
      (node (ref "GL11") (pin "1") (pinfunction "DIN_1") (pintype "bidirectional"))
    )
    (net (code "67") (name "Net-(GL11-DOUT)") (class "Default")
      (node (ref "GL11") (pin "3") (pinfunction "DOUT_3") (pintype "bidirectional"))
      (node (ref "GL12") (pin "1") (pinfunction "DIN_1") (pintype "bidirectional"))
    )
    (net (code "68") (name "Net-(GL12-DOUT)") (class "Default")
      (node (ref "GL12") (pin "3") (pinfunction "DOUT_3") (pintype "bidirectional"))
      (node (ref "GL13") (pin "1") (pinfunction "DIN_1") (pintype "bidirectional"))
    )
    (net (code "69") (name "Net-(GL13-DOUT)") (class "Default")
      (node (ref "GL13") (pin "3") (pinfunction "DOUT_3") (pintype "bidirectional"))
      (node (ref "GL14") (pin "1") (pinfunction "DIN_1") (pintype "bidirectional"))
    )
    (net (code "70") (name "Net-(GL14-DOUT)") (class "Default")
      (node (ref "GL14") (pin "3") (pinfunction "DOUT_3") (pintype "bidirectional"))
      (node (ref "GL15") (pin "1") (pinfunction "DIN_1") (pintype "bidirectional"))
    )
    (net (code "71") (name "Net-(GL15-DOUT)") (class "Default")
      (node (ref "GL15") (pin "3") (pinfunction "DOUT_3") (pintype "bidirectional"))
      (node (ref "GL16") (pin "1") (pinfunction "DIN_1") (pintype "bidirectional"))
    )
    (net (code "72") (name "Net-(GL16-DOUT)") (class "Default")
      (node (ref "GL16") (pin "3") (pinfunction "DOUT_3") (pintype "bidirectional"))
      (node (ref "GL17") (pin "1") (pinfunction "DIN_1") (pintype "bidirectional"))
    )
    (net (code "73") (name "Net-(GL17-DOUT)") (class "Default")
      (node (ref "GL17") (pin "3") (pinfunction "DOUT_3") (pintype "bidirectional"))
      (node (ref "GL18") (pin "1") (pinfunction "DIN_1") (pintype "bidirectional"))
    )
    (net (code "74") (name "Net-(GL18-DOUT)") (class "Default")
      (node (ref "GL18") (pin "3") (pinfunction "DOUT_3") (pintype "bidirectional"))
      (node (ref "GL19") (pin "1") (pinfunction "DIN_1") (pintype "bidirectional"))
    )
    (net (code "75") (name "Net-(GL19-DOUT)") (class "Default")
      (node (ref "GL19") (pin "3") (pinfunction "DOUT_3") (pintype "bidirectional"))
      (node (ref "GL20") (pin "1") (pinfunction "DIN_1") (pintype "bidirectional"))
    )
    (net (code "76") (name "Net-(GL20-DOUT)") (class "Default")
      (node (ref "GL20") (pin "3") (pinfunction "DOUT_3") (pintype "bidirectional"))
      (node (ref "GL21") (pin "1") (pinfunction "DIN_1") (pintype "bidirectional"))
    )
    (net (code "77") (name "Net-(GL21-DOUT)") (class "Default")
      (node (ref "GL21") (pin "3") (pinfunction "DOUT_3") (pintype "bidirectional"))
      (node (ref "GL22") (pin "1") (pinfunction "DIN_1") (pintype "bidirectional"))
    )
    (net (code "78") (name "Net-(GL22-DOUT)") (class "Default")
      (node (ref "GL22") (pin "3") (pinfunction "DOUT_3") (pintype "bidirectional"))
      (node (ref "GL23") (pin "1") (pinfunction "DIN_1") (pintype "bidirectional"))
    )
    (net (code "79") (name "Net-(GL23-DOUT)") (class "Default")
      (node (ref "GL23") (pin "3") (pinfunction "DOUT_3") (pintype "bidirectional"))
      (node (ref "GL24") (pin "1") (pinfunction "DIN_1") (pintype "bidirectional"))
    )
    (net (code "80") (name "Net-(GL24-DOUT)") (class "Default")
      (node (ref "GL24") (pin "3") (pinfunction "DOUT_3") (pintype "bidirectional"))
      (node (ref "GL25") (pin "1") (pinfunction "DIN_1") (pintype "bidirectional"))
    )
    (net (code "81") (name "Net-(GL25-DOUT)") (class "Default")
      (node (ref "GL25") (pin "3") (pinfunction "DOUT_3") (pintype "bidirectional"))
      (node (ref "GL26") (pin "1") (pinfunction "DIN_1") (pintype "bidirectional"))
    )
    (net (code "82") (name "Net-(GL26-DOUT)") (class "Default")
      (node (ref "GL26") (pin "3") (pinfunction "DOUT_3") (pintype "bidirectional"))
      (node (ref "GL27") (pin "1") (pinfunction "DIN_1") (pintype "bidirectional"))
    )
    (net (code "83") (name "Net-(GL27-DOUT)") (class "Default")
      (node (ref "GL27") (pin "3") (pinfunction "DOUT_3") (pintype "bidirectional"))
      (node (ref "GL28") (pin "1") (pinfunction "DIN_1") (pintype "bidirectional"))
    )
    (net (code "84") (name "Net-(GL28-DOUT)") (class "Default")
      (node (ref "GL28") (pin "3") (pinfunction "DOUT_3") (pintype "bidirectional"))
      (node (ref "GL29") (pin "1") (pinfunction "DIN_1") (pintype "bidirectional"))
    )
    (net (code "85") (name "Net-(GL29-DOUT)") (class "Default")
      (node (ref "GL29") (pin "3") (pinfunction "DOUT_3") (pintype "bidirectional"))
      (node (ref "GL30") (pin "1") (pinfunction "DIN_1") (pintype "bidirectional"))
    )
    (net (code "86") (name "Net-(IC1-A1)") (class "Default")
      (node (ref "IC1") (pin "2") (pinfunction "A1_2") (pintype "bidirectional"))
      (node (ref "U1") (pin "13") (pinfunction "IO12_13") (pintype "bidirectional"))
    )
    (net (code "87") (name "Net-(IC1-A2)") (class "Default")
      (node (ref "IC1") (pin "3") (pinfunction "A2_3") (pintype "bidirectional"))
      (node (ref "U1") (pin "12") (pinfunction "IO14_12") (pintype "bidirectional"))
    )
    (net (code "88") (name "Net-(IC1-A3)") (class "Default")
      (node (ref "IC1") (pin "4") (pinfunction "A3_4") (pintype "bidirectional"))
      (node (ref "U1") (pin "11") (pinfunction "IO27_11") (pintype "bidirectional"))
    )
    (net (code "89") (name "Net-(IC2-A1)") (class "Default")
      (node (ref "IC2") (pin "2") (pinfunction "A1_2") (pintype "bidirectional"))
      (node (ref "U1") (pin "7") (pinfunction "IO32_7") (pintype "bidirectional"))
    )
    (net (code "90") (name "Net-(IC2-A2)") (class "Default")
      (node (ref "IC2") (pin "3") (pinfunction "A2_3") (pintype "bidirectional"))
      (node (ref "U1") (pin "10") (pinfunction "IO26_10") (pintype "bidirectional"))
    )
    (net (code "91") (name "Net-(OL1-DIN)") (class "Default")
      (node (ref "OL1") (pin "1") (pinfunction "DIN_1") (pintype "bidirectional"))
      (node (ref "R5") (pin "2") (pinfunction "2_2") (pintype "passive"))
    )
    (net (code "92") (name "Net-(OL1-DOUT)") (class "Default")
      (node (ref "OL1") (pin "3") (pinfunction "DOUT_3") (pintype "bidirectional"))
      (node (ref "OL2") (pin "1") (pinfunction "DIN_1") (pintype "bidirectional"))
    )
    (net (code "93") (name "Net-(OL2-DOUT)") (class "Default")
      (node (ref "OL2") (pin "3") (pinfunction "DOUT_3") (pintype "bidirectional"))
      (node (ref "OL3") (pin "1") (pinfunction "DIN_1") (pintype "bidirectional"))
    )
    (net (code "94") (name "Net-(OL3-DOUT)") (class "Default")
      (node (ref "OL3") (pin "3") (pinfunction "DOUT_3") (pintype "bidirectional"))
      (node (ref "OL4") (pin "1") (pinfunction "DIN_1") (pintype "bidirectional"))
    )
    (net (code "95") (name "Net-(OL4-DOUT)") (class "Default")
      (node (ref "OL4") (pin "3") (pinfunction "DOUT_3") (pintype "bidirectional"))
      (node (ref "OL5") (pin "1") (pinfunction "DIN_1") (pintype "bidirectional"))
    )
    (net (code "96") (name "Net-(OL5-DOUT)") (class "Default")
      (node (ref "OL5") (pin "3") (pinfunction "DOUT_3") (pintype "bidirectional"))
      (node (ref "OL6") (pin "1") (pinfunction "DIN_1") (pintype "bidirectional"))
    )
    (net (code "97") (name "Net-(OL6-DOUT)") (class "Default")
      (node (ref "OL6") (pin "3") (pinfunction "DOUT_3") (pintype "bidirectional"))
      (node (ref "OL7") (pin "1") (pinfunction "DIN_1") (pintype "bidirectional"))
    )
    (net (code "98") (name "Net-(OL7-DOUT)") (class "Default")
      (node (ref "OL7") (pin "3") (pinfunction "DOUT_3") (pintype "bidirectional"))
      (node (ref "OL8") (pin "1") (pinfunction "DIN_1") (pintype "bidirectional"))
    )
    (net (code "99") (name "Net-(OL8-DOUT)") (class "Default")
      (node (ref "OL8") (pin "3") (pinfunction "DOUT_3") (pintype "bidirectional"))
      (node (ref "OL9") (pin "1") (pinfunction "DIN_1") (pintype "bidirectional"))
    )
    (net (code "100") (name "Net-(OL10-DIN)") (class "Default")
      (node (ref "OL10") (pin "1") (pinfunction "DIN_1") (pintype "bidirectional"))
      (node (ref "OL9") (pin "3") (pinfunction "DOUT_3") (pintype "bidirectional"))
    )
    (net (code "101") (name "Net-(OL10-DOUT)") (class "Default")
      (node (ref "OL10") (pin "3") (pinfunction "DOUT_3") (pintype "bidirectional"))
      (node (ref "OL11") (pin "1") (pinfunction "DIN_1") (pintype "bidirectional"))
    )
    (net (code "102") (name "Net-(OL11-DOUT)") (class "Default")
      (node (ref "OL11") (pin "3") (pinfunction "DOUT_3") (pintype "bidirectional"))
      (node (ref "OL12") (pin "1") (pinfunction "DIN_1") (pintype "bidirectional"))
    )
    (net (code "103") (name "Net-(OL12-DOUT)") (class "Default")
      (node (ref "OL12") (pin "3") (pinfunction "DOUT_3") (pintype "bidirectional"))
      (node (ref "OL13") (pin "1") (pinfunction "DIN_1") (pintype "bidirectional"))
    )
    (net (code "104") (name "Net-(OL13-DOUT)") (class "Default")
      (node (ref "OL13") (pin "3") (pinfunction "DOUT_3") (pintype "bidirectional"))
      (node (ref "OL14") (pin "1") (pinfunction "DIN_1") (pintype "bidirectional"))
    )
    (net (code "105") (name "Net-(OL14-DOUT)") (class "Default")
      (node (ref "OL14") (pin "3") (pinfunction "DOUT_3") (pintype "bidirectional"))
      (node (ref "OL15") (pin "1") (pinfunction "DIN_1") (pintype "bidirectional"))
    )
    (net (code "106") (name "Net-(OL15-DOUT)") (class "Default")
      (node (ref "OL15") (pin "3") (pinfunction "DOUT_3") (pintype "bidirectional"))
      (node (ref "OL16") (pin "1") (pinfunction "DIN_1") (pintype "bidirectional"))
    )
    (net (code "107") (name "Net-(OL16-DOUT)") (class "Default")
      (node (ref "OL16") (pin "3") (pinfunction "DOUT_3") (pintype "bidirectional"))
      (node (ref "OL17") (pin "1") (pinfunction "DIN_1") (pintype "bidirectional"))
    )
    (net (code "108") (name "Net-(RL1-DIN)") (class "Default")
      (node (ref "R2") (pin "2") (pinfunction "2_2") (pintype "passive"))
      (node (ref "RL1") (pin "1") (pinfunction "DIN_1") (pintype "bidirectional"))
    )
    (net (code "109") (name "Net-(RL1-DOUT)") (class "Default")
      (node (ref "RL1") (pin "3") (pinfunction "DOUT_3") (pintype "bidirectional"))
      (node (ref "RL2") (pin "1") (pinfunction "DIN_1") (pintype "bidirectional"))
    )
    (net (code "110") (name "Net-(RL2-DOUT)") (class "Default")
      (node (ref "RL2") (pin "3") (pinfunction "DOUT_3") (pintype "bidirectional"))
      (node (ref "RL3") (pin "1") (pinfunction "DIN_1") (pintype "bidirectional"))
    )
    (net (code "111") (name "Net-(RL3-DOUT)") (class "Default")
      (node (ref "RL3") (pin "3") (pinfunction "DOUT_3") (pintype "bidirectional"))
      (node (ref "RL4") (pin "1") (pinfunction "DIN_1") (pintype "bidirectional"))
    )
    (net (code "112") (name "Net-(RL4-DOUT)") (class "Default")
      (node (ref "RL4") (pin "3") (pinfunction "DOUT_3") (pintype "bidirectional"))
      (node (ref "RL5") (pin "1") (pinfunction "DIN_1") (pintype "bidirectional"))
    )
    (net (code "113") (name "Net-(RL5-DOUT)") (class "Default")
      (node (ref "RL5") (pin "3") (pinfunction "DOUT_3") (pintype "bidirectional"))
      (node (ref "RL6") (pin "1") (pinfunction "DIN_1") (pintype "bidirectional"))
    )
    (net (code "114") (name "Net-(RL6-DOUT)") (class "Default")
      (node (ref "RL6") (pin "3") (pinfunction "DOUT_3") (pintype "bidirectional"))
      (node (ref "RL7") (pin "1") (pinfunction "DIN_1") (pintype "bidirectional"))
    )
    (net (code "115") (name "Net-(RL7-DOUT)") (class "Default")
      (node (ref "RL7") (pin "3") (pinfunction "DOUT_3") (pintype "bidirectional"))
      (node (ref "RL8") (pin "1") (pinfunction "DIN_1") (pintype "bidirectional"))
    )
    (net (code "116") (name "Net-(RL8-DOUT)") (class "Default")
      (node (ref "RL8") (pin "3") (pinfunction "DOUT_3") (pintype "bidirectional"))
      (node (ref "RL9") (pin "1") (pinfunction "DIN_1") (pintype "bidirectional"))
    )
    (net (code "117") (name "Net-(RL10-DIN)") (class "Default")
      (node (ref "RL10") (pin "1") (pinfunction "DIN_1") (pintype "bidirectional"))
      (node (ref "RL9") (pin "3") (pinfunction "DOUT_3") (pintype "bidirectional"))
    )
    (net (code "118") (name "Net-(RL10-DOUT)") (class "Default")
      (node (ref "RL10") (pin "3") (pinfunction "DOUT_3") (pintype "bidirectional"))
      (node (ref "RL11") (pin "1") (pinfunction "DIN_1") (pintype "bidirectional"))
    )
    (net (code "119") (name "Net-(RL11-DOUT)") (class "Default")
      (node (ref "RL11") (pin "3") (pinfunction "DOUT_3") (pintype "bidirectional"))
      (node (ref "RL12") (pin "1") (pinfunction "DIN_1") (pintype "bidirectional"))
    )
    (net (code "120") (name "Net-(RL12-DOUT)") (class "Default")
      (node (ref "RL12") (pin "3") (pinfunction "DOUT_3") (pintype "bidirectional"))
      (node (ref "RL13") (pin "1") (pinfunction "DIN_1") (pintype "bidirectional"))
    )
    (net (code "121") (name "Net-(RL13-DOUT)") (class "Default")
      (node (ref "RL13") (pin "3") (pinfunction "DOUT_3") (pintype "bidirectional"))
      (node (ref "RL14") (pin "1") (pinfunction "DIN_1") (pintype "bidirectional"))
    )
    (net (code "122") (name "Net-(RL14-DOUT)") (class "Default")
      (node (ref "RL14") (pin "3") (pinfunction "DOUT_3") (pintype "bidirectional"))
      (node (ref "RL15") (pin "1") (pinfunction "DIN_1") (pintype "bidirectional"))
    )
    (net (code "123") (name "Net-(RL15-DOUT)") (class "Default")
      (node (ref "RL15") (pin "3") (pinfunction "DOUT_3") (pintype "bidirectional"))
      (node (ref "RL16") (pin "1") (pinfunction "DIN_1") (pintype "bidirectional"))
    )
    (net (code "124") (name "Net-(RL16-DOUT)") (class "Default")
      (node (ref "RL16") (pin "3") (pinfunction "DOUT_3") (pintype "bidirectional"))
      (node (ref "RL17") (pin "1") (pinfunction "DIN_1") (pintype "bidirectional"))
    )
    (net (code "125") (name "Net-(RL17-DOUT)") (class "Default")
      (node (ref "RL17") (pin "3") (pinfunction "DOUT_3") (pintype "bidirectional"))
      (node (ref "RL18") (pin "1") (pinfunction "DIN_1") (pintype "bidirectional"))
    )
    (net (code "126") (name "Net-(RL18-DOUT)") (class "Default")
      (node (ref "RL18") (pin "3") (pinfunction "DOUT_3") (pintype "bidirectional"))
      (node (ref "RL19") (pin "1") (pinfunction "DIN_1") (pintype "bidirectional"))
    )
    (net (code "127") (name "Net-(RL19-DOUT)") (class "Default")
      (node (ref "RL19") (pin "3") (pinfunction "DOUT_3") (pintype "bidirectional"))
      (node (ref "RL20") (pin "1") (pinfunction "DIN_1") (pintype "bidirectional"))
    )
    (net (code "128") (name "Net-(RL20-DOUT)") (class "Default")
      (node (ref "RL20") (pin "3") (pinfunction "DOUT_3") (pintype "bidirectional"))
      (node (ref "RL21") (pin "1") (pinfunction "DIN_1") (pintype "bidirectional"))
    )
    (net (code "129") (name "Net-(RL21-DOUT)") (class "Default")
      (node (ref "RL21") (pin "3") (pinfunction "DOUT_3") (pintype "bidirectional"))
      (node (ref "RL22") (pin "1") (pinfunction "DIN_1") (pintype "bidirectional"))
    )
    (net (code "130") (name "Net-(RL22-DOUT)") (class "Default")
      (node (ref "RL22") (pin "3") (pinfunction "DOUT_3") (pintype "bidirectional"))
      (node (ref "RL23") (pin "1") (pinfunction "DIN_1") (pintype "bidirectional"))
    )
    (net (code "131") (name "Net-(RL23-DOUT)") (class "Default")
      (node (ref "RL23") (pin "3") (pinfunction "DOUT_3") (pintype "bidirectional"))
      (node (ref "RL24") (pin "1") (pinfunction "DIN_1") (pintype "bidirectional"))
    )
    (net (code "132") (name "Net-(RL24-DOUT)") (class "Default")
      (node (ref "RL24") (pin "3") (pinfunction "DOUT_3") (pintype "bidirectional"))
      (node (ref "RL25") (pin "1") (pinfunction "DIN_1") (pintype "bidirectional"))
    )
    (net (code "133") (name "Net-(RL25-DOUT)") (class "Default")
      (node (ref "RL25") (pin "3") (pinfunction "DOUT_3") (pintype "bidirectional"))
      (node (ref "RL26") (pin "1") (pinfunction "DIN_1") (pintype "bidirectional"))
    )
    (net (code "134") (name "Net-(RL26-DOUT)") (class "Default")
      (node (ref "RL26") (pin "3") (pinfunction "DOUT_3") (pintype "bidirectional"))
      (node (ref "RL27") (pin "1") (pinfunction "DIN_1") (pintype "bidirectional"))
    )
    (net (code "135") (name "Net-(U1-3V3)") (class "Default")
      (node (ref "JP1") (pin "2") (pinfunction "2_2") (pintype "passive"))
      (node (ref "U1") (pin "1") (pinfunction "3V3_1") (pintype "power_in"))
    )
    (net (code "136") (name "Net-(YL1-DIN)") (class "Default")
      (node (ref "R3") (pin "2") (pinfunction "2_2") (pintype "passive"))
      (node (ref "YL1") (pin "1") (pinfunction "DIN_1") (pintype "bidirectional"))
    )
    (net (code "137") (name "Net-(YL1-DOUT)") (class "Default")
      (node (ref "YL1") (pin "3") (pinfunction "DOUT_3") (pintype "bidirectional"))
      (node (ref "YL2") (pin "1") (pinfunction "DIN_1") (pintype "bidirectional"))
    )
    (net (code "138") (name "Net-(YL2-DOUT)") (class "Default")
      (node (ref "YL2") (pin "3") (pinfunction "DOUT_3") (pintype "bidirectional"))
      (node (ref "YL3") (pin "1") (pinfunction "DIN_1") (pintype "bidirectional"))
    )
    (net (code "139") (name "Net-(YL3-DOUT)") (class "Default")
      (node (ref "YL3") (pin "3") (pinfunction "DOUT_3") (pintype "bidirectional"))
      (node (ref "YL4") (pin "1") (pinfunction "DIN_1") (pintype "bidirectional"))
    )
    (net (code "140") (name "Net-(YL4-DOUT)") (class "Default")
      (node (ref "YL4") (pin "3") (pinfunction "DOUT_3") (pintype "bidirectional"))
      (node (ref "YL5") (pin "1") (pinfunction "DIN_1") (pintype "bidirectional"))
    )
    (net (code "141") (name "Net-(YL5-DOUT)") (class "Default")
      (node (ref "YL5") (pin "3") (pinfunction "DOUT_3") (pintype "bidirectional"))
      (node (ref "YL6") (pin "1") (pinfunction "DIN_1") (pintype "bidirectional"))
    )
    (net (code "142") (name "Net-(YL6-DOUT)") (class "Default")
      (node (ref "YL6") (pin "3") (pinfunction "DOUT_3") (pintype "bidirectional"))
      (node (ref "YL7") (pin "1") (pinfunction "DIN_1") (pintype "bidirectional"))
    )
    (net (code "143") (name "Net-(YL7-DOUT)") (class "Default")
      (node (ref "YL7") (pin "3") (pinfunction "DOUT_3") (pintype "bidirectional"))
      (node (ref "YL8") (pin "1") (pinfunction "DIN_1") (pintype "bidirectional"))
    )
    (net (code "144") (name "Net-(YL8-DOUT)") (class "Default")
      (node (ref "YL8") (pin "3") (pinfunction "DOUT_3") (pintype "bidirectional"))
      (node (ref "YL9") (pin "1") (pinfunction "DIN_1") (pintype "bidirectional"))
    )
    (net (code "145") (name "Net-(YL10-DIN)") (class "Default")
      (node (ref "YL10") (pin "1") (pinfunction "DIN_1") (pintype "bidirectional"))
      (node (ref "YL9") (pin "3") (pinfunction "DOUT_3") (pintype "bidirectional"))
    )
    (net (code "146") (name "Net-(YL10-DOUT)") (class "Default")
      (node (ref "YL10") (pin "3") (pinfunction "DOUT_3") (pintype "bidirectional"))
      (node (ref "YL11") (pin "1") (pinfunction "DIN_1") (pintype "bidirectional"))
    )
    (net (code "147") (name "Net-(YL11-DOUT)") (class "Default")
      (node (ref "YL11") (pin "3") (pinfunction "DOUT_3") (pintype "bidirectional"))
      (node (ref "YL12") (pin "1") (pinfunction "DIN_1") (pintype "bidirectional"))
    )
    (net (code "148") (name "Net-(YL12-DOUT)") (class "Default")
      (node (ref "YL12") (pin "3") (pinfunction "DOUT_3") (pintype "bidirectional"))
      (node (ref "YL13") (pin "1") (pinfunction "DIN_1") (pintype "bidirectional"))
    )
    (net (code "149") (name "Net-(YL13-DOUT)") (class "Default")
      (node (ref "YL13") (pin "3") (pinfunction "DOUT_3") (pintype "bidirectional"))
      (node (ref "YL14") (pin "1") (pinfunction "DIN_1") (pintype "bidirectional"))
    )
    (net (code "150") (name "Net-(YL14-DOUT)") (class "Default")
      (node (ref "YL14") (pin "3") (pinfunction "DOUT_3") (pintype "bidirectional"))
      (node (ref "YL15") (pin "1") (pinfunction "DIN_1") (pintype "bidirectional"))
    )
    (net (code "151") (name "Net-(YL15-DOUT)") (class "Default")
      (node (ref "YL15") (pin "3") (pinfunction "DOUT_3") (pintype "bidirectional"))
      (node (ref "YL16") (pin "1") (pinfunction "DIN_1") (pintype "bidirectional"))
    )
    (net (code "152") (name "Net-(YL16-DOUT)") (class "Default")
      (node (ref "YL16") (pin "3") (pinfunction "DOUT_3") (pintype "bidirectional"))
      (node (ref "YL17") (pin "1") (pinfunction "DIN_1") (pintype "bidirectional"))
    )
    (net (code "153") (name "ORANGE_LINE") (class "Default")
      (node (ref "IC2") (pin "13") (pinfunction "B1Y_13") (pintype "bidirectional"))
      (node (ref "R5") (pin "1") (pinfunction "1_1") (pintype "passive"))
    )
    (net (code "154") (name "RED_LINE") (class "Default")
      (node (ref "IC1") (pin "12") (pinfunction "B2Y_12") (pintype "bidirectional"))
      (node (ref "R2") (pin "1") (pinfunction "1_1") (pintype "passive"))
    )
    (net (code "155") (name "YELLOW_LINE") (class "Default")
      (node (ref "IC1") (pin "11") (pinfunction "B3Y_11") (pintype "bidirectional"))
      (node (ref "R3") (pin "1") (pinfunction "1_1") (pintype "passive"))
    )
    (net (code "156") (name "unconnected-(BL49-DOUT-Pad3)") (class "Default")
      (node (ref "BL49") (pin "3") (pinfunction "DOUT_3") (pintype "bidirectional"))
    )
    (net (code "157") (name "unconnected-(GL30-DOUT-Pad3)") (class "Default")
      (node (ref "GL30") (pin "3") (pinfunction "DOUT_3") (pintype "bidirectional"))
    )
    (net (code "158") (name "unconnected-(IC1-A4Y-Pad5)") (class "Default")
      (node (ref "IC1") (pin "5") (pinfunction "A4Y_5") (pintype "bidirectional"))
    )
    (net (code "159") (name "unconnected-(IC1-B4-Pad10)") (class "Default")
      (node (ref "IC1") (pin "10") (pinfunction "B4_10") (pintype "bidirectional"))
    )
    (net (code "160") (name "unconnected-(IC1-NC_1-Pad6)") (class "Default")
      (node (ref "IC1") (pin "6") (pinfunction "NC_1_6") (pintype "bidirectional"))
    )
    (net (code "161") (name "unconnected-(IC1-NC_2-Pad9)") (class "Default")
      (node (ref "IC1") (pin "9") (pinfunction "NC_2_9") (pintype "bidirectional"))
    )
    (net (code "162") (name "unconnected-(IC2-A3-Pad4)") (class "Default")
      (node (ref "IC2") (pin "4") (pinfunction "A3_4") (pintype "bidirectional"))
    )
    (net (code "163") (name "unconnected-(IC2-A4Y-Pad5)") (class "Default")
      (node (ref "IC2") (pin "5") (pinfunction "A4Y_5") (pintype "bidirectional"))
    )
    (net (code "164") (name "unconnected-(IC2-B3Y-Pad11)") (class "Default")
      (node (ref "IC2") (pin "11") (pinfunction "B3Y_11") (pintype "bidirectional"))
    )
    (net (code "165") (name "unconnected-(IC2-B4-Pad10)") (class "Default")
      (node (ref "IC2") (pin "10") (pinfunction "B4_10") (pintype "bidirectional"))
    )
    (net (code "166") (name "unconnected-(IC2-NC_1-Pad6)") (class "Default")
      (node (ref "IC2") (pin "6") (pinfunction "NC_1_6") (pintype "bidirectional"))
    )
    (net (code "167") (name "unconnected-(IC2-NC_2-Pad9)") (class "Default")
      (node (ref "IC2") (pin "9") (pinfunction "NC_2_9") (pintype "bidirectional"))
    )
    (net (code "168") (name "unconnected-(OL17-DOUT-Pad3)") (class "Default")
      (node (ref "OL17") (pin "3") (pinfunction "DOUT_3") (pintype "bidirectional"))
    )
    (net (code "169") (name "unconnected-(RL27-DOUT-Pad3)") (class "Default")
      (node (ref "RL27") (pin "3") (pinfunction "DOUT_3") (pintype "bidirectional"))
    )
    (net (code "170") (name "unconnected-(U1-CLK-Pad38)") (class "Default")
      (node (ref "U1") (pin "38") (pinfunction "CLK_38") (pintype "input"))
    )
    (net (code "171") (name "unconnected-(U1-CMD-Pad18)") (class "Default")
      (node (ref "U1") (pin "18") (pinfunction "CMD_18") (pintype "bidirectional"))
    )
    (net (code "172") (name "unconnected-(U1-EN-Pad2)") (class "Default")
      (node (ref "U1") (pin "2") (pinfunction "EN_2") (pintype "input"))
    )
    (net (code "173") (name "unconnected-(U1-IO0-Pad33)") (class "Default")
      (node (ref "U1") (pin "33") (pinfunction "IO0_33") (pintype "bidirectional"))
    )
    (net (code "174") (name "unconnected-(U1-IO2-Pad34)") (class "Default")
      (node (ref "U1") (pin "34") (pinfunction "IO2_34") (pintype "bidirectional"))
    )
    (net (code "175") (name "unconnected-(U1-IO4-Pad32)") (class "Default")
      (node (ref "U1") (pin "32") (pinfunction "IO4_32") (pintype "bidirectional"))
    )
    (net (code "176") (name "unconnected-(U1-IO5-Pad29)") (class "Default")
      (node (ref "U1") (pin "29") (pinfunction "IO5_29") (pintype "bidirectional"))
    )
    (net (code "177") (name "unconnected-(U1-IO13-Pad15)") (class "Default")
      (node (ref "U1") (pin "15") (pinfunction "IO13_15") (pintype "bidirectional"))
    )
    (net (code "178") (name "unconnected-(U1-IO15-Pad35)") (class "Default")
      (node (ref "U1") (pin "35") (pinfunction "IO15_35") (pintype "bidirectional"))
    )
    (net (code "179") (name "unconnected-(U1-IO16-Pad31)") (class "Default")
      (node (ref "U1") (pin "31") (pinfunction "IO16_31") (pintype "bidirectional"))
    )
    (net (code "180") (name "unconnected-(U1-IO17-Pad30)") (class "Default")
      (node (ref "U1") (pin "30") (pinfunction "IO17_30") (pintype "bidirectional"))
    )
    (net (code "181") (name "unconnected-(U1-IO18-Pad28)") (class "Default")
      (node (ref "U1") (pin "28") (pinfunction "IO18_28") (pintype "bidirectional"))
    )
    (net (code "182") (name "unconnected-(U1-IO19-Pad27)") (class "Default")
      (node (ref "U1") (pin "27") (pinfunction "IO19_27") (pintype "bidirectional"))
    )
    (net (code "183") (name "unconnected-(U1-IO21-Pad25)") (class "Default")
      (node (ref "U1") (pin "25") (pinfunction "IO21_25") (pintype "bidirectional"))
    )
    (net (code "184") (name "unconnected-(U1-IO22-Pad22)") (class "Default")
      (node (ref "U1") (pin "22") (pinfunction "IO22_22") (pintype "bidirectional"))
    )
    (net (code "185") (name "unconnected-(U1-IO23-Pad21)") (class "Default")
      (node (ref "U1") (pin "21") (pinfunction "IO23_21") (pintype "bidirectional"))
    )
    (net (code "186") (name "unconnected-(U1-IO25-Pad9)") (class "Default")
      (node (ref "U1") (pin "9") (pinfunction "IO25_9") (pintype "bidirectional"))
    )
    (net (code "187") (name "unconnected-(U1-IO33-Pad8)") (class "Default")
      (node (ref "U1") (pin "8") (pinfunction "IO33_8") (pintype "bidirectional"))
    )
    (net (code "188") (name "unconnected-(U1-IO34-Pad5)") (class "Default")
      (node (ref "U1") (pin "5") (pinfunction "IO34_5") (pintype "bidirectional"))
    )
    (net (code "189") (name "unconnected-(U1-IO35-Pad6)") (class "Default")
      (node (ref "U1") (pin "6") (pinfunction "IO35_6") (pintype "bidirectional"))
    )
    (net (code "190") (name "unconnected-(U1-RXD0-Pad24)") (class "Default")
      (node (ref "U1") (pin "24") (pinfunction "RXD0_24") (pintype "input"))
    )
    (net (code "191") (name "unconnected-(U1-SD0-Pad37)") (class "Default")
      (node (ref "U1") (pin "37") (pinfunction "SD0_37") (pintype "bidirectional"))
    )
    (net (code "192") (name "unconnected-(U1-SD1-Pad36)") (class "Default")
      (node (ref "U1") (pin "36") (pinfunction "SD1_36") (pintype "bidirectional"))
    )
    (net (code "193") (name "unconnected-(U1-SD2-Pad16)") (class "Default")
      (node (ref "U1") (pin "16") (pinfunction "SD2_16") (pintype "bidirectional"))
    )
    (net (code "194") (name "unconnected-(U1-SD3-Pad17)") (class "Default")
      (node (ref "U1") (pin "17") (pinfunction "SD3_17") (pintype "bidirectional"))
    )
    (net (code "195") (name "unconnected-(U1-SENSOR_VN-Pad4)") (class "Default")
      (node (ref "U1") (pin "4") (pinfunction "SENSOR_VN_4") (pintype "input"))
    )
    (net (code "196") (name "unconnected-(U1-SENSOR_VP-Pad3)") (class "Default")
      (node (ref "U1") (pin "3") (pinfunction "SENSOR_VP_3") (pintype "input"))
    )
    (net (code "197") (name "unconnected-(U1-TXD0-Pad23)") (class "Default")
      (node (ref "U1") (pin "23") (pinfunction "TXD0_23") (pintype "output"))
    )
    (net (code "198") (name "unconnected-(VOLTAGE_REG-N.C.-Pad4)") (class "Default")
      (node (ref "VOLTAGE_REG") (pin "4") (pinfunction "N.C._4") (pintype "no_connect"))
    )
    (net (code "199") (name "unconnected-(YL17-DOUT-Pad3)") (class "Default")
      (node (ref "YL17") (pin "3") (pinfunction "DOUT_3") (pintype "bidirectional"))
    )
  )
)
